# PX4FMUv2_4.net
KiCad netlist of a schematic drawn in EAGLE
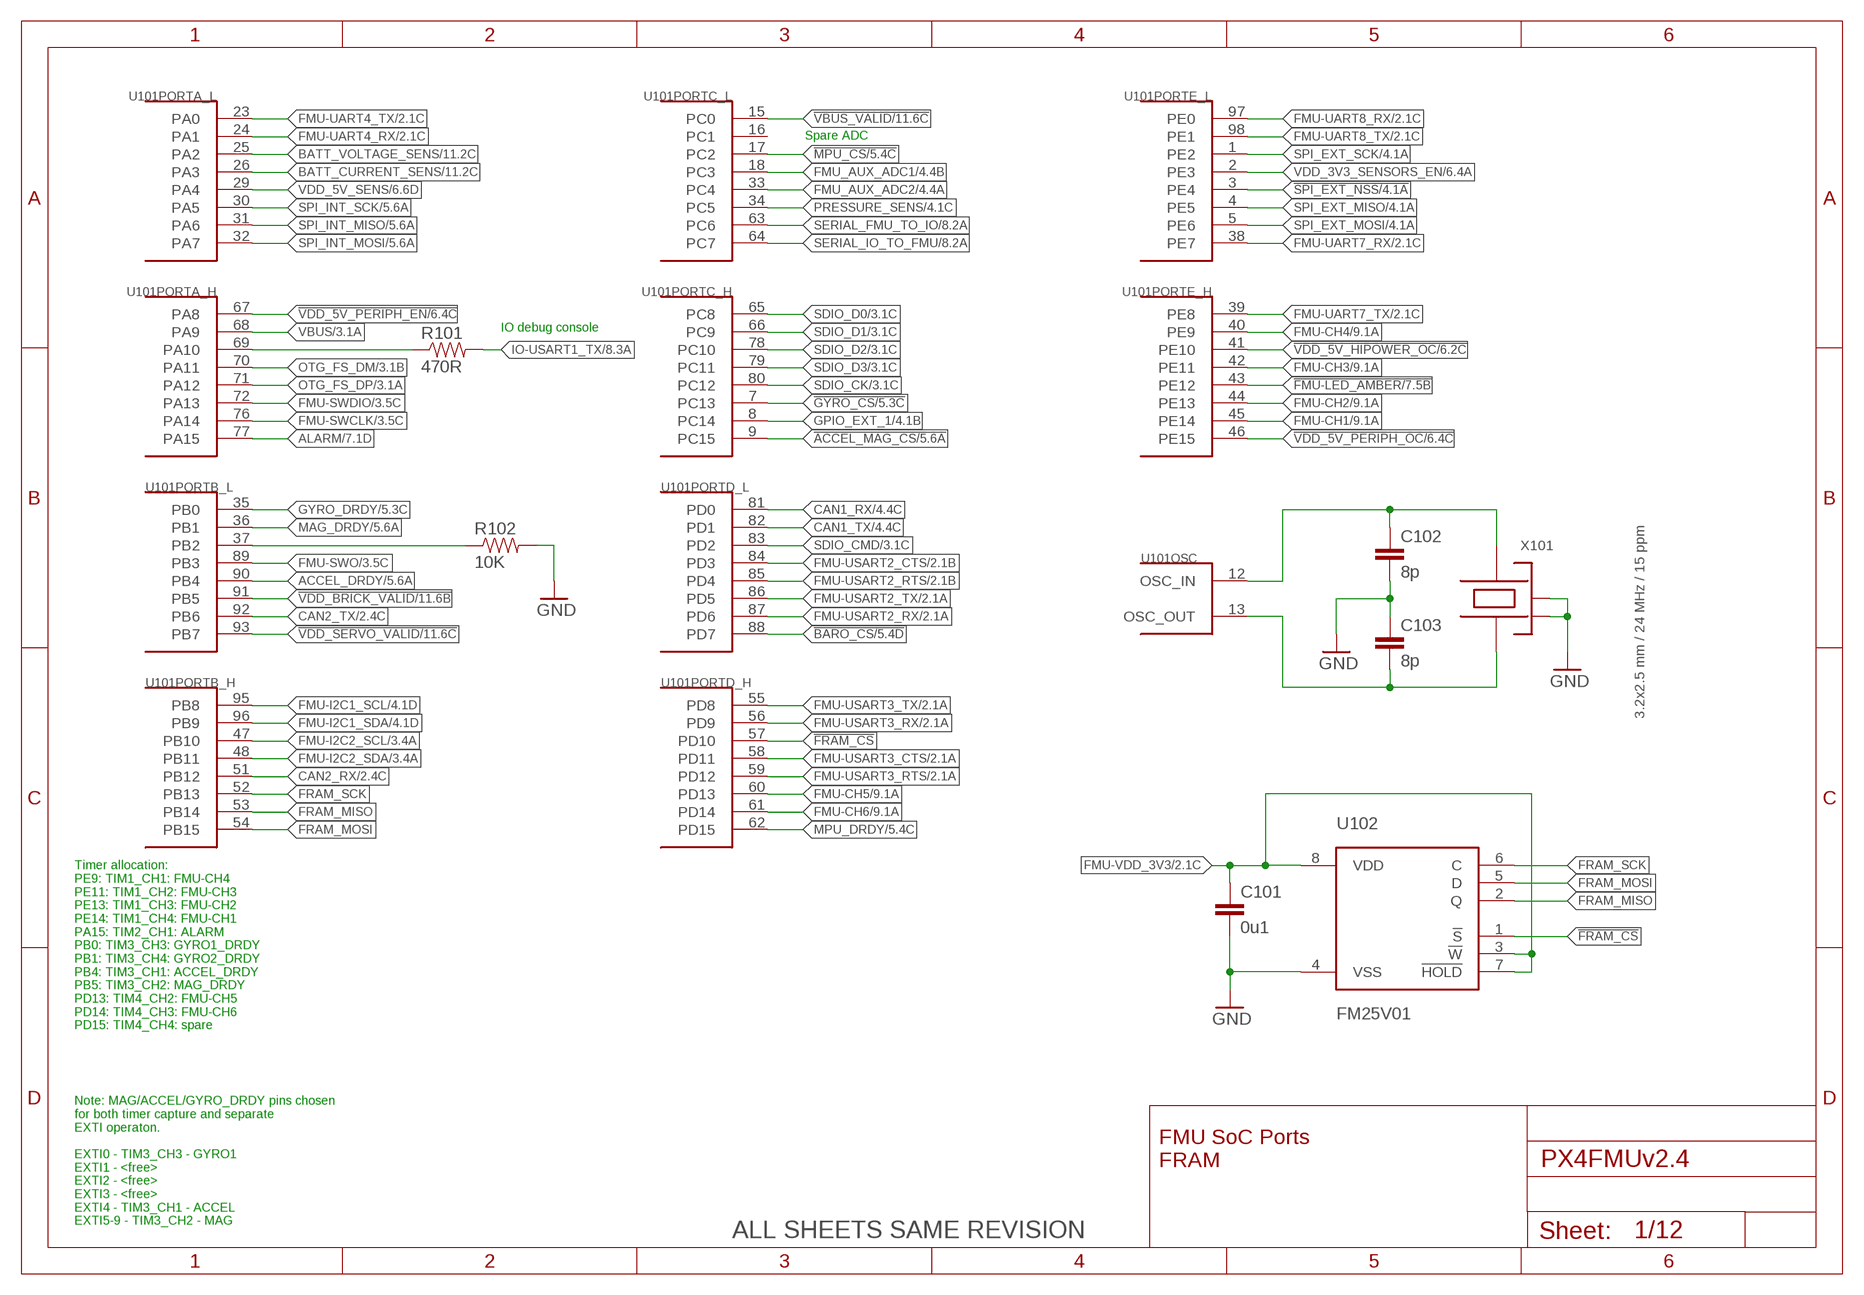
[diagram p0: schematic, sheet 1]
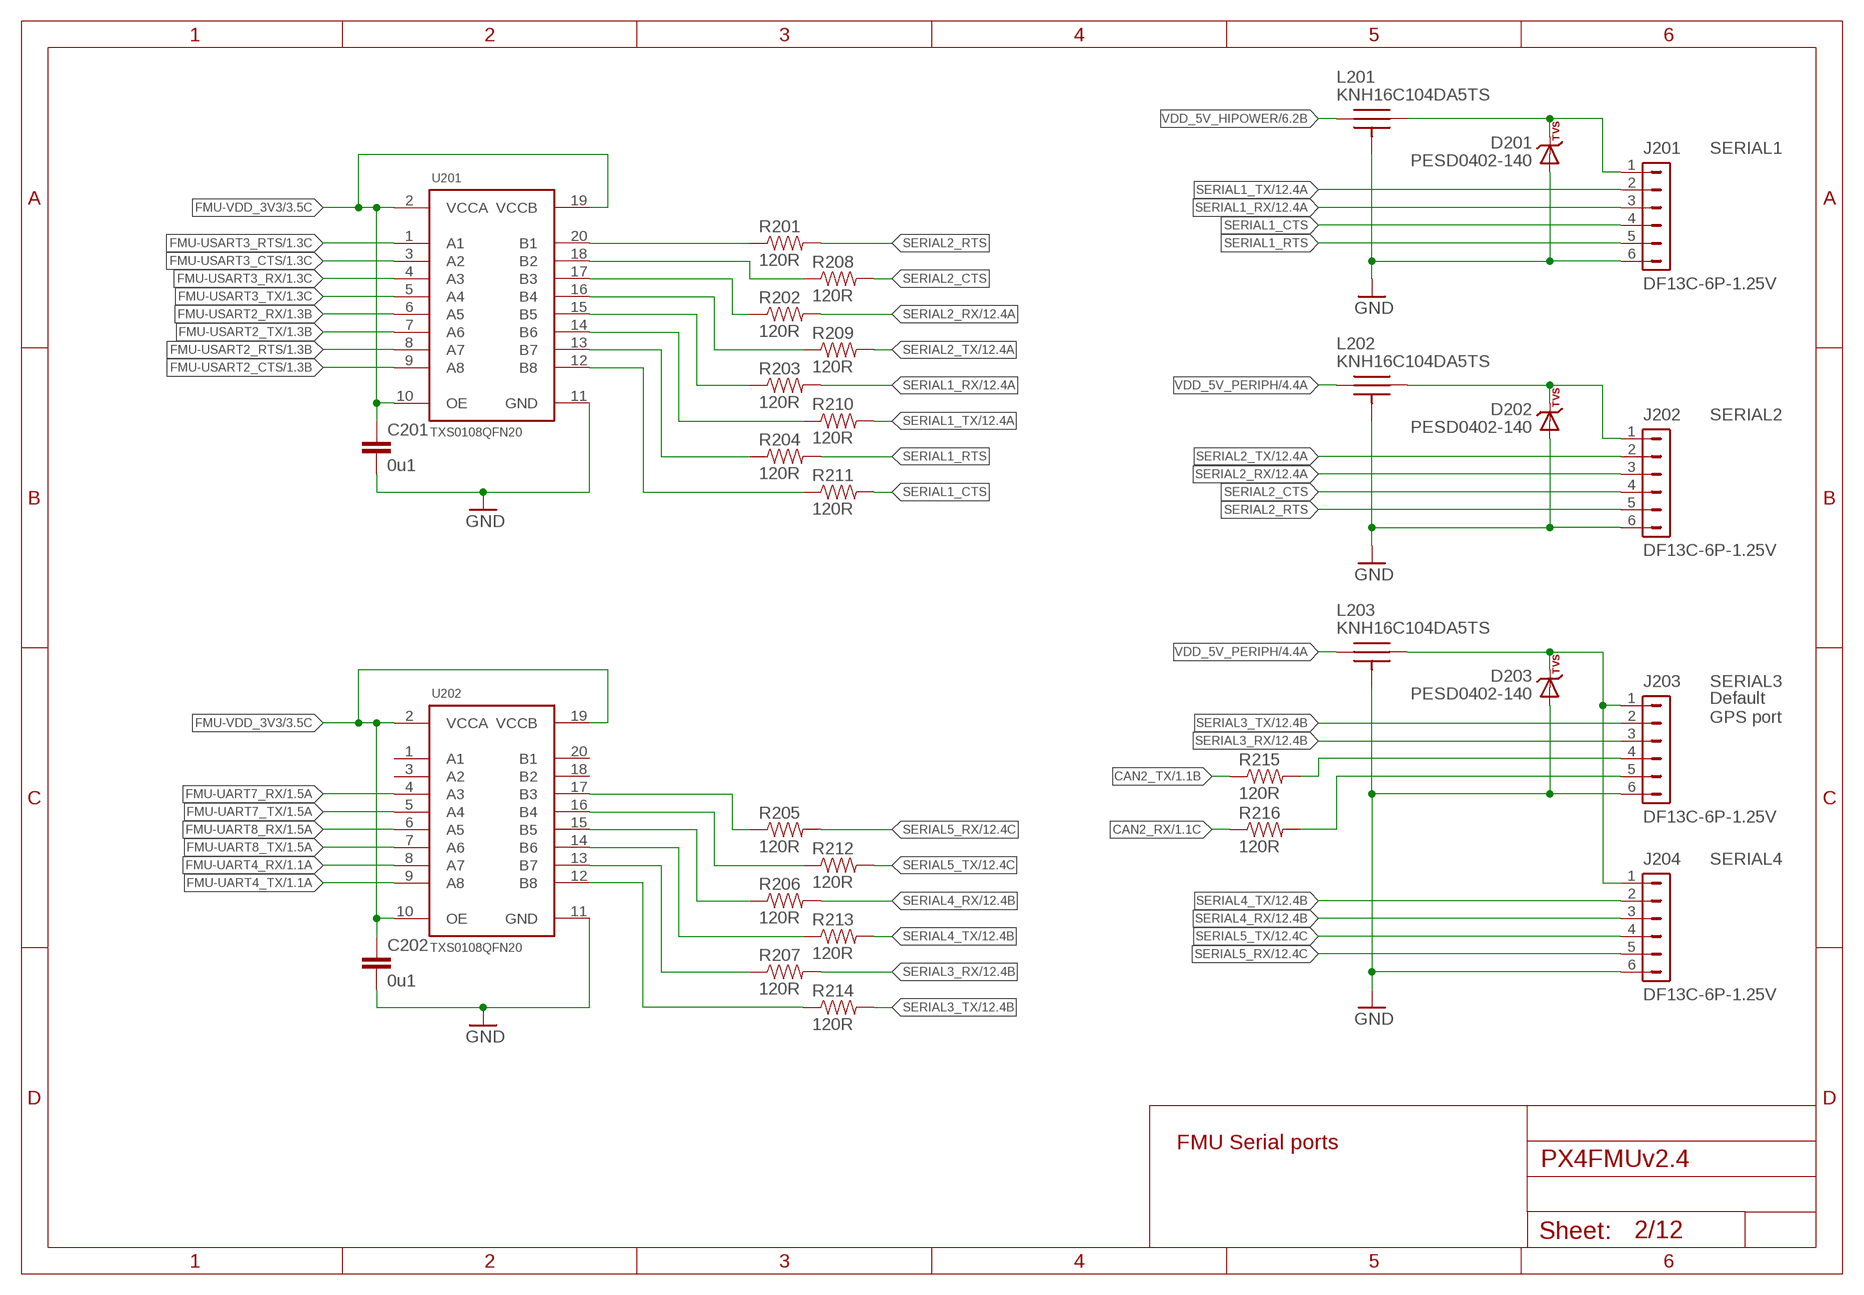
[diagram p1: schematic, sheet 2]
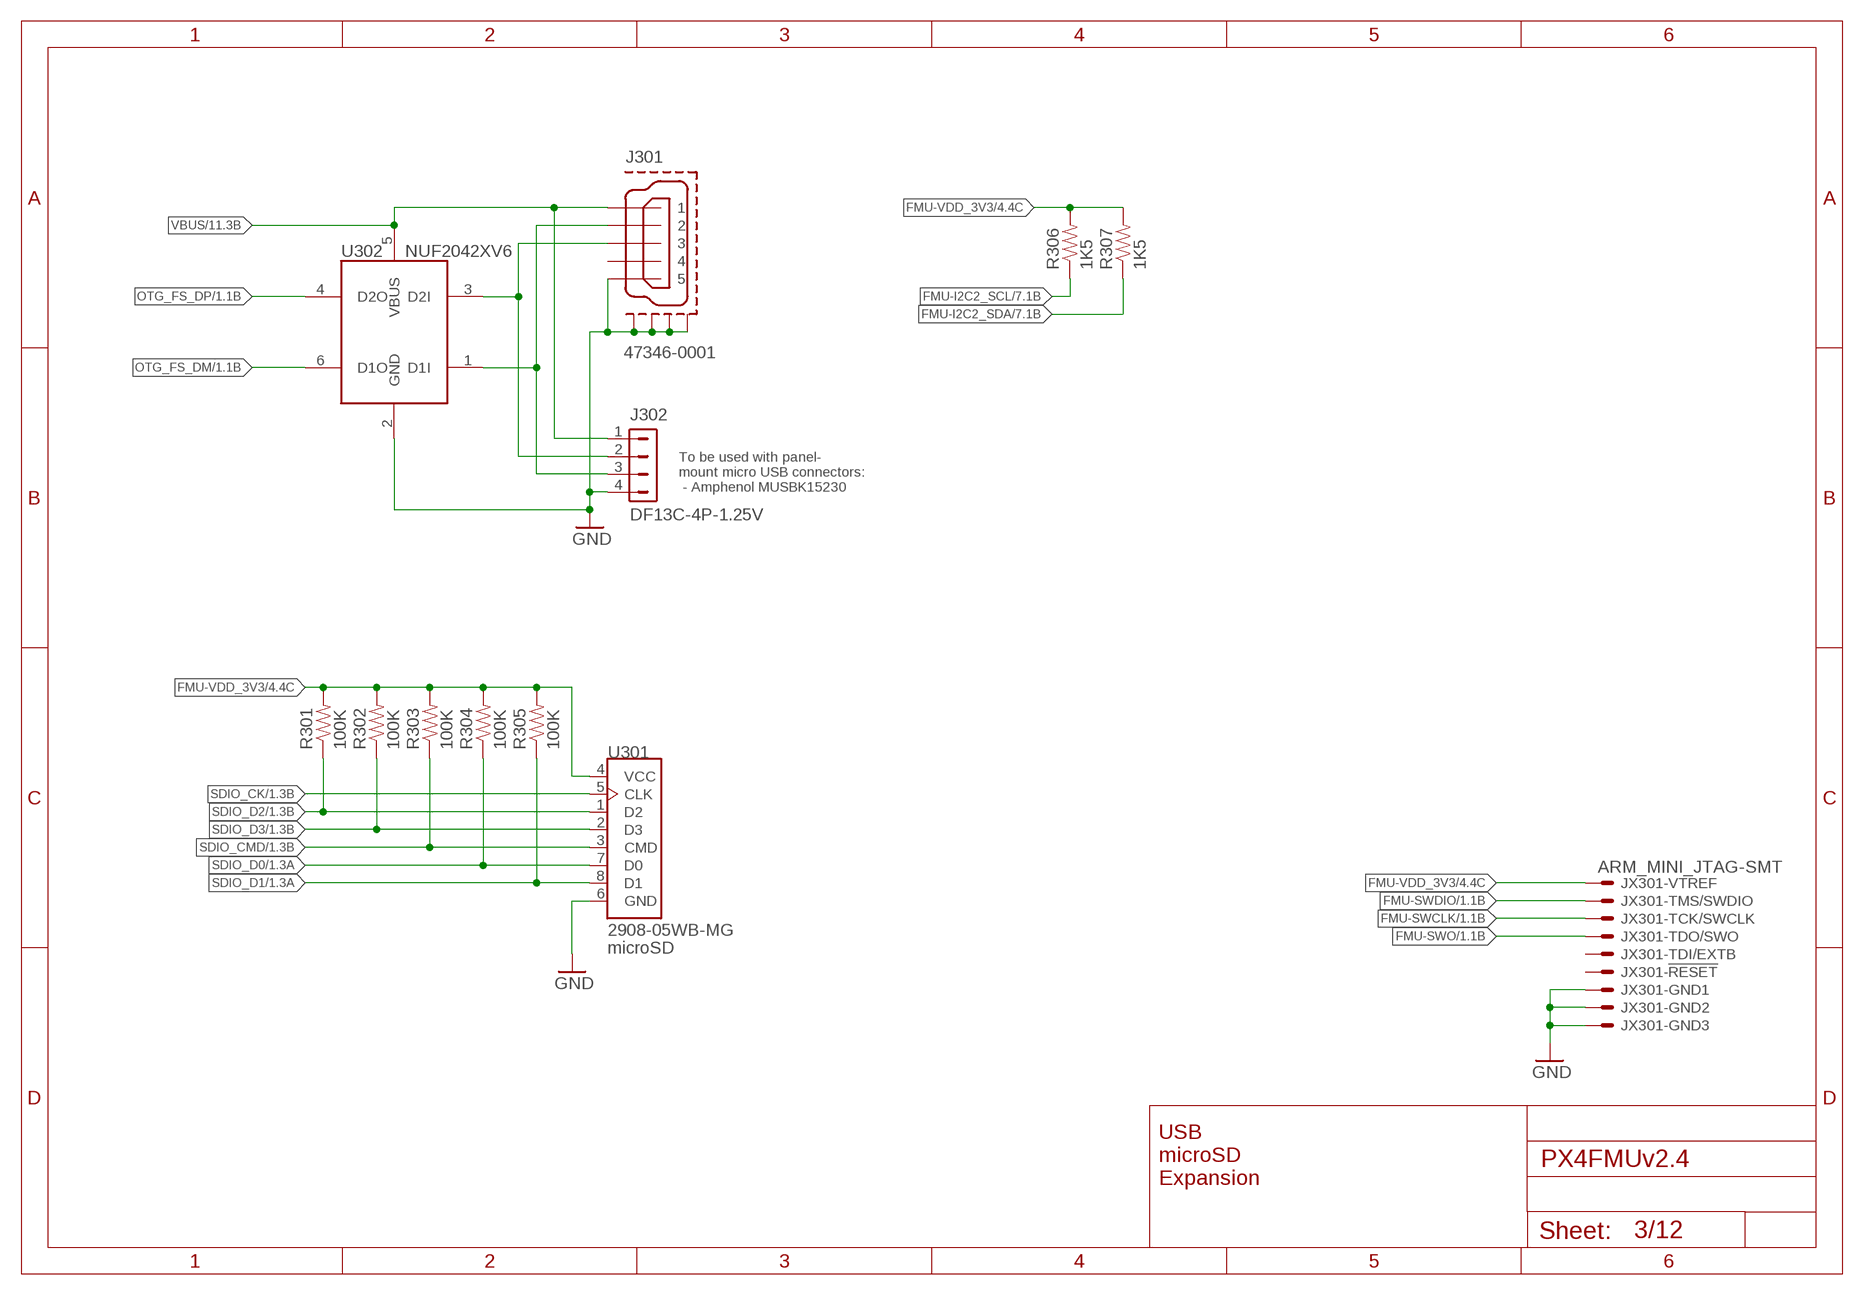
[diagram p2: schematic, sheet 3]
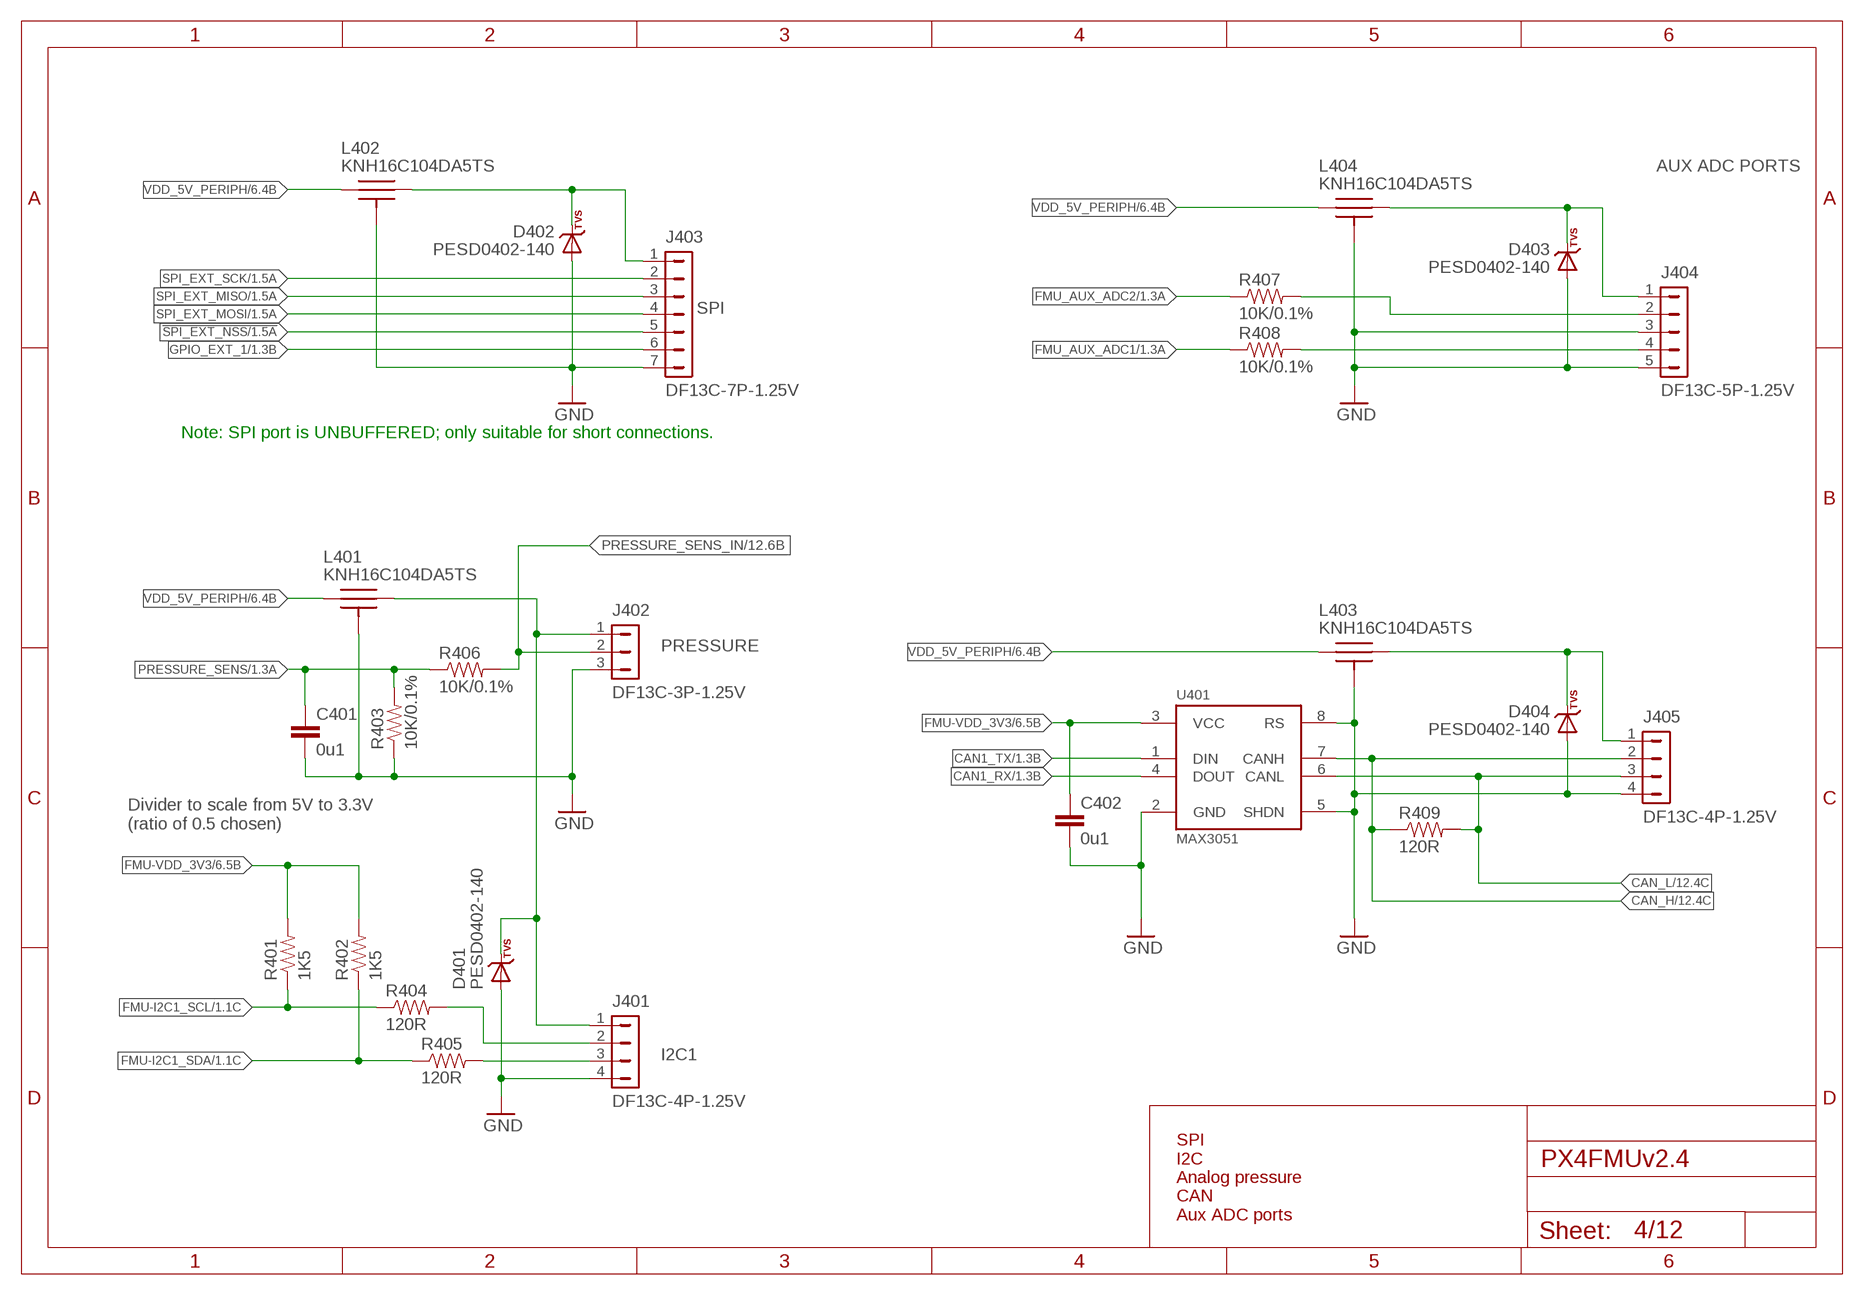
[diagram p3: schematic, sheet 4]
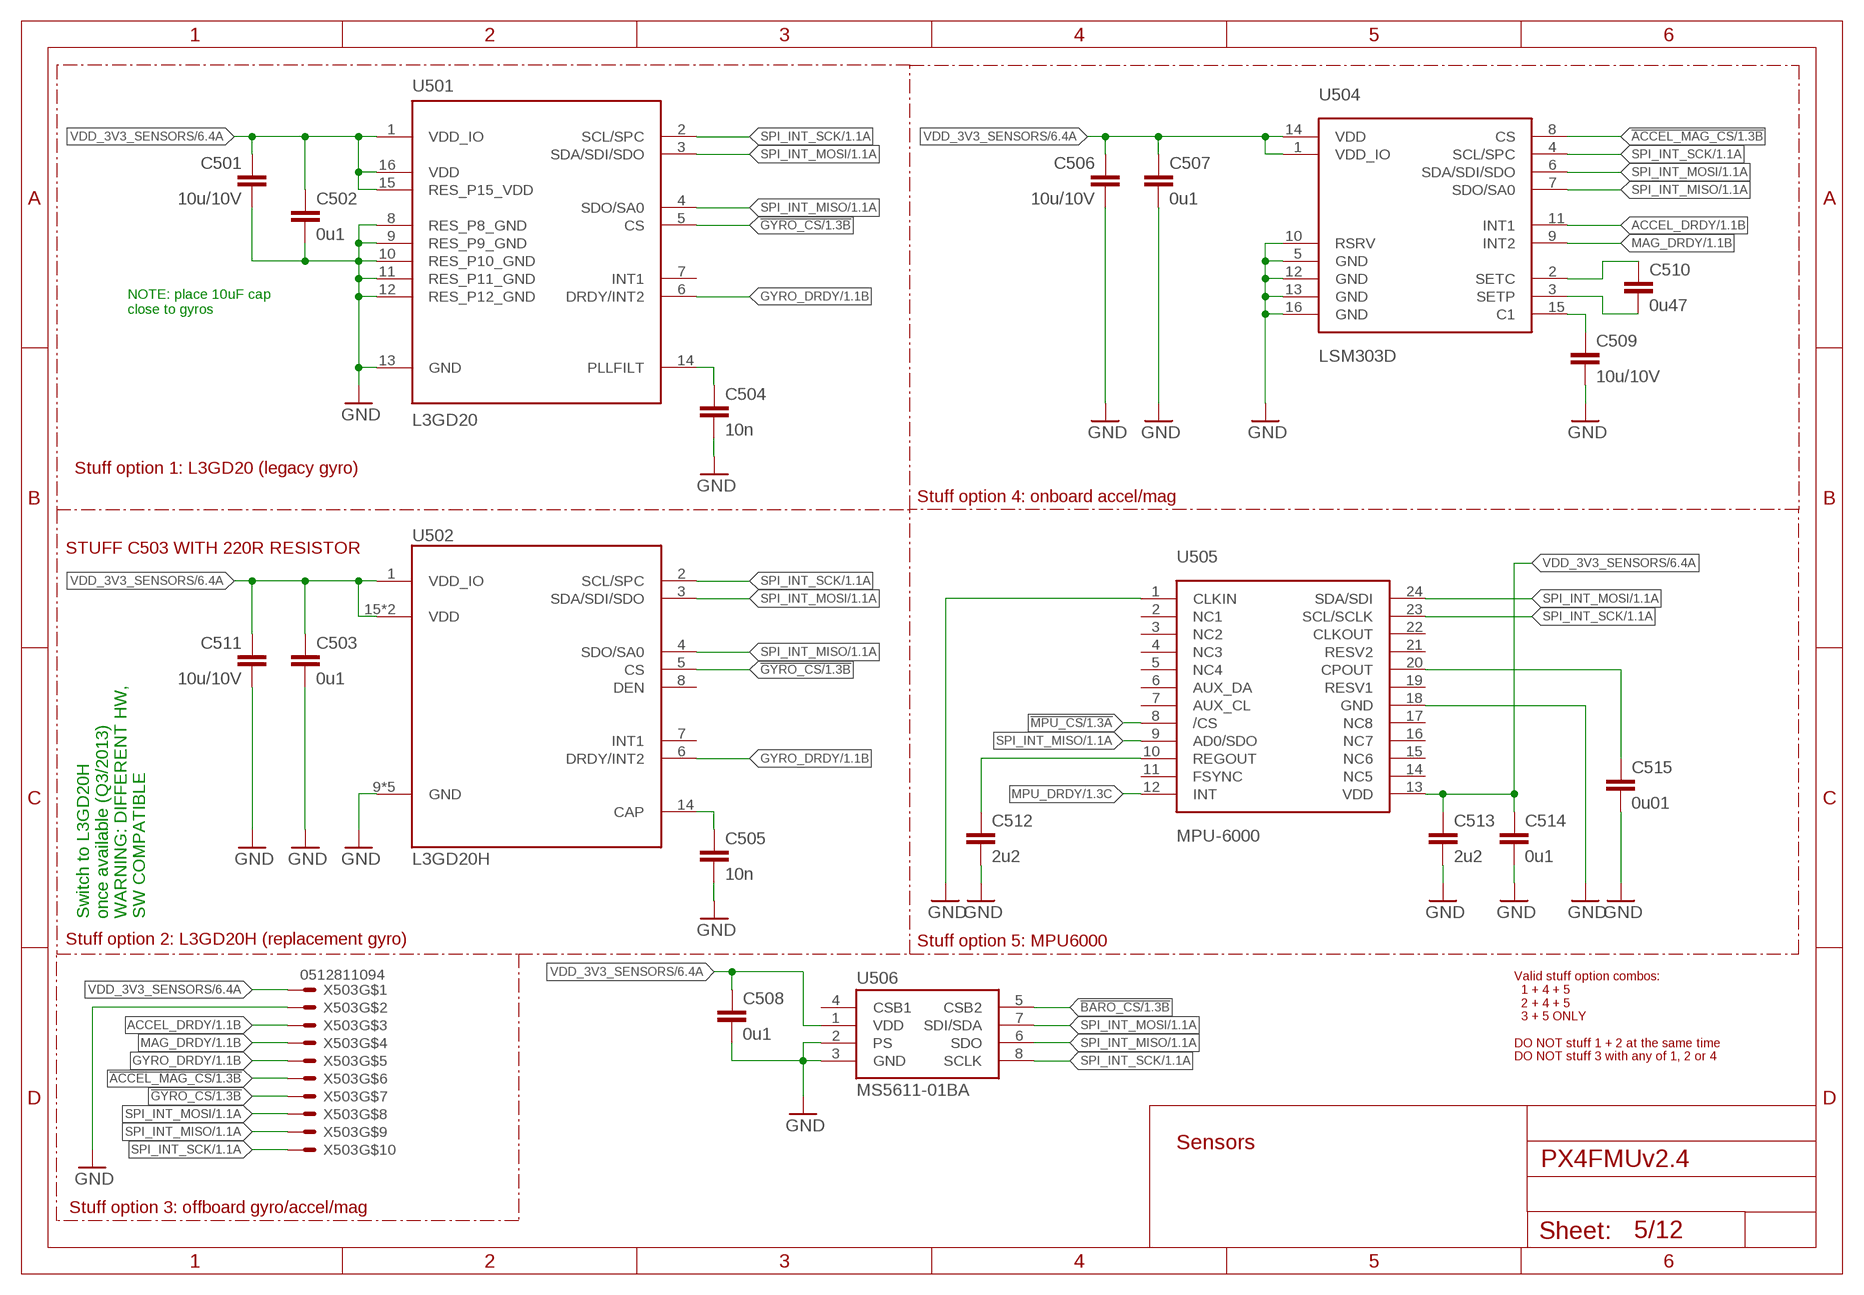
[diagram p4: schematic, sheet 5]
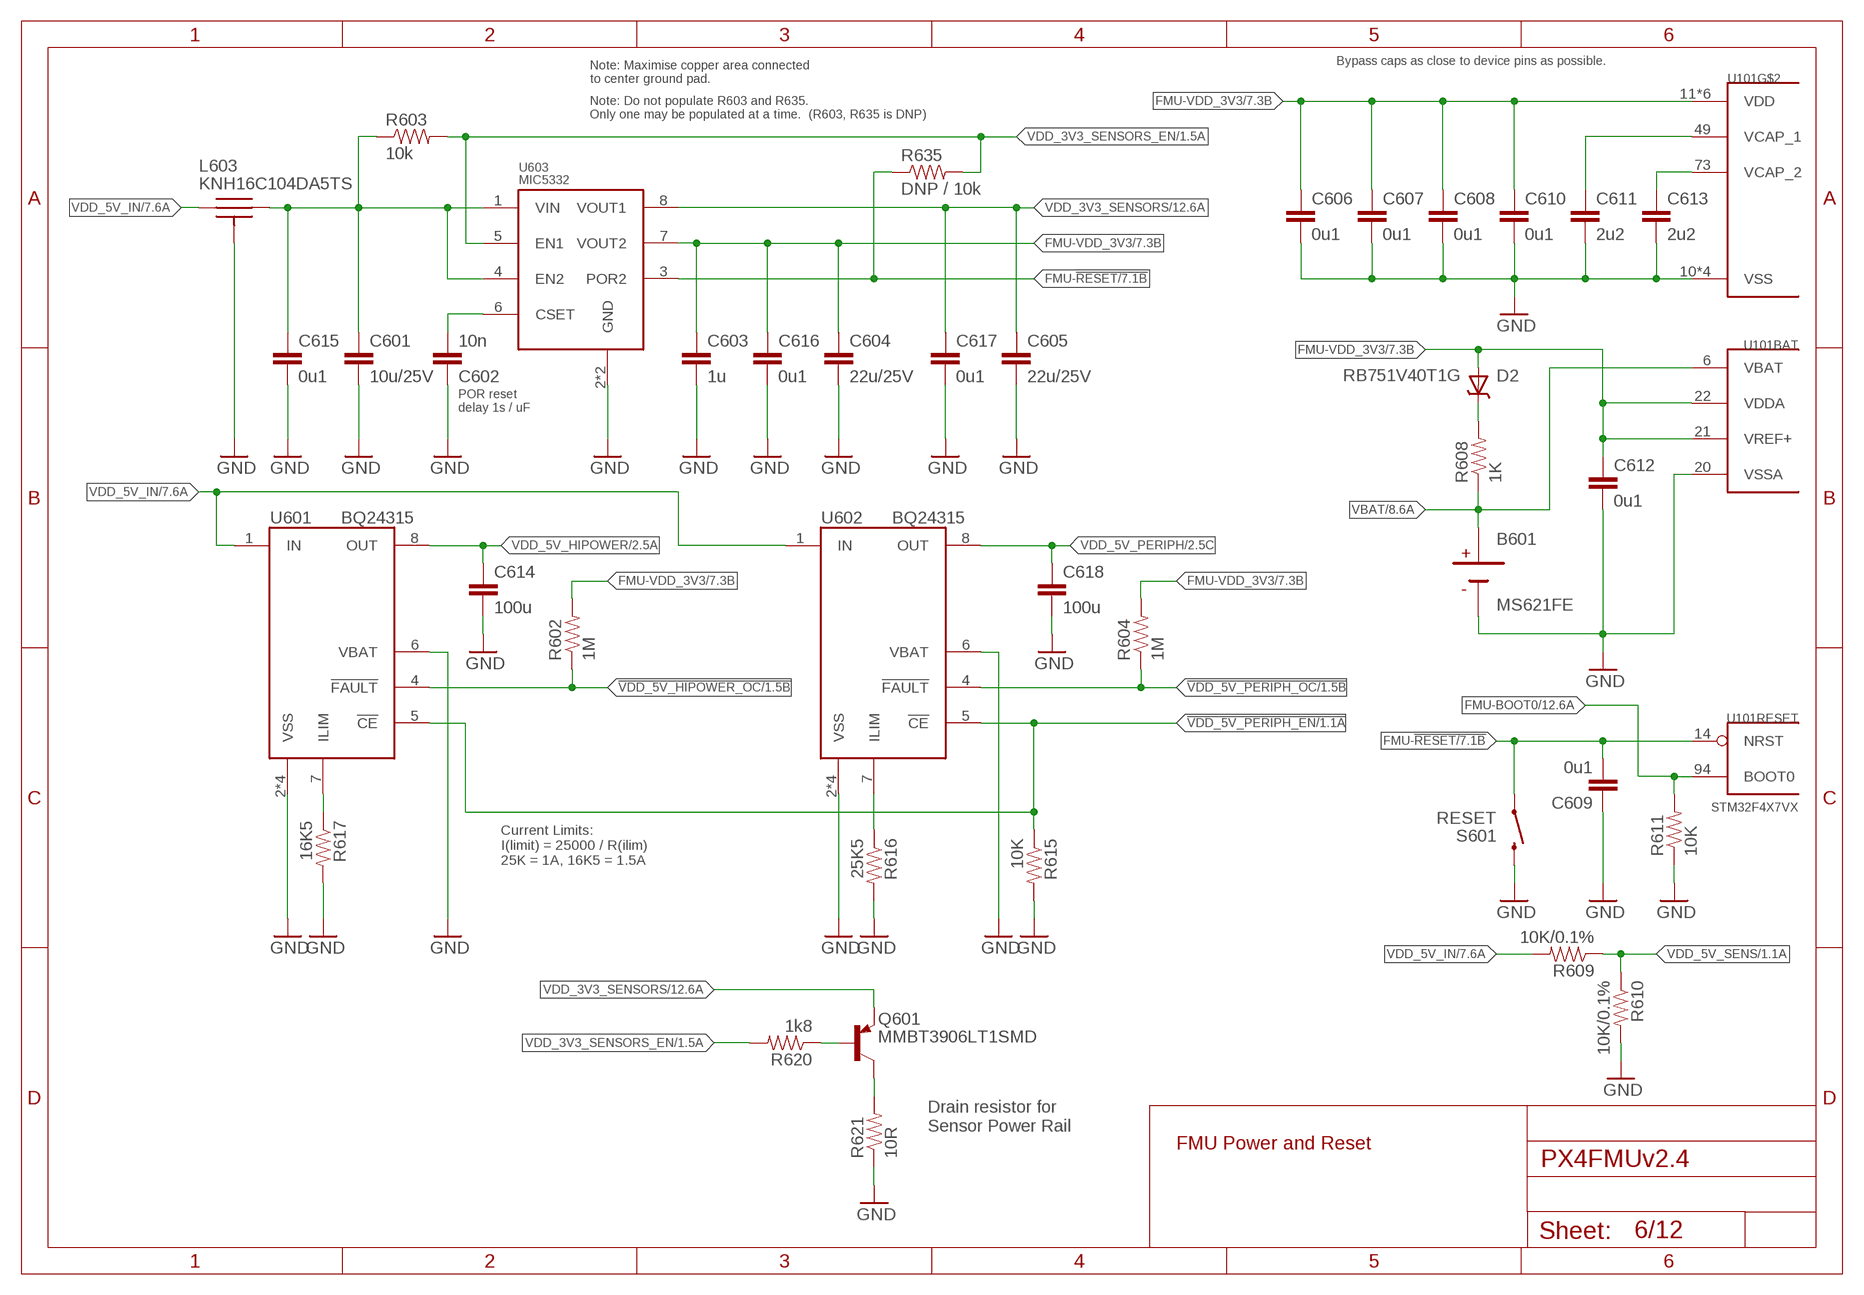
[diagram p5: schematic, sheet 6]
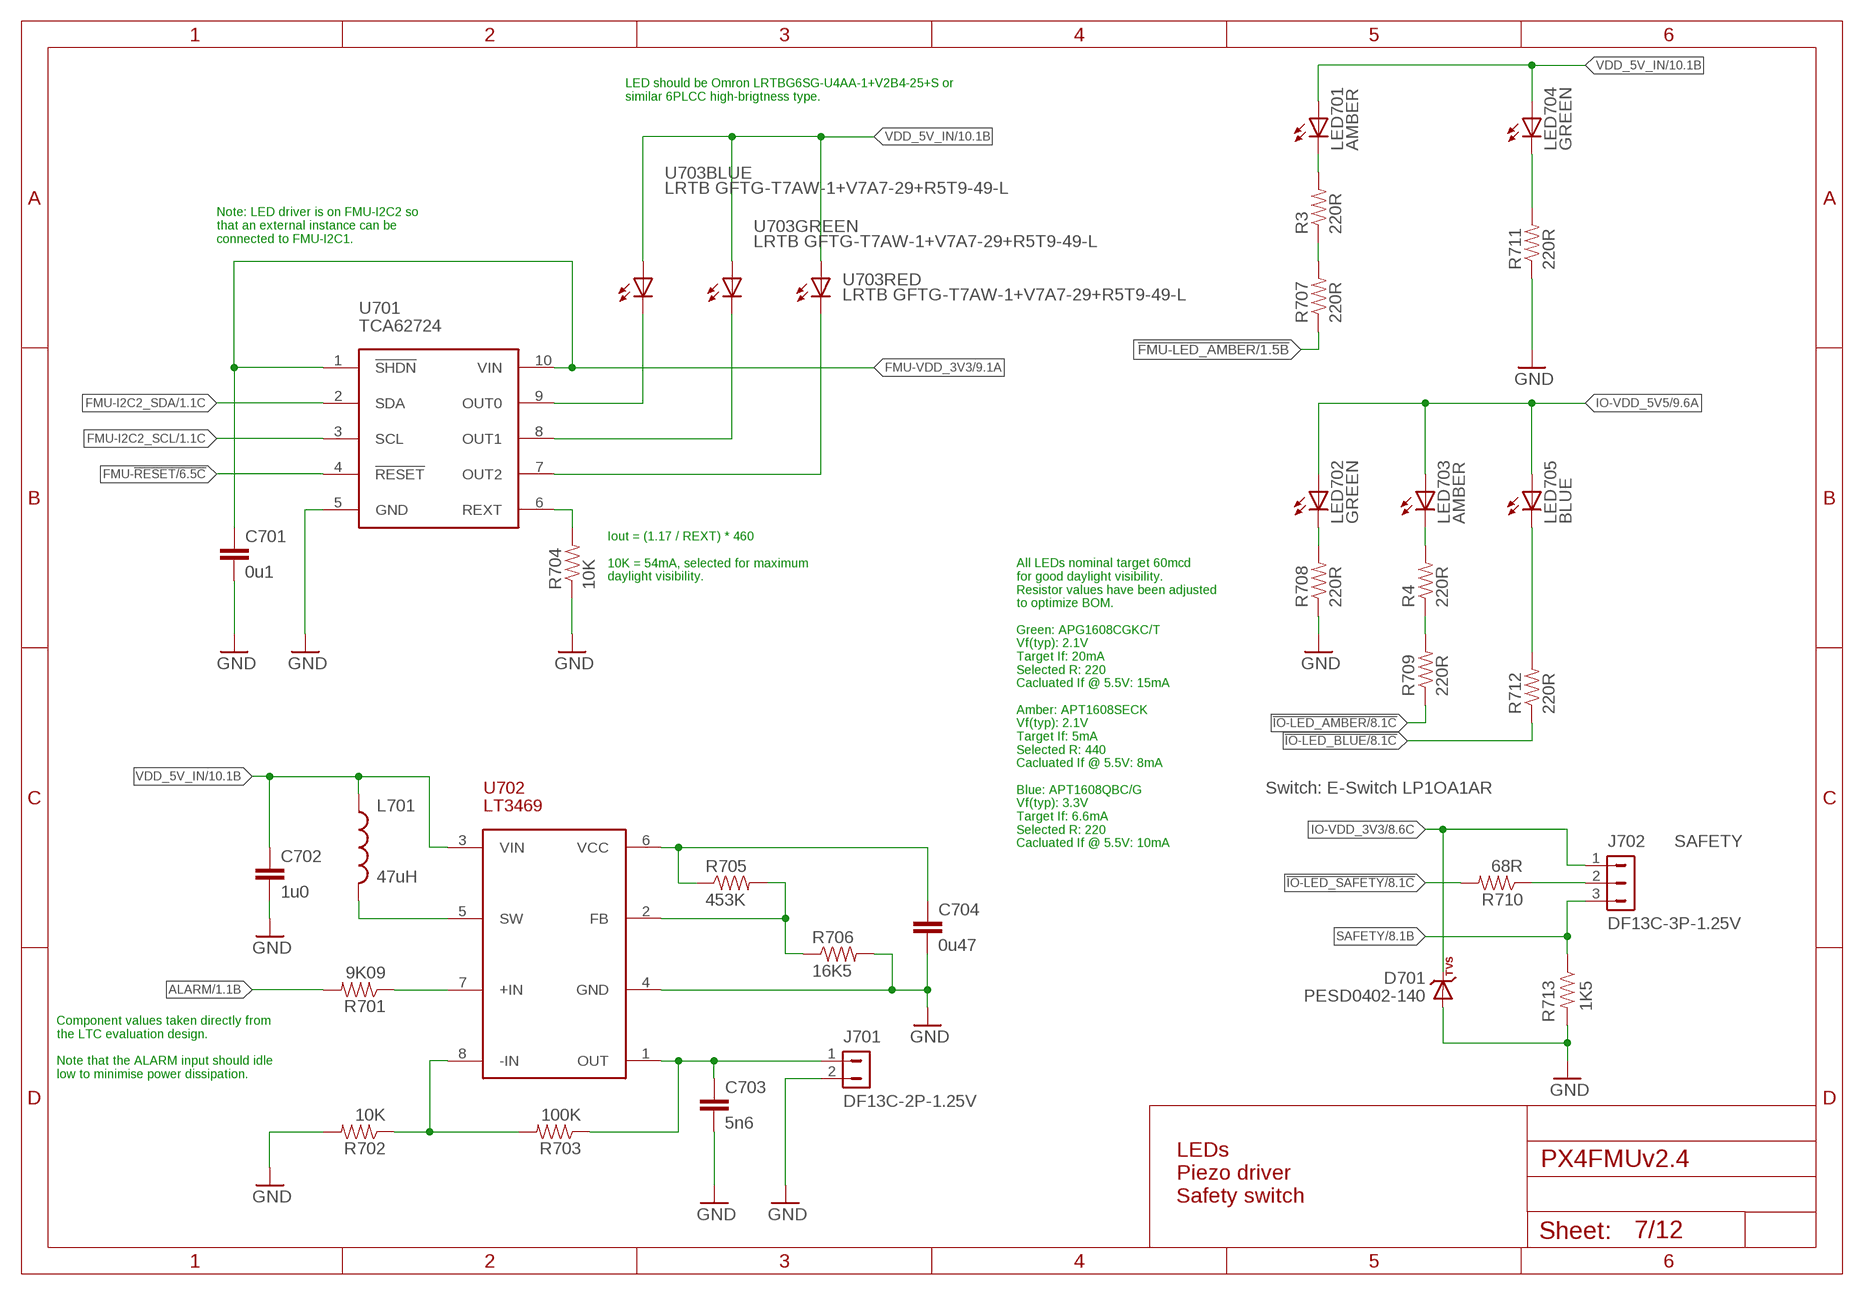
[diagram p6: schematic, sheet 7]
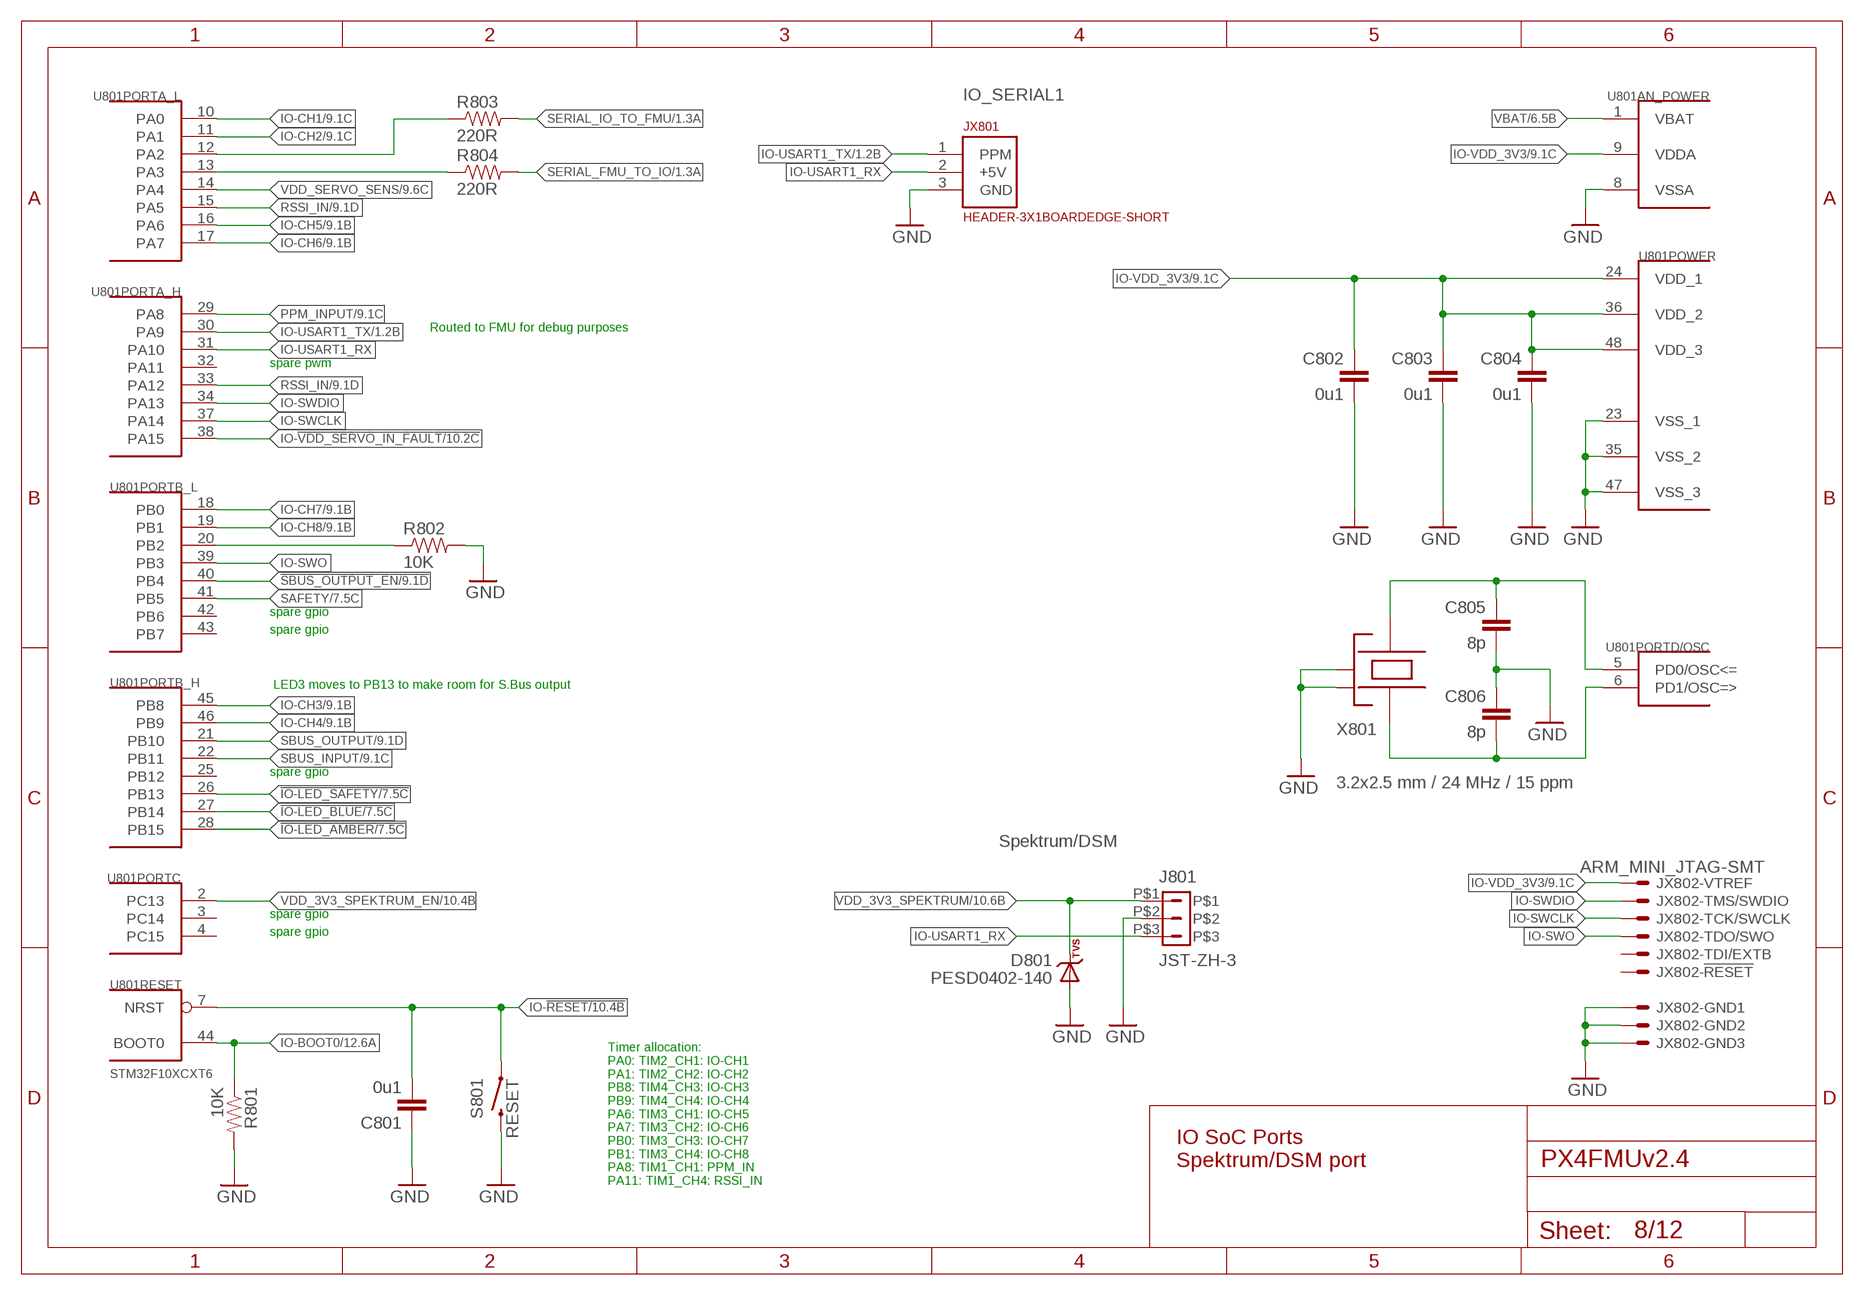
[diagram p7: schematic, sheet 8]
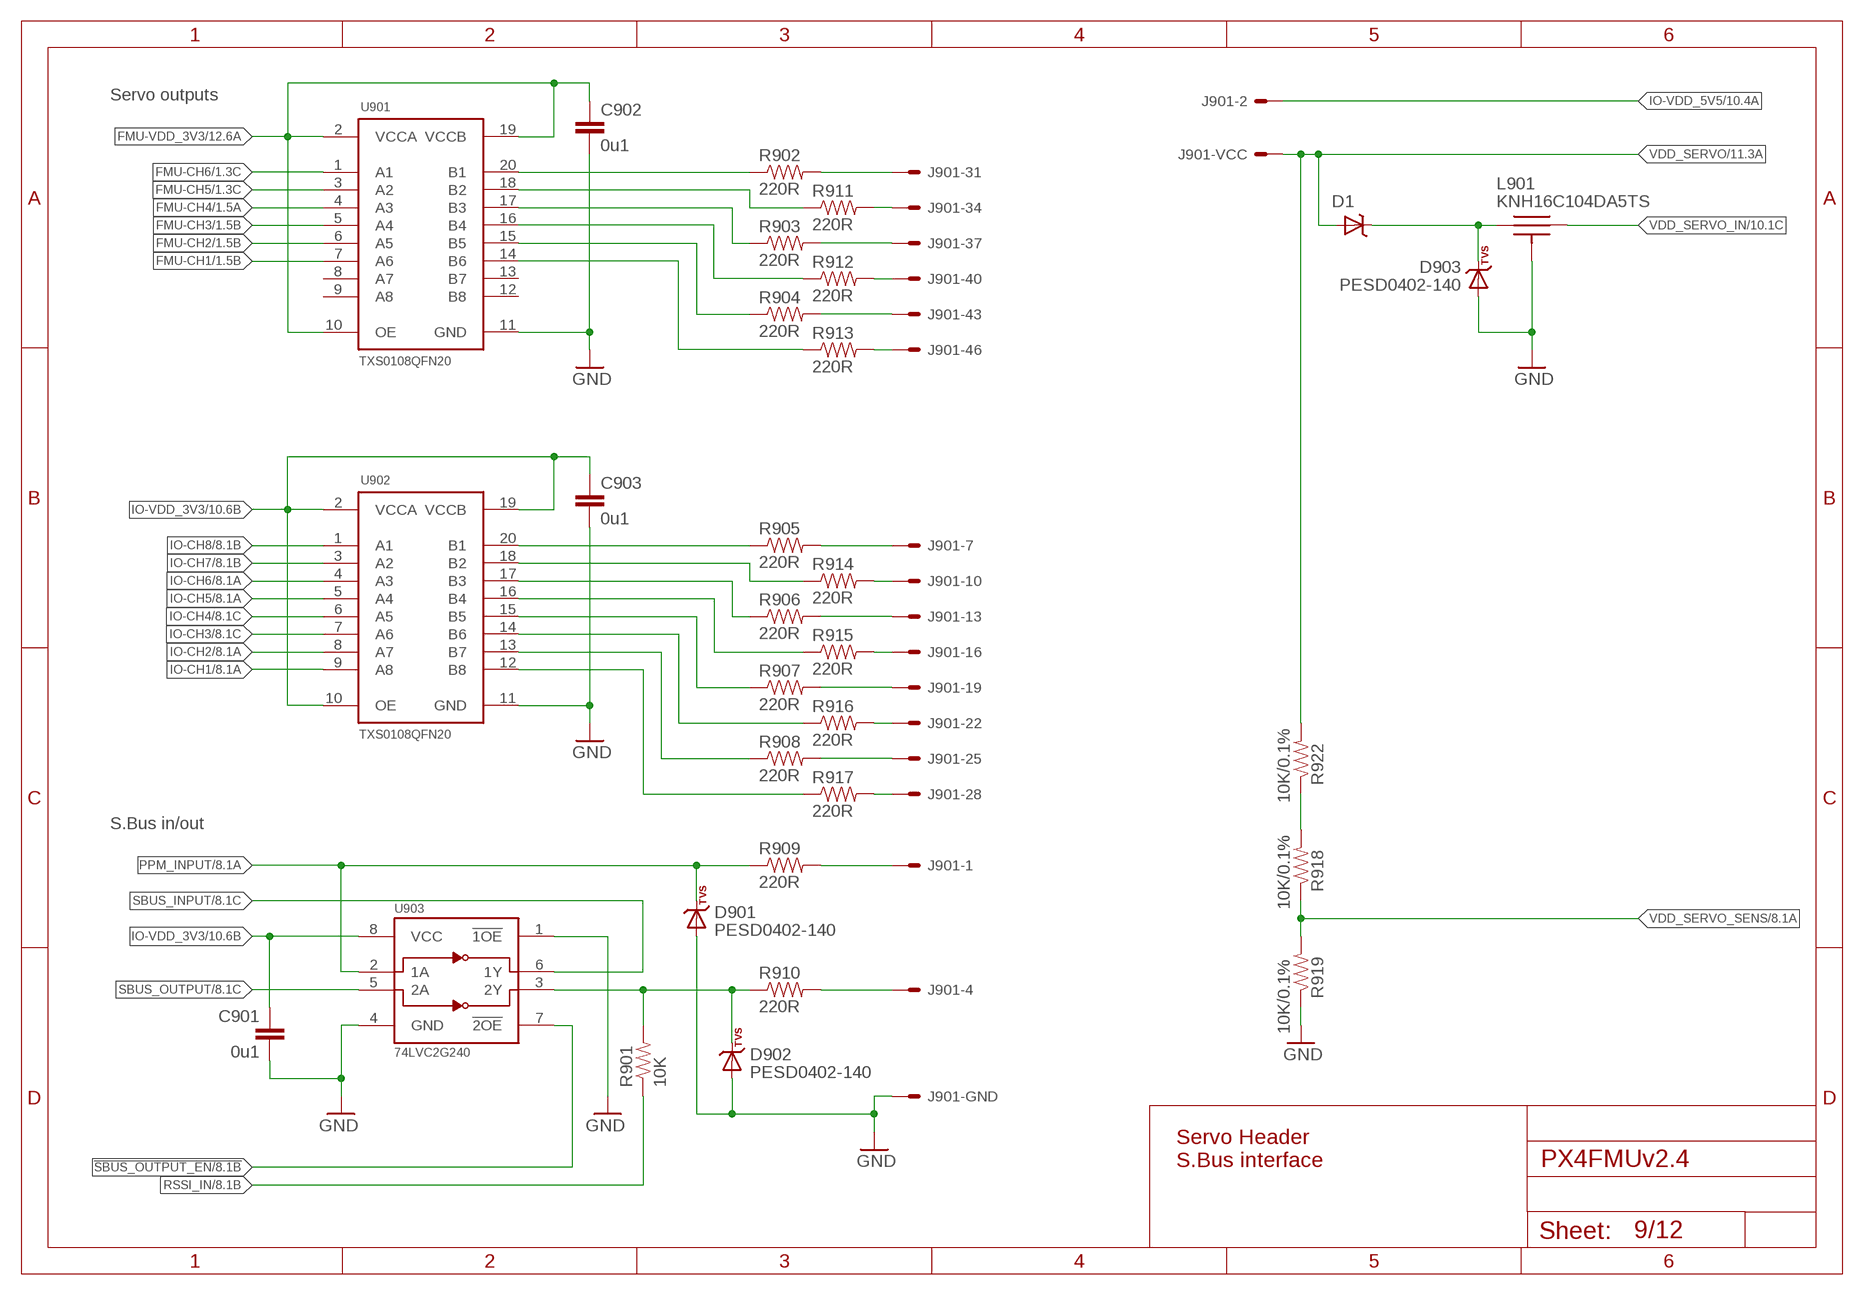
[diagram p8: schematic, sheet 9]
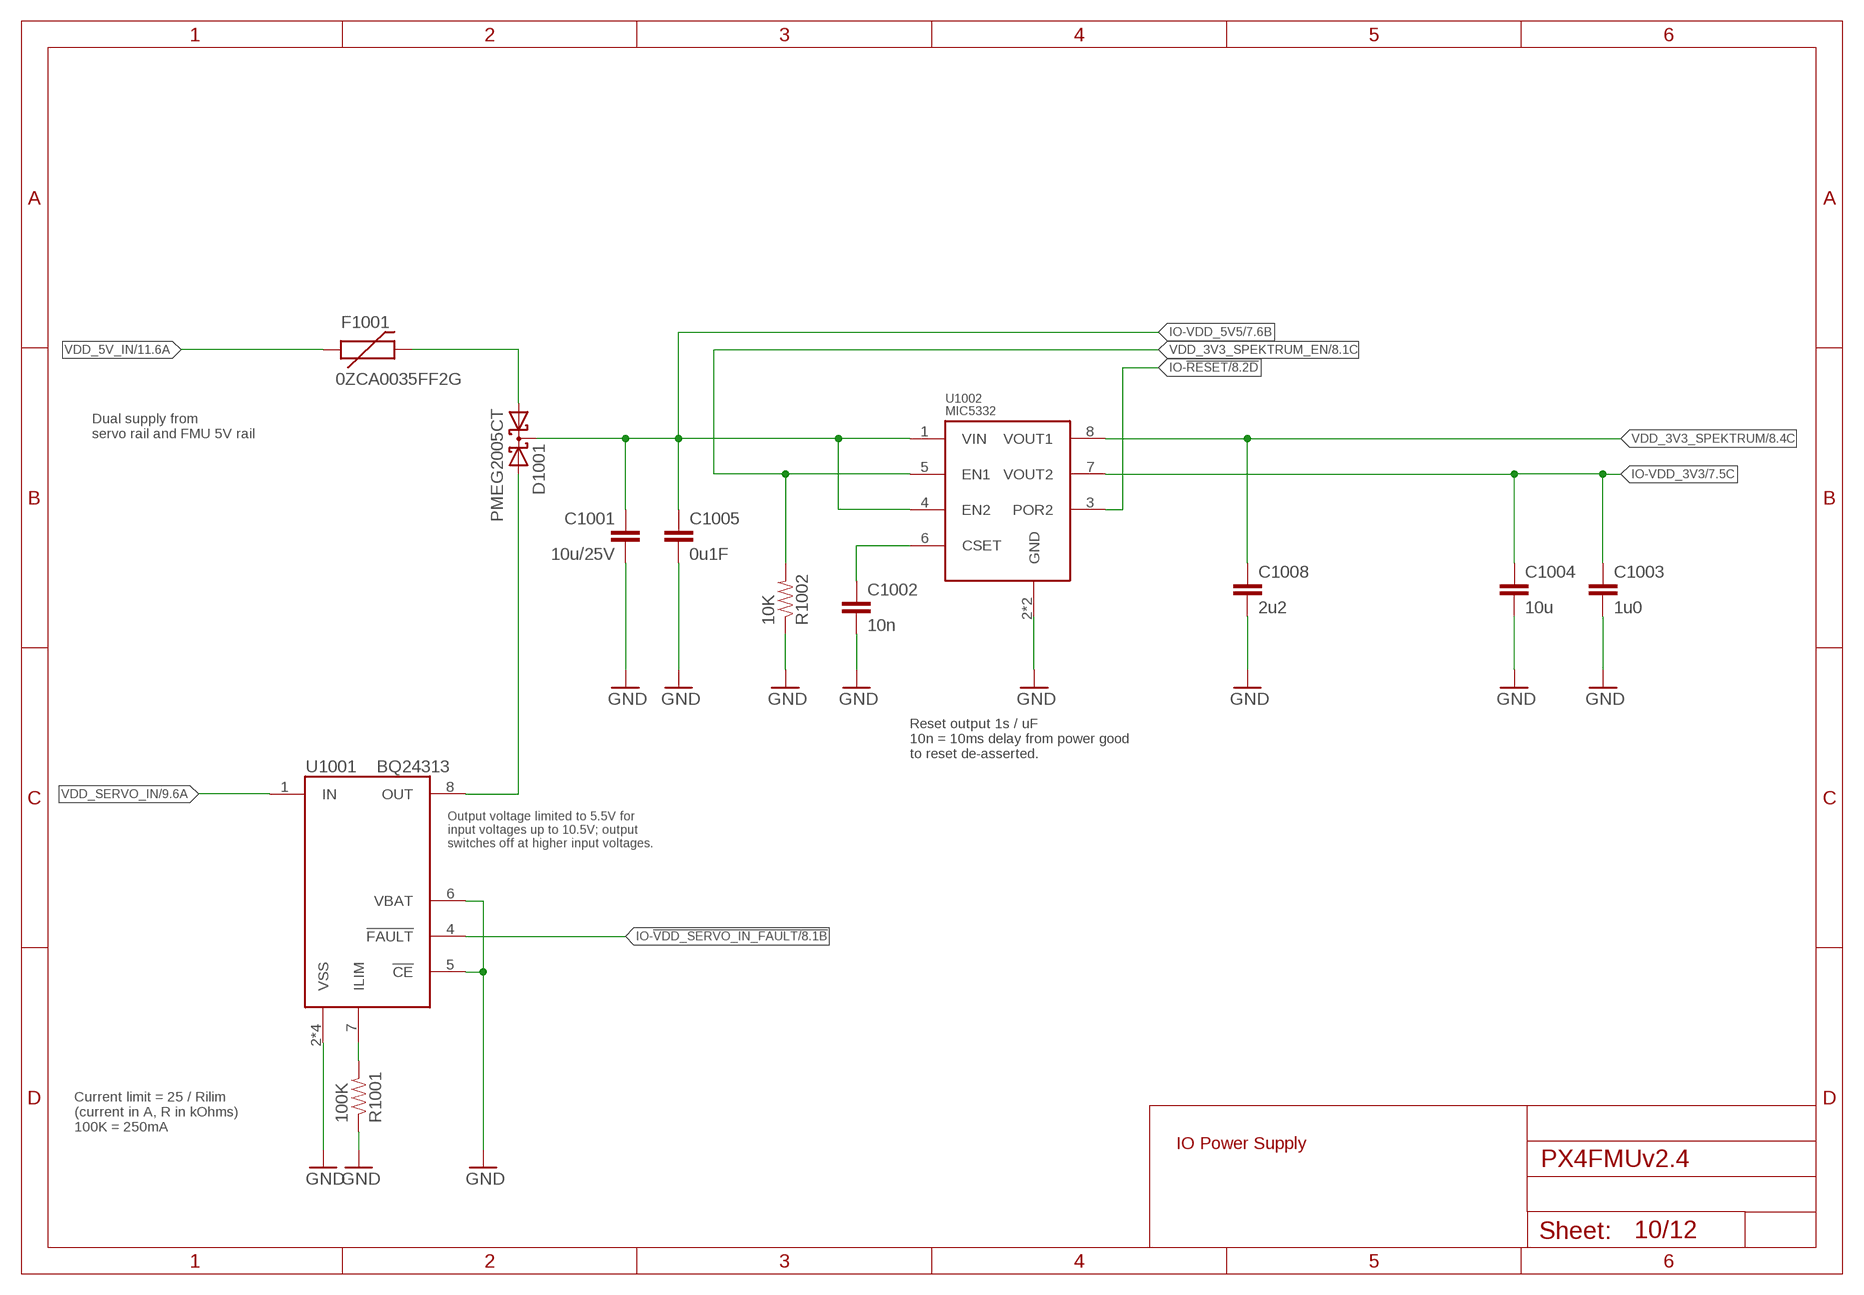
[diagram p9: schematic, sheet 10]
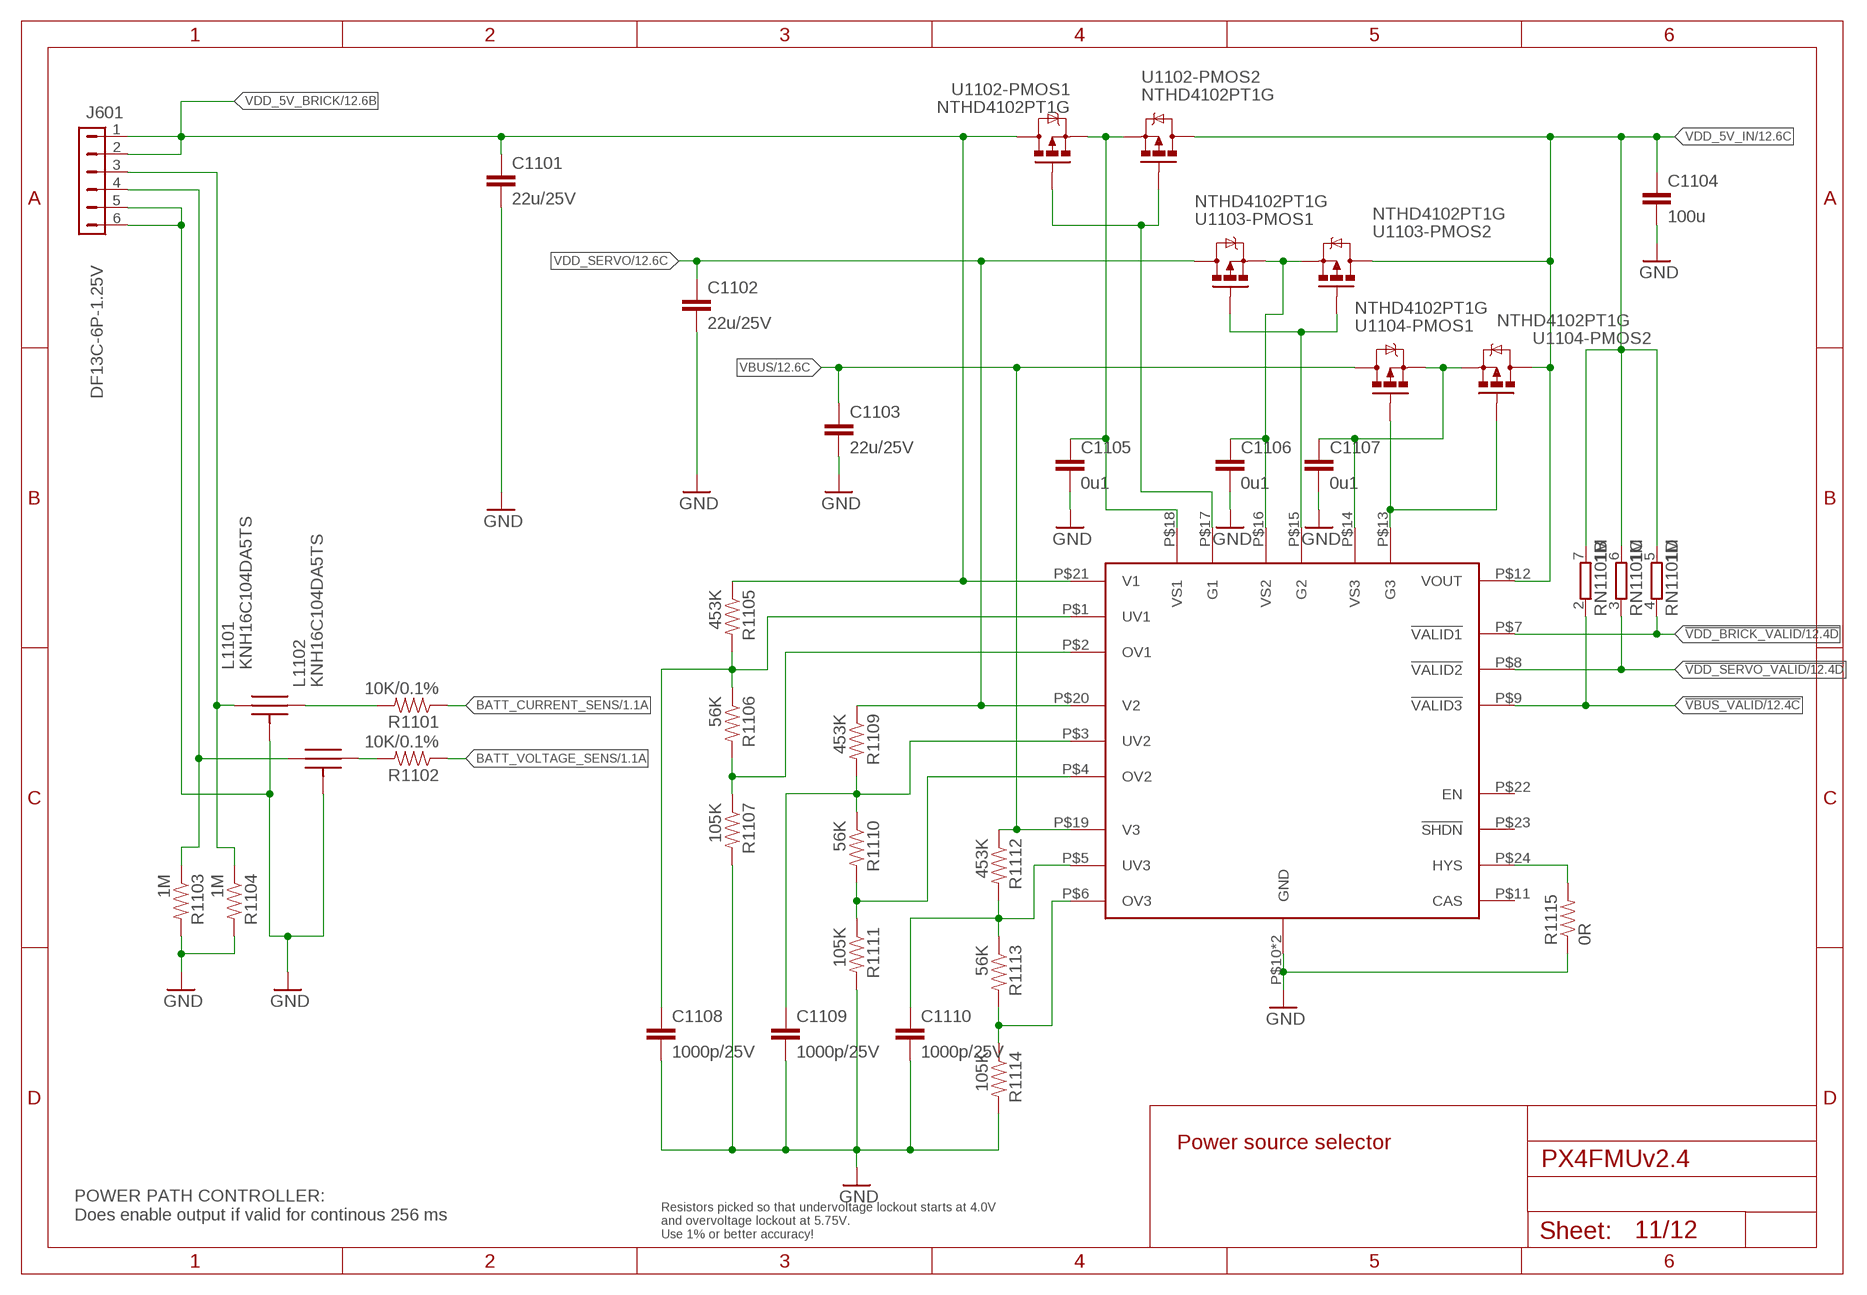
[diagram p10: schematic, sheet 11]
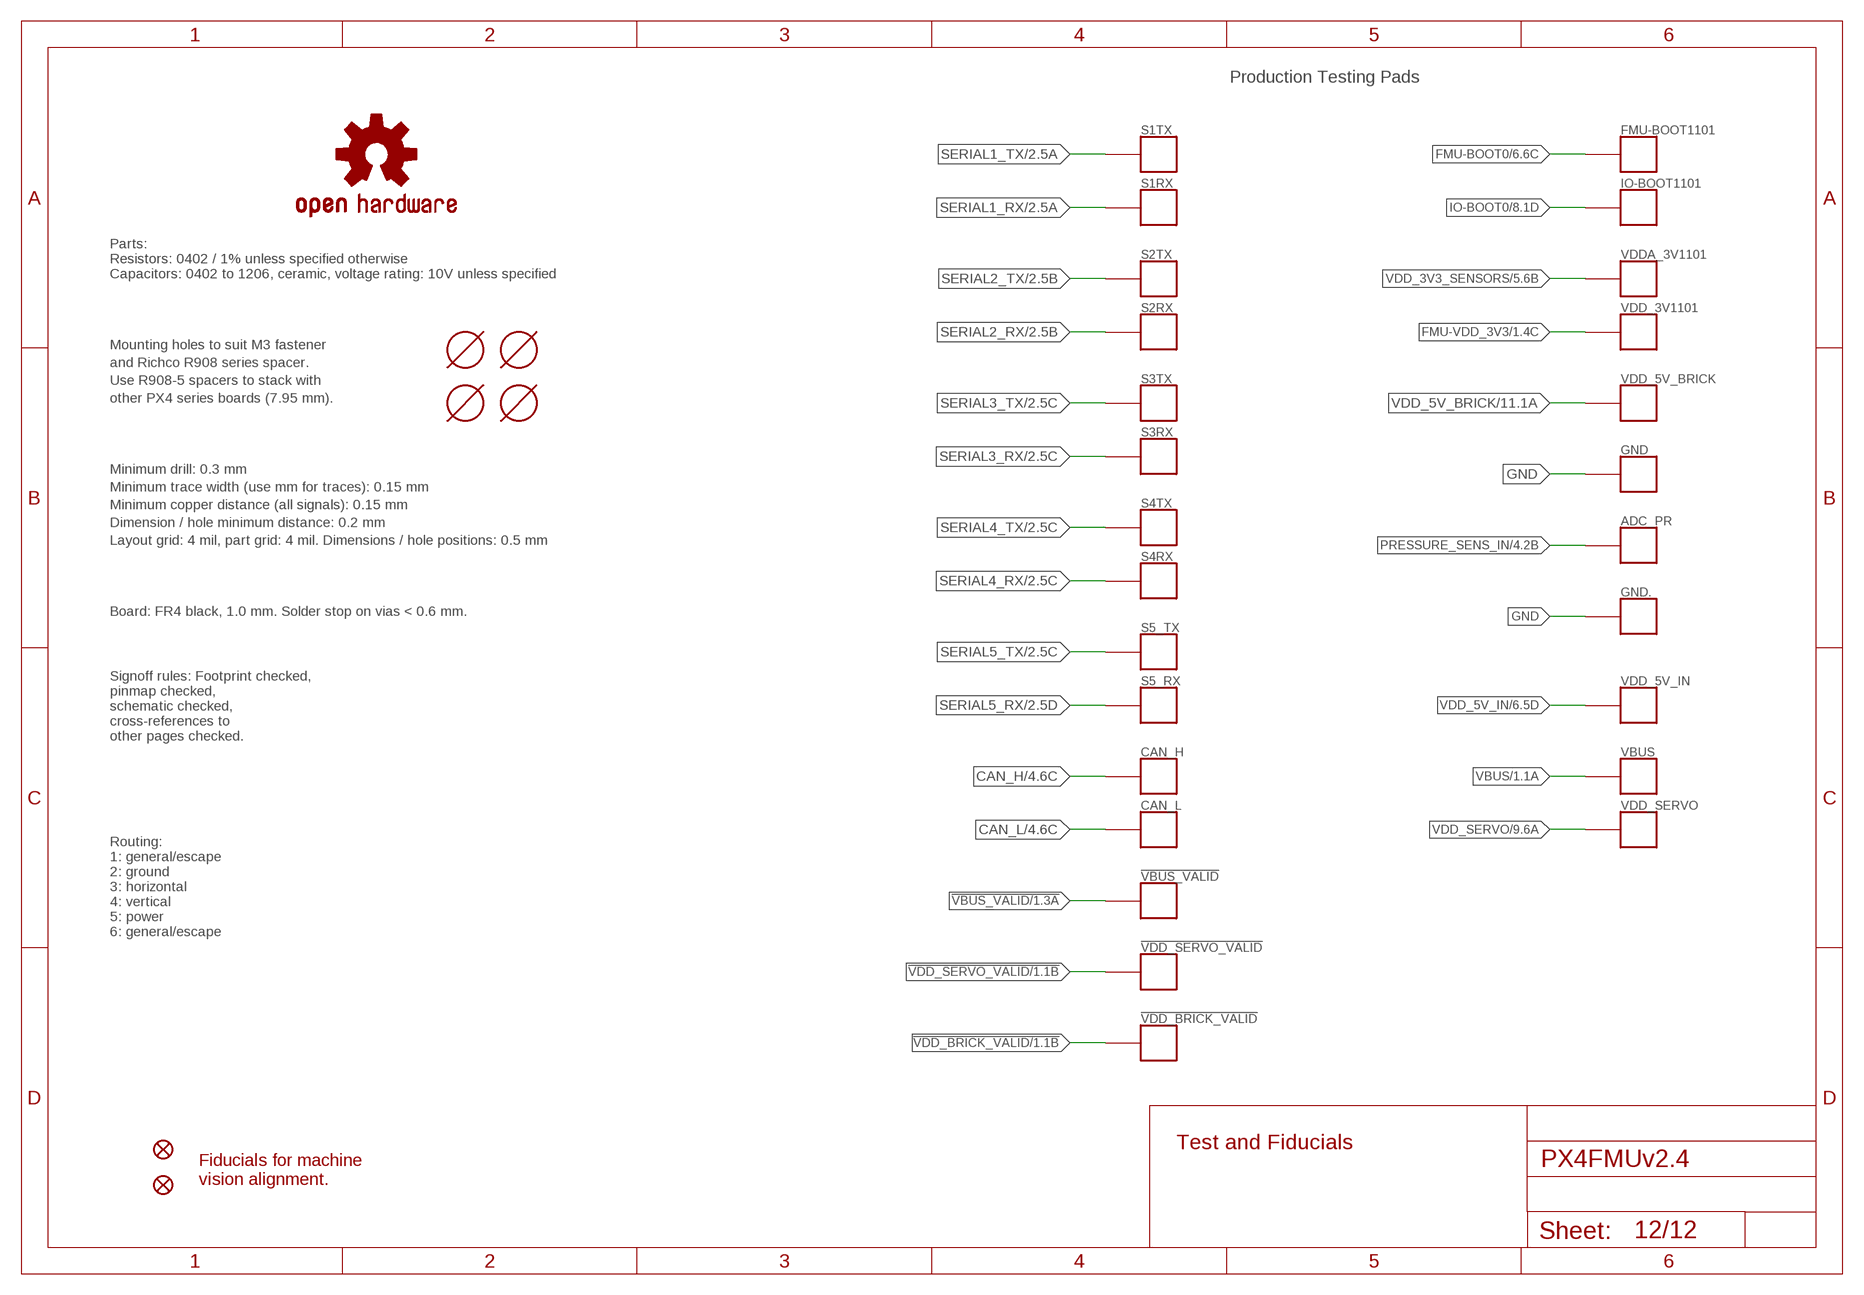
[diagram p11: schematic, sheet 12]

(export (version "E")
  (design (tool "Eeschema 10.0.6"))
  (components
    (comp (ref "C801")
      (value "0u1")
      (footprint "eagle-import:0402-CAP")
      (fields (field (name "PARTNO") "CC0402ZRY5V7BB104"))
      (libsource (lib "eagle-import") (part "CAP0402"))
    )
    (comp (ref "C802")
      (value "0u1")
      (footprint "eagle-import:0402-CAP")
      (fields (field (name "PARTNO") "CC0402ZRY5V7BB104"))
      (libsource (lib "eagle-import") (part "CAP0402"))
    )
    (comp (ref "C803")
      (value "0u1")
      (footprint "eagle-import:0402-CAP")
      (fields (field (name "PARTNO") "CC0402ZRY5V7BB104"))
      (libsource (lib "eagle-import") (part "CAP0402"))
    )
    (comp (ref "C804")
      (value "0u1")
      (footprint "eagle-import:0402-CAP")
      (fields (field (name "PARTNO") "CC0402ZRY5V7BB104"))
      (libsource (lib "eagle-import") (part "CAP0402"))
    )
    (comp (ref "C805")
      (value "8p")
      (footprint "eagle-import:0402-CAP")
      (fields (field (name "PARTNO") "C1005C0G1H080C"))
      (libsource (lib "eagle-import") (part "CAP0402"))
    )
    (comp (ref "C806")
      (value "8p")
      (footprint "eagle-import:0402-CAP")
      (fields (field (name "PARTNO") "C1005C0G1H080C"))
      (libsource (lib "eagle-import") (part "CAP0402"))
    )
    (comp (ref "D801")
      (value "PESD0402-140")
      (footprint "eagle-import:0402-TVS")
      (libsource (lib "eagle-import") (part "DIODE-TVS"))
    )
    (comp (ref "J801")
      (value "JST-ZH-3")
      (footprint "eagle-import:JST-ZH-SMT-VERTICAL")
      (fields (field (name "PARTNO") "B3B-ZR-SM4-TF (LF)(SN)(P)"))
      (libsource (lib "eagle-import") (part "JST-ZH-3"))
    )
    (comp (ref "JX801")
      (value "HEADER-3X1BOARDEDGE-SHORT")
      (footprint "eagle-import:HEADER_3X01_SMD_H_BOARD_EDGE_SHORT")
      (libsource (lib "eagle-import") (part "HEADER-3X1BOARDEDGE-SHORT"))
    )
    (comp (ref "JX802")
      (value "ARM_MINI_JTAG-SMT")
      (footprint "eagle-import:FTSH-105-01-XXX-DV-K")
      (fields (field (name "BOM") "EXCLUDE") (field (name "PARTNO") "M50-3900542"))
      (libsource (lib "eagle-import") (part "ARM_MINI_JTAG-SMT"))
    )
    (comp (ref "R801")
      (value "10K")
      (footprint "eagle-import:0402-RES")
      (fields (field (name "PARTNO") "RC0402FR-0710KL"))
      (libsource (lib "eagle-import") (part "RESISTOR0402-RES"))
    )
    (comp (ref "R802")
      (value "10K")
      (footprint "eagle-import:0402-RES")
      (fields (field (name "PARTNO") "RC0402FR-0710KL"))
      (libsource (lib "eagle-import") (part "RESISTOR0402-RES"))
    )
    (comp (ref "R803")
      (value "220R")
      (footprint "eagle-import:0402-RES")
      (fields (field (name "PARTNO") "RC0402FR-07220RL"))
      (libsource (lib "eagle-import") (part "RESISTOR0402-RES"))
    )
    (comp (ref "R804")
      (value "220R")
      (footprint "eagle-import:0402-RES")
      (fields (field (name "PARTNO") "RC0402FR-07220RL"))
      (libsource (lib "eagle-import") (part "RESISTOR0402-RES"))
    )
    (comp (ref "S801")
      (value "RESET")
      (footprint "eagle-import:EVQP7J01K")
      (fields (field (name "PARTNO") "EVQP7J01K"))
      (libsource (lib "eagle-import") (part "SWITCH-MOMENTARY-2"))
    )
    (comp (ref "U801")
      (value "STM32F10XCXT6")
      (footprint "eagle-import:TQFP48")
      (fields (field (name "PARTNO") "STM32F100C8T6B"))
      (libsource (lib "eagle-import") (part "STM32F10XCXT6"))
    )
    (comp (ref "X801")
      (value "3.2x2.5 mm / 24 MHz / 15 ppm")
      (footprint "eagle-import:OSCILLATOR-3.2X2.5")
      (fields (field (name "PARTNO") "NX3225SA-24.000000MHZ"))
      (libsource (lib "eagle-import") (part "OSCILLATOR-3.2X2.5"))
    )
    (comp (ref "C901")
      (value "0u1")
      (footprint "eagle-import:0402-CAP")
      (fields (field (name "PARTNO") "CC0402ZRY5V7BB104"))
      (libsource (lib "eagle-import") (part "CAP0402"))
    )
    (comp (ref "C902")
      (value "0u1")
      (footprint "eagle-import:0402-CAP")
      (fields (field (name "PARTNO") "CC0402ZRY5V7BB104"))
      (libsource (lib "eagle-import") (part "CAP0402"))
    )
    (comp (ref "C903")
      (value "0u1")
      (footprint "eagle-import:0402-CAP")
      (fields (field (name "PARTNO") "CC0402ZRY5V7BB104"))
      (libsource (lib "eagle-import") (part "CAP0402"))
    )
    (comp (ref "D1")
      (value "MSS1P4-M3")
      (footprint "eagle-import:MICROSMP")
      (fields (field (name "PARTNO") "MSS1P4-M3/89A"))
      (libsource (lib "eagle-import") (part "DIODE-SCHOTTKY_MSMP"))
    )
    (comp (ref "D901")
      (value "PESD0402-140")
      (footprint "eagle-import:0402-TVS")
      (libsource (lib "eagle-import") (part "DIODE-TVS"))
    )
    (comp (ref "D902")
      (value "PESD0402-140")
      (footprint "eagle-import:0402-TVS")
      (libsource (lib "eagle-import") (part "DIODE-TVS"))
    )
    (comp (ref "D903")
      (value "PESD0402-140")
      (footprint "eagle-import:0402-TVS")
      (libsource (lib "eagle-import") (part "DIODE-TVS"))
    )
    (comp (ref "J901")
      (value "HEADER-3X163X16RA")
      (footprint "eagle-import:3X16RA")
      (fields (field (name "BOM") "EXCLUDE"))
      (libsource (lib "eagle-import") (part "HEADER-3X163X16RA"))
    )
    (comp (ref "L901")
      (value "KNH16C104DA5TS")
      (footprint "eagle-import:KYOCERA-KNH16-DA")
      (libsource (lib "eagle-import") (part "KNH16C104DA5TS"))
    )
    (comp (ref "R901")
      (value "10K")
      (footprint "eagle-import:0402-RES")
      (fields (field (name "PARTNO") "RC0402FR-0710KL"))
      (libsource (lib "eagle-import") (part "RESISTOR0402-RES"))
    )
    (comp (ref "R902")
      (value "220R")
      (footprint "eagle-import:0402-RES")
      (fields (field (name "PARTNO") "RC0402FR-07220RL"))
      (libsource (lib "eagle-import") (part "RESISTOR0402-RES"))
    )
    (comp (ref "R903")
      (value "220R")
      (footprint "eagle-import:0402-RES")
      (fields (field (name "PARTNO") "RC0402FR-07220RL"))
      (libsource (lib "eagle-import") (part "RESISTOR0402-RES"))
    )
    (comp (ref "R904")
      (value "220R")
      (footprint "eagle-import:0402-RES")
      (fields (field (name "PARTNO") "RC0402FR-07220RL"))
      (libsource (lib "eagle-import") (part "RESISTOR0402-RES"))
    )
    (comp (ref "R905")
      (value "220R")
      (footprint "eagle-import:0402-RES")
      (fields (field (name "PARTNO") "RC0402FR-07220RL"))
      (libsource (lib "eagle-import") (part "RESISTOR0402-RES"))
    )
    (comp (ref "R906")
      (value "220R")
      (footprint "eagle-import:0402-RES")
      (fields (field (name "PARTNO") "RC0402FR-07220RL"))
      (libsource (lib "eagle-import") (part "RESISTOR0402-RES"))
    )
    (comp (ref "R907")
      (value "220R")
      (footprint "eagle-import:0402-RES")
      (fields (field (name "PARTNO") "RC0402FR-07220RL"))
      (libsource (lib "eagle-import") (part "RESISTOR0402-RES"))
    )
    (comp (ref "R908")
      (value "220R")
      (footprint "eagle-import:0402-RES")
      (fields (field (name "PARTNO") "RC0402FR-07220RL"))
      (libsource (lib "eagle-import") (part "RESISTOR0402-RES"))
    )
    (comp (ref "R909")
      (value "220R")
      (footprint "eagle-import:0402-RES")
      (fields (field (name "PARTNO") "RC0402FR-07220RL"))
      (libsource (lib "eagle-import") (part "RESISTOR0402-RES"))
    )
    (comp (ref "R910")
      (value "220R")
      (footprint "eagle-import:0402-RES")
      (fields (field (name "PARTNO") "RC0402FR-07220RL"))
      (libsource (lib "eagle-import") (part "RESISTOR0402-RES"))
    )
    (comp (ref "R911")
      (value "220R")
      (footprint "eagle-import:0402-RES")
      (fields (field (name "PARTNO") "RC0402FR-07220RL"))
      (libsource (lib "eagle-import") (part "RESISTOR0402-RES"))
    )
    (comp (ref "R912")
      (value "220R")
      (footprint "eagle-import:0402-RES")
      (fields (field (name "PARTNO") "RC0402FR-07220RL"))
      (libsource (lib "eagle-import") (part "RESISTOR0402-RES"))
    )
    (comp (ref "R913")
      (value "220R")
      (footprint "eagle-import:0402-RES")
      (fields (field (name "PARTNO") "RC0402FR-07220RL"))
      (libsource (lib "eagle-import") (part "RESISTOR0402-RES"))
    )
    (comp (ref "R914")
      (value "220R")
      (footprint "eagle-import:0402-RES")
      (fields (field (name "PARTNO") "RC0402FR-07220RL"))
      (libsource (lib "eagle-import") (part "RESISTOR0402-RES"))
    )
    (comp (ref "R915")
      (value "220R")
      (footprint "eagle-import:0402-RES")
      (fields (field (name "PARTNO") "RC0402FR-07220RL"))
      (libsource (lib "eagle-import") (part "RESISTOR0402-RES"))
    )
    (comp (ref "R916")
      (value "220R")
      (footprint "eagle-import:0402-RES")
      (fields (field (name "PARTNO") "RC0402FR-07220RL"))
      (libsource (lib "eagle-import") (part "RESISTOR0402-RES"))
    )
    (comp (ref "R917")
      (value "220R")
      (footprint "eagle-import:0402-RES")
      (fields (field (name "PARTNO") "RC0402FR-07220RL"))
      (libsource (lib "eagle-import") (part "RESISTOR0402-RES"))
    )
    (comp (ref "R918")
      (value "10K/0.1%")
      (footprint "eagle-import:0402-RES")
      (fields (field (name "PARTNO") "ERA-2AEB103X"))
      (libsource (lib "eagle-import") (part "RESISTOR0402-RES"))
    )
    (comp (ref "R919")
      (value "10K/0.1%")
      (footprint "eagle-import:0402-RES")
      (fields (field (name "PARTNO") "ERA-2AEB103X"))
      (libsource (lib "eagle-import") (part "RESISTOR0402-RES"))
    )
    (comp (ref "R922")
      (value "10K/0.1%")
      (footprint "eagle-import:0402-RES")
      (fields (field (name "PARTNO") "ERA-2AEB103X"))
      (libsource (lib "eagle-import") (part "RESISTOR0402-RES"))
    )
    (comp (ref "U901")
      (value "TXS0108QFN20")
      (footprint "eagle-import:QFN20-RGY")
      (fields (field (name "PARTNO") "TXS0108ERGYR"))
      (libsource (lib "eagle-import") (part "TXS0108QFN20"))
    )
    (comp (ref "U902")
      (value "TXS0108QFN20")
      (footprint "eagle-import:QFN20-RGY")
      (fields (field (name "PARTNO") "TXS0108ERGYR"))
      (libsource (lib "eagle-import") (part "TXS0108QFN20"))
    )
    (comp (ref "U903")
      (value "74LVC2G240")
      (footprint "eagle-import:TSSOP8_SOT505-2")
      (fields (field (name "PARTNO") "74LVC2G240DP,125"))
      (libsource (lib "eagle-import") (part "74LVC2G240-TSSOP-8"))
    )
    (comp (ref "C1101")
      (value "22u/25V")
      (footprint "eagle-import:0805-CAP")
      (fields (field (name "PARTNO") "CL21A226MAQNNNE"))
      (libsource (lib "eagle-import") (part "CAP0805"))
    )
    (comp (ref "C1102")
      (value "22u/25V")
      (footprint "eagle-import:0805-CAP")
      (fields (field (name "PARTNO") "CL21A226MAQNNNE"))
      (libsource (lib "eagle-import") (part "CAP0805"))
    )
    (comp (ref "C1103")
      (value "22u/25V")
      (footprint "eagle-import:0805-CAP")
      (fields (field (name "PARTNO") "CL21A226MAQNNNE"))
      (libsource (lib "eagle-import") (part "CAP0805"))
    )
    (comp (ref "C1104")
      (value "100u")
      (footprint "eagle-import:1206-CAP")
      (fields (field (name "PARTNO") "C3216X5R1A107M160AC"))
      (libsource (lib "eagle-import") (part "CAP1206"))
    )
    (comp (ref "C1105")
      (value "0u1")
      (footprint "eagle-import:0402-CAP")
      (fields (field (name "PARTNO") "CC0402ZRY5V7BB104"))
      (libsource (lib "eagle-import") (part "CAP0402"))
    )
    (comp (ref "C1106")
      (value "0u1")
      (footprint "eagle-import:0402-CAP")
      (fields (field (name "PARTNO") "CC0402ZRY5V7BB104"))
      (libsource (lib "eagle-import") (part "CAP0402"))
    )
    (comp (ref "C1107")
      (value "0u1")
      (footprint "eagle-import:0402-CAP")
      (fields (field (name "PARTNO") "CC0402ZRY5V7BB104"))
      (libsource (lib "eagle-import") (part "CAP0402"))
    )
    (comp (ref "C1108")
      (value "1000p/25V")
      (footprint "eagle-import:0402-CAP")
      (fields (field (name "PARTNO") "GRM1555C1E102JA01D"))
      (libsource (lib "eagle-import") (part "CAP0402"))
    )
    (comp (ref "C1109")
      (value "1000p/25V")
      (footprint "eagle-import:0402-CAP")
      (fields (field (name "PARTNO") "GRM1555C1E102JA01D"))
      (libsource (lib "eagle-import") (part "CAP0402"))
    )
    (comp (ref "C1110")
      (value "1000p/25V")
      (footprint "eagle-import:0402-CAP")
      (fields (field (name "PARTNO") "GRM1555C1E102JA01D"))
      (libsource (lib "eagle-import") (part "CAP0402"))
    )
    (comp (ref "J601")
      (value "DF13C-6P-1.25V")
      (footprint "eagle-import:DF13C-6P-1.25V")
      (fields (field (name "PARTNO") "DF13C-6P-1.25V(20)"))
      (libsource (lib "eagle-import") (part "DF13-6P-1.25V"))
    )
    (comp (ref "L1101")
      (value "KNH16C104DA5TS")
      (footprint "eagle-import:KYOCERA-KNH16-DA")
      (libsource (lib "eagle-import") (part "KNH16C104DA5TS"))
    )
    (comp (ref "L1102")
      (value "KNH16C104DA5TS")
      (footprint "eagle-import:KYOCERA-KNH16-DA")
      (libsource (lib "eagle-import") (part "KNH16C104DA5TS"))
    )
    (comp (ref "R1101")
      (value "10K/0.1%")
      (footprint "eagle-import:0402-RES")
      (fields (field (name "PARTNO") "ERA-2AEB103X"))
      (libsource (lib "eagle-import") (part "RESISTOR0402-RES"))
    )
    (comp (ref "R1102")
      (value "10K/0.1%")
      (footprint "eagle-import:0402-RES")
      (fields (field (name "PARTNO") "ERA-2AEB103X"))
      (libsource (lib "eagle-import") (part "RESISTOR0402-RES"))
    )
    (comp (ref "R1103")
      (value "1M")
      (footprint "eagle-import:0402-RES")
      (fields (field (name "PARTNO") "RC0402FR-071ML"))
      (libsource (lib "eagle-import") (part "RESISTOR0402-RES"))
    )
    (comp (ref "R1104")
      (value "1M")
      (footprint "eagle-import:0402-RES")
      (fields (field (name "PARTNO") "RC0402FR-071ML"))
      (libsource (lib "eagle-import") (part "RESISTOR0402-RES"))
    )
    (comp (ref "R1105")
      (value "453K")
      (footprint "eagle-import:0402-RES")
      (fields (field (name "PARTNO") "RMCF0402FT453K"))
      (libsource (lib "eagle-import") (part "RESISTOR0402-RES"))
    )
    (comp (ref "R1106")
      (value "56K")
      (footprint "eagle-import:0402-RES")
      (fields (field (name "PARTNO") "ERA-2AEB563X"))
      (libsource (lib "eagle-import") (part "RESISTOR0402-RES"))
    )
    (comp (ref "R1107")
      (value "105K")
      (footprint "eagle-import:0402-RES")
      (fields (field (name "PARTNO") "ERJ-2RKF1053X"))
      (libsource (lib "eagle-import") (part "RESISTOR0402-RES"))
    )
    (comp (ref "R1109")
      (value "453K")
      (footprint "eagle-import:0402-RES")
      (fields (field (name "PARTNO") "RMCF0402FT453K"))
      (libsource (lib "eagle-import") (part "RESISTOR0402-RES"))
    )
    (comp (ref "R1110")
      (value "56K")
      (footprint "eagle-import:0402-RES")
      (fields (field (name "PARTNO") "ERA-2AEB563X"))
      (libsource (lib "eagle-import") (part "RESISTOR0402-RES"))
    )
    (comp (ref "R1111")
      (value "105K")
      (footprint "eagle-import:0402-RES")
      (fields (field (name "PARTNO") "ERJ-2RKF1053X"))
      (libsource (lib "eagle-import") (part "RESISTOR0402-RES"))
    )
    (comp (ref "R1112")
      (value "453K")
      (footprint "eagle-import:0402-RES")
      (fields (field (name "PARTNO") "RMCF0402FT453K"))
      (libsource (lib "eagle-import") (part "RESISTOR0402-RES"))
    )
    (comp (ref "R1113")
      (value "56K")
      (footprint "eagle-import:0402-RES")
      (fields (field (name "PARTNO") "ERA-2AEB563X"))
      (libsource (lib "eagle-import") (part "RESISTOR0402-RES"))
    )
    (comp (ref "R1114")
      (value "105K")
      (footprint "eagle-import:0402-RES")
      (fields (field (name "PARTNO") "ERJ-2RKF1053X"))
      (libsource (lib "eagle-import") (part "RESISTOR0402-RES"))
    )
    (comp (ref "R1115")
      (value "0R")
      (footprint "eagle-import:0402-RES")
      (fields (field (name "PARTNO") "ERJ-2GE0R00X"))
      (libsource (lib "eagle-import") (part "RESISTOR0402-RES"))
    )
    (comp (ref "RN1101")
      (value "1M")
      (footprint "eagle-import:EXB28V")
      (fields (field (name "PARTNO") "EXB-28V105JX"))
      (libsource (lib "eagle-import") (part "4R-NEXB28V"))
    )
    (comp (ref "U1101")
      (value "LTC4417")
      (footprint "eagle-import:MO-220")
      (fields (field (name "PARTNO") "LTC4417IUF#PBF"))
      (libsource (lib "eagle-import") (part "LTC4117"))
    )
    (comp (ref "U1102")
      (value "NTHD4102PT1G")
      (footprint "eagle-import:1206-8")
      (fields (field (name "PARTNO") "NTHD4102PT1G"))
      (libsource (lib "eagle-import") (part "MOSFET-DUAL-PCHANNEL-CHIPFET"))
    )
    (comp (ref "U1103")
      (value "NTHD4102PT1G")
      (footprint "eagle-import:1206-8")
      (fields (field (name "PARTNO") "NTHD4102PT1G"))
      (libsource (lib "eagle-import") (part "MOSFET-DUAL-PCHANNEL-CHIPFET"))
    )
    (comp (ref "U1104")
      (value "NTHD4102PT1G")
      (footprint "eagle-import:1206-8")
      (fields (field (name "PARTNO") "NTHD4102PT1G"))
      (libsource (lib "eagle-import") (part "MOSFET-DUAL-PCHANNEL-CHIPFET"))
    )
    (comp (ref "C501")
      (value "10u/10V")
      (footprint "eagle-import:0805-CAP")
      (fields (field (name "PARTNO") "CC0805ZKY5V6BB106"))
      (libsource (lib "eagle-import") (part "CAP0805"))
    )
    (comp (ref "C502")
      (value "0u1")
      (footprint "eagle-import:0402-CAP")
      (fields (field (name "PARTNO") "CC0402ZRY5V7BB104"))
      (libsource (lib "eagle-import") (part "CAP0402"))
    )
    (comp (ref "C503")
      (value "0u1")
      (footprint "eagle-import:0402-CAP")
      (fields (field (name "PARTNO") "CC0402ZRY5V7BB104"))
      (libsource (lib "eagle-import") (part "CAP0402"))
    )
    (comp (ref "C504")
      (value "10n")
      (footprint "eagle-import:0402-CAP")
      (fields (field (name "PARTNO") "CC0402KRX7R7BB103"))
      (libsource (lib "eagle-import") (part "CAP0402"))
    )
    (comp (ref "C505")
      (value "10n")
      (footprint "eagle-import:0402-CAP")
      (fields (field (name "PARTNO") "CC0402KRX7R7BB103"))
      (libsource (lib "eagle-import") (part "CAP0402"))
    )
    (comp (ref "C506")
      (value "10u/10V")
      (footprint "eagle-import:0805-CAP")
      (fields (field (name "PARTNO") "CC0805ZKY5V6BB106"))
      (libsource (lib "eagle-import") (part "CAP0805"))
    )
    (comp (ref "C507")
      (value "0u1")
      (footprint "eagle-import:0402-CAP")
      (fields (field (name "PARTNO") "CC0402ZRY5V7BB104"))
      (libsource (lib "eagle-import") (part "CAP0402"))
    )
    (comp (ref "C508")
      (value "0u1")
      (footprint "eagle-import:0402-CAP")
      (fields (field (name "PARTNO") "CC0402ZRY5V7BB104"))
      (libsource (lib "eagle-import") (part "CAP0402"))
    )
    (comp (ref "C509")
      (value "10u/10V")
      (footprint "eagle-import:0805-CAP")
      (fields (field (name "PARTNO") "CC0805ZKY5V6BB106"))
      (libsource (lib "eagle-import") (part "CAP0805"))
    )
    (comp (ref "C510")
      (value "0u47")
      (footprint "eagle-import:0402-CAP")
      (fields (field (name "PARTNO") "C1005X5R1C474K050BC"))
      (libsource (lib "eagle-import") (part "CAP0402"))
    )
    (comp (ref "C511")
      (value "10u/10V")
      (footprint "eagle-import:0805-CAP")
      (fields (field (name "PARTNO") "CC0805ZKY5V6BB106"))
      (libsource (lib "eagle-import") (part "CAP0805"))
    )
    (comp (ref "C512")
      (value "2u2")
      (footprint "eagle-import:0603-CAP")
      (fields (field (name "PARTNO") "CC0402ZRY5V7BB104"))
      (libsource (lib "eagle-import") (part "CAP0603"))
    )
    (comp (ref "C513")
      (value "2u2")
      (footprint "eagle-import:0603-CAP")
      (fields (field (name "PARTNO") "CC0402ZRY5V7BB104"))
      (libsource (lib "eagle-import") (part "CAP0603"))
    )
    (comp (ref "C514")
      (value "0u1")
      (footprint "eagle-import:0402-CAP")
      (fields (field (name "PARTNO") "CC0402ZRY5V7BB104"))
      (libsource (lib "eagle-import") (part "CAP0402"))
    )
    (comp (ref "C515")
      (value "0u01")
      (footprint "eagle-import:0603-CAP")
      (fields (field (name "PARTNO") "GRM155R71E103JA01J"))
      (libsource (lib "eagle-import") (part "CAP0603"))
    )
    (comp (ref "U501")
      (value "L3GD20")
      (footprint "eagle-import:L3G4200DH-MAN")
      (libsource (lib "eagle-import") (part "L3G4200DH-LL"))
    )
    (comp (ref "U502")
      (value "L3GD20H")
      (footprint "eagle-import:LGA-16L")
      (libsource (lib "eagle-import") (part "L3GD20H"))
    )
    (comp (ref "U504")
      (value "LSM303D")
      (footprint "eagle-import:LGA-16L")
      (libsource (lib "eagle-import") (part "LSM303D"))
    )
    (comp (ref "U505")
      (value "MPU-6000")
      (footprint "eagle-import:QFN-24")
      (libsource (lib "eagle-import") (part "MPU-6000"))
    )
    (comp (ref "U506")
      (value "MS5611-01BA")
      (footprint "eagle-import:MS5611-01BA")
      (libsource (lib "eagle-import") (part "MS5611-01BA"))
    )
    (comp (ref "X503")
      (value "0512811094")
      (footprint "eagle-import:51281-1094")
      (fields (field (name "PARTNO") "0781191109"))
      (libsource (lib "eagle-import") (part "CONN_FPC_10RA"))
    )
    (comp (ref "C701")
      (value "0u1")
      (footprint "eagle-import:0402-CAP")
      (fields (field (name "PARTNO") "CC0402ZRY5V7BB104"))
      (libsource (lib "eagle-import") (part "CAP0402"))
    )
    (comp (ref "C702")
      (value "1u0")
      (footprint "eagle-import:0603-CAP")
      (fields (field (name "PARTNO") "CC0603ZRY5V7BB105"))
      (libsource (lib "eagle-import") (part "CAP0603"))
    )
    (comp (ref "C703")
      (value "5n6")
      (footprint "eagle-import:0402-CAP")
      (fields (field (name "PARTNO") "CC0402KRX7R7BB562"))
      (libsource (lib "eagle-import") (part "CAP0402"))
    )
    (comp (ref "C704")
      (value "0u47")
      (footprint "eagle-import:0402-CAP")
      (fields (field (name "PARTNO") "C1005X5R1C474K050BC"))
      (libsource (lib "eagle-import") (part "CAP0402"))
    )
    (comp (ref "D701")
      (value "PESD0402-140")
      (footprint "eagle-import:0402-TVS")
      (libsource (lib "eagle-import") (part "DIODE-TVS"))
    )
    (comp (ref "J701")
      (value "DF13C-2P-1.25V")
      (footprint "eagle-import:DF13C-2P-1.25V")
      (fields (field (name "PARTNO") "DF13C-2P-1.25V(20)"))
      (libsource (lib "eagle-import") (part "DF13-2P-1.25V"))
    )
    (comp (ref "J702")
      (value "DF13C-3P-1.25V")
      (footprint "eagle-import:DF13C-3P-1.25V")
      (fields (field (name "PARTNO") "DF13C-3P-1.25V(20)"))
      (libsource (lib "eagle-import") (part "DF13-3P-1.25V"))
    )
    (comp (ref "L701")
      (value "47uH")
      (footprint "eagle-import:0805-IND")
      (fields (field (name "PARTNO") "MLZ2012M470W"))
      (libsource (lib "eagle-import") (part "INDUCTOR0805"))
    )
    (comp (ref "LED701")
      (value "AMBER")
      (footprint "eagle-import:0603-LED")
      (fields (field (name "PARTNO") "APTD1608SECK"))
      (libsource (lib "eagle-import") (part "LED0603"))
    )
    (comp (ref "LED702")
      (value "GREEN")
      (footprint "eagle-import:0603-LED")
      (fields (field (name "PARTNO") "APTD1608CGCK"))
      (libsource (lib "eagle-import") (part "LED0603"))
    )
    (comp (ref "LED703")
      (value "AMBER")
      (footprint "eagle-import:0603-LED")
      (fields (field (name "PARTNO") "APTD1608SECK"))
      (libsource (lib "eagle-import") (part "LED0603"))
    )
    (comp (ref "LED704")
      (value "GREEN")
      (footprint "eagle-import:0603-LED")
      (fields (field (name "PARTNO") "APTD1608CGCK"))
      (libsource (lib "eagle-import") (part "LED0603"))
    )
    (comp (ref "LED705")
      (value "BLUE")
      (footprint "eagle-import:0603-LED")
      (fields (field (name "PARTNO") "APTD1608QBC/D"))
      (libsource (lib "eagle-import") (part "LED0603"))
    )
    (comp (ref "R3")
      (value "220R")
      (footprint "eagle-import:0402-RES")
      (fields (field (name "PARTNO") "RC0402FR-07220RL"))
      (libsource (lib "eagle-import") (part "RESISTOR0402-RES"))
    )
    (comp (ref "R4")
      (value "220R")
      (footprint "eagle-import:0402-RES")
      (fields (field (name "PARTNO") "RC0402FR-07220RL"))
      (libsource (lib "eagle-import") (part "RESISTOR0402-RES"))
    )
    (comp (ref "R701")
      (value "9K09")
      (footprint "eagle-import:0402-RES")
      (fields (field (name "PARTNO") "RMCF0402FT9K09"))
      (libsource (lib "eagle-import") (part "RESISTOR0402-RES"))
    )
    (comp (ref "R702")
      (value "10K")
      (footprint "eagle-import:0402-RES")
      (fields (field (name "PARTNO") "RC0402FR-0710KL"))
      (libsource (lib "eagle-import") (part "RESISTOR0402-RES"))
    )
    (comp (ref "R703")
      (value "100K")
      (footprint "eagle-import:0402-RES")
      (fields (field (name "PARTNO") "RC0402FR-07100KL"))
      (libsource (lib "eagle-import") (part "RESISTOR0402-RES"))
    )
    (comp (ref "R704")
      (value "10K")
      (footprint "eagle-import:0402-RES")
      (fields (field (name "PARTNO") "RC0402FR-0710KL"))
      (libsource (lib "eagle-import") (part "RESISTOR0402-RES"))
    )
    (comp (ref "R705")
      (value "453K")
      (footprint "eagle-import:0402-RES")
      (fields (field (name "PARTNO") "RMCF0402FT453K"))
      (libsource (lib "eagle-import") (part "RESISTOR0402-RES"))
    )
    (comp (ref "R706")
      (value "16K5")
      (footprint "eagle-import:0402-RES")
      (fields (field (name "PARTNO") "RMCF0402FT16K5"))
      (libsource (lib "eagle-import") (part "RESISTOR0402-RES"))
    )
    (comp (ref "R707")
      (value "220R")
      (footprint "eagle-import:0402-RES")
      (fields (field (name "PARTNO") "RC0402FR-07220RL"))
      (libsource (lib "eagle-import") (part "RESISTOR0402-RES"))
    )
    (comp (ref "R708")
      (value "220R")
      (footprint "eagle-import:0402-RES")
      (fields (field (name "PARTNO") "RC0402FR-07220RL"))
      (libsource (lib "eagle-import") (part "RESISTOR0402-RES"))
    )
    (comp (ref "R709")
      (value "220R")
      (footprint "eagle-import:0402-RES")
      (fields (field (name "PARTNO") "RC0402FR-07220RL"))
      (libsource (lib "eagle-import") (part "RESISTOR0402-RES"))
    )
    (comp (ref "R710")
      (value "68R")
      (footprint "eagle-import:0402-RES")
      (fields (field (name "PARTNO") "ERJ-2GEJ680X"))
      (libsource (lib "eagle-import") (part "RESISTOR0402-RES"))
    )
    (comp (ref "R711")
      (value "220R")
      (footprint "eagle-import:0402-RES")
      (fields (field (name "PARTNO") "RC0402FR-07220RL"))
      (libsource (lib "eagle-import") (part "RESISTOR0402-RES"))
    )
    (comp (ref "R712")
      (value "220R")
      (footprint "eagle-import:0402-RES")
      (fields (field (name "PARTNO") "RC0402FR-07220RL"))
      (libsource (lib "eagle-import") (part "RESISTOR0402-RES"))
    )
    (comp (ref "R713")
      (value "1K5")
      (footprint "eagle-import:0402-RES")
      (fields (field (name "PARTNO") "RC0402FR-071K5L"))
      (libsource (lib "eagle-import") (part "RESISTOR0402-RES"))
    )
    (comp (ref "U701")
      (value "TCA62724FMG")
      (footprint "eagle-import:SON10")
      (libsource (lib "eagle-import") (part "TCA62724FMG"))
    )
    (comp (ref "U702")
      (value "LT3469")
      (footprint "eagle-import:SOT23-8")
      (fields (field (name "PARTNO") "LT3469ETS8"))
      (libsource (lib "eagle-import") (part "LT3469"))
    )
    (comp (ref "U703")
      (value "LRTB GFTG-T7AW-1+V7A7-29+R5T9-49-L")
      (footprint "eagle-import:6-PLCC")
      (fields (field (name "PARTNO") "LRTB GFTG-T7AW-1+V7A7-29+R5T9-49-L"))
      (libsource (lib "eagle-import") (part "RGB-LED6-PLCC"))
    )
    (comp (ref "C401")
      (value "0u1")
      (footprint "eagle-import:0402-CAP")
      (fields (field (name "PARTNO") "CC0402ZRY5V7BB104"))
      (libsource (lib "eagle-import") (part "CAP0402"))
    )
    (comp (ref "C402")
      (value "0u1")
      (footprint "eagle-import:0402-CAP")
      (fields (field (name "PARTNO") "CC0402ZRY5V7BB104"))
      (libsource (lib "eagle-import") (part "CAP0402"))
    )
    (comp (ref "D401")
      (value "PESD0402-140")
      (footprint "eagle-import:0402-TVS")
      (libsource (lib "eagle-import") (part "DIODE-TVS"))
    )
    (comp (ref "D402")
      (value "PESD0402-140")
      (footprint "eagle-import:0402-TVS")
      (libsource (lib "eagle-import") (part "DIODE-TVS"))
    )
    (comp (ref "D403")
      (value "PESD0402-140")
      (footprint "eagle-import:0402-TVS")
      (libsource (lib "eagle-import") (part "DIODE-TVS"))
    )
    (comp (ref "D404")
      (value "PESD0402-140")
      (footprint "eagle-import:0402-TVS")
      (libsource (lib "eagle-import") (part "DIODE-TVS"))
    )
    (comp (ref "J401")
      (value "DF13C-4P-1.25V")
      (footprint "eagle-import:DF13C-4P-1.25V")
      (fields (field (name "PARTNO") "DF13C-4P-1.25V(20)"))
      (libsource (lib "eagle-import") (part "DF13-4P-1.25V"))
    )
    (comp (ref "J402")
      (value "DF13C-3P-1.25V")
      (footprint "eagle-import:DF13C-3P-1.25V")
      (fields (field (name "PARTNO") "DF13C-3P-1.25V(20)"))
      (libsource (lib "eagle-import") (part "DF13-3P-1.25V"))
    )
    (comp (ref "J403")
      (value "DF13C-7P-1.25V")
      (footprint "eagle-import:DF13C-7P-1.25V")
      (fields (field (name "PARTNO") "DF13C-7P-1.25V(20)"))
      (libsource (lib "eagle-import") (part "DF13-7P-1.25V"))
    )
    (comp (ref "J404")
      (value "DF13C-5P-1.25V")
      (footprint "eagle-import:DF13C-5P-1.25V")
      (fields (field (name "PARTNO") "DF13C-5P-1.25V(20)"))
      (libsource (lib "eagle-import") (part "DF13-5P-1.25V"))
    )
    (comp (ref "J405")
      (value "DF13C-4P-1.25V")
      (footprint "eagle-import:DF13C-4P-1.25V")
      (fields (field (name "PARTNO") "DF13C-4P-1.25V(20)"))
      (libsource (lib "eagle-import") (part "DF13-4P-1.25V"))
    )
    (comp (ref "L401")
      (value "KNH16C104DA5TS")
      (footprint "eagle-import:KYOCERA-KNH16-DA")
      (libsource (lib "eagle-import") (part "KNH16C104DA5TS"))
    )
    (comp (ref "L402")
      (value "KNH16C104DA5TS")
      (footprint "eagle-import:KYOCERA-KNH16-DA")
      (libsource (lib "eagle-import") (part "KNH16C104DA5TS"))
    )
    (comp (ref "L403")
      (value "KNH16C104DA5TS")
      (footprint "eagle-import:KYOCERA-KNH16-DA")
      (libsource (lib "eagle-import") (part "KNH16C104DA5TS"))
    )
    (comp (ref "L404")
      (value "KNH16C104DA5TS")
      (footprint "eagle-import:KYOCERA-KNH16-DA")
      (libsource (lib "eagle-import") (part "KNH16C104DA5TS"))
    )
    (comp (ref "R401")
      (value "1K5")
      (footprint "eagle-import:0402-RES")
      (fields (field (name "PARTNO") "RC0402FR-071K5L"))
      (libsource (lib "eagle-import") (part "RESISTOR0402-RES"))
    )
    (comp (ref "R402")
      (value "1K5")
      (footprint "eagle-import:0402-RES")
      (fields (field (name "PARTNO") "RC0402FR-071K5L"))
      (libsource (lib "eagle-import") (part "RESISTOR0402-RES"))
    )
    (comp (ref "R403")
      (value "10K/0.1%")
      (footprint "eagle-import:0402-RES")
      (fields (field (name "PARTNO") "ERA-2AEB103X"))
      (libsource (lib "eagle-import") (part "RESISTOR0402-RES"))
    )
    (comp (ref "R404")
      (value "120R")
      (footprint "eagle-import:0402-RES")
      (fields (field (name "PARTNO") "RC0402FR-07120RL"))
      (libsource (lib "eagle-import") (part "RESISTOR0402-RES"))
    )
    (comp (ref "R405")
      (value "120R")
      (footprint "eagle-import:0402-RES")
      (fields (field (name "PARTNO") "RC0402FR-07120RL"))
      (libsource (lib "eagle-import") (part "RESISTOR0402-RES"))
    )
    (comp (ref "R406")
      (value "10K/0.1%")
      (footprint "eagle-import:0402-RES")
      (fields (field (name "PARTNO") "ERA-2AEB103X"))
      (libsource (lib "eagle-import") (part "RESISTOR0402-RES"))
    )
    (comp (ref "R407")
      (value "10K/0.1%")
      (footprint "eagle-import:0402-RES")
      (fields (field (name "PARTNO") "ERA-2AEB103X"))
      (libsource (lib "eagle-import") (part "RESISTOR0402-RES"))
    )
    (comp (ref "R408")
      (value "10K/0.1%")
      (footprint "eagle-import:0402-RES")
      (fields (field (name "PARTNO") "ERA-2AEB103X"))
      (libsource (lib "eagle-import") (part "RESISTOR0402-RES"))
    )
    (comp (ref "R409")
      (value "120R")
      (footprint "eagle-import:0402-RES")
      (fields (field (name "PARTNO") "RC0402FR-07120RL"))
      (libsource (lib "eagle-import") (part "RESISTOR0402-RES"))
    )
    (comp (ref "U401")
      (value "MAX3051")
      (footprint "eagle-import:SOT23-8")
      (fields (field (name "PARTNO") "MAX3051EKA"))
      (libsource (lib "eagle-import") (part "MAX3051MAX3051EKA"))
    )
    (comp (ref "C101")
      (value "0u1")
      (footprint "eagle-import:0402-CAP")
      (fields (field (name "PARTNO") "CC0402ZRY5V7BB104"))
      (libsource (lib "eagle-import") (part "CAP0402"))
    )
    (comp (ref "C102")
      (value "8p")
      (footprint "eagle-import:0402-CAP")
      (fields (field (name "PARTNO") "C1005C0G1H080C"))
      (libsource (lib "eagle-import") (part "CAP0402"))
    )
    (comp (ref "C103")
      (value "8p")
      (footprint "eagle-import:0402-CAP")
      (fields (field (name "PARTNO") "C1005C0G1H080C"))
      (libsource (lib "eagle-import") (part "CAP0402"))
    )
    (comp (ref "R101")
      (value "470R")
      (footprint "eagle-import:0402-RES")
      (fields (field (name "PARTNO") "RC0402FR-07470RL"))
      (libsource (lib "eagle-import") (part "RESISTOR0402-RES"))
    )
    (comp (ref "R102")
      (value "10K")
      (footprint "eagle-import:0402-RES")
      (fields (field (name "PARTNO") "RC0402FR-0710KL"))
      (libsource (lib "eagle-import") (part "RESISTOR0402-RES"))
    )
    (comp (ref "U101")
      (value "STM32F4X7VX")
      (footprint "eagle-import:TQFP100")
      (fields (field (name "PARTNO") "STM32F427VI"))
      (libsource (lib "eagle-import") (part "STM32F4X7VX"))
    )
    (comp (ref "U102")
      (value "FM25V01")
      (footprint "eagle-import:SO08")
      (fields (field (name "PARTNO") "FM25V01-G"))
      (libsource (lib "eagle-import") (part "FM25V01"))
    )
    (comp (ref "X101")
      (value "3.2x2.5 mm / 24 MHz / 15 ppm")
      (footprint "eagle-import:OSCILLATOR-3.2X2.5")
      (fields (field (name "PARTNO") "NX3225SA-24.000000MHZ"))
      (libsource (lib "eagle-import") (part "OSCILLATOR-3.2X2.5"))
    )
    (comp (ref "!VBUS_VALID")
      (value "PAD.04")
      (footprint "eagle-import:PAD.04X.04")
      (libsource (lib "eagle-import") (part "PAD.04"))
    )
    (comp (ref "!VDD_BRICK_VALID")
      (value "PAD.04")
      (footprint "eagle-import:PAD.04X.04")
      (libsource (lib "eagle-import") (part "PAD.04"))
    )
    (comp (ref "!VDD_SERVO_VALID")
      (value "PAD.04")
      (footprint "eagle-import:PAD.04X.04")
      (libsource (lib "eagle-import") (part "PAD.04"))
    )
    (comp (ref "ADC_PR")
      (value "PAD.04")
      (footprint "eagle-import:PAD.04X.04")
      (libsource (lib "eagle-import") (part "PAD.04"))
    )
    (comp (ref "CAN_H")
      (value "PAD.04")
      (footprint "eagle-import:PAD.04X.04")
      (libsource (lib "eagle-import") (part "PAD.04"))
    )
    (comp (ref "CAN_L")
      (value "PAD.04")
      (footprint "eagle-import:PAD.04X.04")
      (libsource (lib "eagle-import") (part "PAD.04"))
    )
    (comp (ref "FMU-BOOT1101")
      (value "PAD.04")
      (footprint "eagle-import:PAD.04X.04")
      (libsource (lib "eagle-import") (part "PAD.04"))
    )
    (comp (ref "GND")
      (value "PAD.04")
      (footprint "eagle-import:PAD.04X.04")
      (libsource (lib "eagle-import") (part "PAD.04"))
    )
    (comp (ref "GND.")
      (value "PAD.04")
      (footprint "eagle-import:PAD.04X.04")
      (libsource (lib "eagle-import") (part "PAD.04"))
    )
    (comp (ref "IO-BOOT1101")
      (value "PAD.04")
      (footprint "eagle-import:PAD.04X.04")
      (libsource (lib "eagle-import") (part "PAD.04"))
    )
    (comp (ref "JP1")
      (value "FIDUCIAL1.5X3")
      (footprint "eagle-import:FIDUCIAL-1.5X3")
      (libsource (lib "eagle-import") (part "FIDUCIAL1.5X3"))
    )
    (comp (ref "JP2")
      (value "FIDUCIAL1.5X3")
      (footprint "eagle-import:FIDUCIAL-1.5X3")
      (libsource (lib "eagle-import") (part "FIDUCIAL1.5X3"))
    )
    (comp (ref "M3_MOUNT1101")
      (value "MOUNT-HOLE3.1MM")
      (footprint "eagle-import:MOUNT-HOLE3.1")
      (libsource (lib "eagle-import") (part "MOUNT-HOLE3.1MM"))
    )
    (comp (ref "M3_MOUNT1102")
      (value "MOUNT-HOLE3.1MM")
      (footprint "eagle-import:MOUNT-HOLE3.1")
      (libsource (lib "eagle-import") (part "MOUNT-HOLE3.1MM"))
    )
    (comp (ref "M3_MOUNT1103")
      (value "MOUNT-HOLE3.1MM")
      (footprint "eagle-import:MOUNT-HOLE3.1")
      (libsource (lib "eagle-import") (part "MOUNT-HOLE3.1MM"))
    )
    (comp (ref "M3_MOUNT1104")
      (value "MOUNT-HOLE3.1MM")
      (footprint "eagle-import:MOUNT-HOLE3.1")
      (libsource (lib "eagle-import") (part "MOUNT-HOLE3.1MM"))
    )
    (comp (ref "OSHW_LOGO")
      (value "OSHW-LOGOS")
      (footprint "eagle-import:OSHW-LOGO-S")
      (libsource (lib "eagle-import") (part "OSHW-LOGOS"))
    )
    (comp (ref "S1RX")
      (value "PAD.04")
      (footprint "eagle-import:PAD.04X.04")
      (libsource (lib "eagle-import") (part "PAD.04"))
    )
    (comp (ref "S1TX")
      (value "PAD.04")
      (footprint "eagle-import:PAD.04X.04")
      (libsource (lib "eagle-import") (part "PAD.04"))
    )
    (comp (ref "S2RX")
      (value "PAD.04")
      (footprint "eagle-import:PAD.04X.04")
      (libsource (lib "eagle-import") (part "PAD.04"))
    )
    (comp (ref "S2TX")
      (value "PAD.04")
      (footprint "eagle-import:PAD.04X.04")
      (libsource (lib "eagle-import") (part "PAD.04"))
    )
    (comp (ref "S3RX")
      (value "PAD.04")
      (footprint "eagle-import:PAD.04X.04")
      (libsource (lib "eagle-import") (part "PAD.04"))
    )
    (comp (ref "S3TX")
      (value "PAD.04")
      (footprint "eagle-import:PAD.04X.04")
      (libsource (lib "eagle-import") (part "PAD.04"))
    )
    (comp (ref "S4RX")
      (value "PAD.04")
      (footprint "eagle-import:PAD.04X.04")
      (libsource (lib "eagle-import") (part "PAD.04"))
    )
    (comp (ref "S4TX")
      (value "PAD.04")
      (footprint "eagle-import:PAD.04X.04")
      (libsource (lib "eagle-import") (part "PAD.04"))
    )
    (comp (ref "S5_RX")
      (value "PAD.04")
      (footprint "eagle-import:PAD.04X.04")
      (libsource (lib "eagle-import") (part "PAD.04"))
    )
    (comp (ref "S5_TX")
      (value "PAD.04")
      (footprint "eagle-import:PAD.04X.04")
      (libsource (lib "eagle-import") (part "PAD.04"))
    )
    (comp (ref "VBUS")
      (value "PAD.04")
      (footprint "eagle-import:PAD.04X.04")
      (libsource (lib "eagle-import") (part "PAD.04"))
    )
    (comp (ref "VDDA_3V1101")
      (value "PAD.04")
      (footprint "eagle-import:PAD.04X.04")
      (libsource (lib "eagle-import") (part "PAD.04"))
    )
    (comp (ref "VDD_3V1101")
      (value "PAD.04")
      (footprint "eagle-import:PAD.04X.04")
      (libsource (lib "eagle-import") (part "PAD.04"))
    )
    (comp (ref "VDD_5V_BRICK")
      (value "PAD.04")
      (footprint "eagle-import:PAD.04X.04")
      (libsource (lib "eagle-import") (part "PAD.04"))
    )
    (comp (ref "VDD_5V_IN")
      (value "PAD.04")
      (footprint "eagle-import:PAD.04X.04")
      (libsource (lib "eagle-import") (part "PAD.04"))
    )
    (comp (ref "VDD_SERVO")
      (value "PAD.04")
      (footprint "eagle-import:PAD.04X.04")
      (libsource (lib "eagle-import") (part "PAD.04"))
    )
    (comp (ref "C1001")
      (value "10u/25V")
      (footprint "eagle-import:0805-CAP")
      (fields (field (name "PARTNO") "CL21A106KAYNNNE"))
      (libsource (lib "eagle-import") (part "CAP0805"))
    )
    (comp (ref "C1002")
      (value "10n")
      (footprint "eagle-import:0402-CAP")
      (fields (field (name "PARTNO") "CC0402KRX7R7BB103"))
      (libsource (lib "eagle-import") (part "CAP0402"))
    )
    (comp (ref "C1003")
      (value "1u0")
      (footprint "eagle-import:0603-CAP")
      (fields (field (name "PARTNO") "CC0603ZRY5V7BB105"))
      (libsource (lib "eagle-import") (part "CAP0603"))
    )
    (comp (ref "C1004")
      (value "10u")
      (footprint "eagle-import:0603-CAP")
      (fields (field (name "PARTNO") "CC0603ZRY5V7BB105"))
      (libsource (lib "eagle-import") (part "CAP0603"))
    )
    (comp (ref "C1005")
      (value "0u1F")
      (footprint "eagle-import:0402-CAP")
      (fields (field (name "PARTNO") "CC0402ZRY5V7BB104"))
      (libsource (lib "eagle-import") (part "CAP0402"))
    )
    (comp (ref "C1008")
      (value "2u2")
      (footprint "eagle-import:0402-CAP")
      (fields (field (name "PARTNO") "CC0603ZRY5V7BB105"))
      (libsource (lib "eagle-import") (part "CAP0402"))
    )
    (comp (ref "D1001")
      (value "PMEG2005CT")
      (footprint "eagle-import:SOT23-3")
      (libsource (lib "eagle-import") (part "PMEG2005CT"))
    )
    (comp (ref "F1001")
      (value "0ZCA0035FF2G")
      (footprint "eagle-import:PTC-1206")
      (libsource (lib "eagle-import") (part "PTCSMD"))
    )
    (comp (ref "R1001")
      (value "100K")
      (footprint "eagle-import:0402-RES")
      (fields (field (name "PARTNO") "RC0402FR-07100KL"))
      (libsource (lib "eagle-import") (part "RESISTOR0402-RES"))
    )
    (comp (ref "R1002")
      (value "10K")
      (footprint "eagle-import:0402-RES")
      (fields (field (name "PARTNO") "RC0402FR-0710KL"))
      (libsource (lib "eagle-import") (part "RESISTOR0402-RES"))
    )
    (comp (ref "U1001")
      (value "BQ24313")
      (footprint "eagle-import:QFN8-DSG")
      (fields (field (name "PARTNO") "BQ24313DSGT"))
      (libsource (lib "eagle-import") (part "BQ24313"))
    )
    (comp (ref "U1002")
      (value "MIC5332")
      (footprint "eagle-import:MLF-8-EPAD")
      (fields (field (name "PARTNO") "MIC5332-SSYMT"))
      (libsource (lib "eagle-import") (part "MIC5332"))
    )
    (comp (ref "J301")
      (value "47346-0001")
      (footprint "eagle-import:MOLEX-47346-0001")
      (libsource (lib "eagle-import") (part "MOLEX-47346-0001"))
    )
    (comp (ref "J302")
      (value "DF13C-4P-1.25V")
      (footprint "eagle-import:DF13C-4P-1.25V")
      (fields (field (name "PARTNO") "DF13C-4P-1.25V(20)"))
      (libsource (lib "eagle-import") (part "DF13-4P-1.25V"))
    )
    (comp (ref "JX301")
      (value "ARM_MINI_JTAG-SMT")
      (footprint "eagle-import:FTSH-105-01-XXX-DV-K")
      (fields (field (name "BOM") "EXCLUDE") (field (name "PARTNO") "M50-3900542"))
      (libsource (lib "eagle-import") (part "ARM_MINI_JTAG-SMT"))
    )
    (comp (ref "R301")
      (value "100K")
      (footprint "eagle-import:0402-RES")
      (fields (field (name "PARTNO") "RC0402FR-07100KL"))
      (libsource (lib "eagle-import") (part "RESISTOR0402-RES"))
    )
    (comp (ref "R302")
      (value "100K")
      (footprint "eagle-import:0402-RES")
      (fields (field (name "PARTNO") "RC0402FR-07100KL"))
      (libsource (lib "eagle-import") (part "RESISTOR0402-RES"))
    )
    (comp (ref "R303")
      (value "100K")
      (footprint "eagle-import:0402-RES")
      (fields (field (name "PARTNO") "RC0402FR-07100KL"))
      (libsource (lib "eagle-import") (part "RESISTOR0402-RES"))
    )
    (comp (ref "R304")
      (value "100K")
      (footprint "eagle-import:0402-RES")
      (fields (field (name "PARTNO") "RC0402FR-07100KL"))
      (libsource (lib "eagle-import") (part "RESISTOR0402-RES"))
    )
    (comp (ref "R305")
      (value "100K")
      (footprint "eagle-import:0402-RES")
      (fields (field (name "PARTNO") "RC0402FR-07100KL"))
      (libsource (lib "eagle-import") (part "RESISTOR0402-RES"))
    )
    (comp (ref "R306")
      (value "1K5")
      (footprint "eagle-import:0402-RES")
      (fields (field (name "PARTNO") "RC0402FR-071K5L"))
      (libsource (lib "eagle-import") (part "RESISTOR0402-RES"))
    )
    (comp (ref "R307")
      (value "1K5")
      (footprint "eagle-import:0402-RES")
      (fields (field (name "PARTNO") "RC0402FR-071K5L"))
      (libsource (lib "eagle-import") (part "RESISTOR0402-RES"))
    )
    (comp (ref "U301")
      (value "2908-05WB-MG")
      (footprint "eagle-import:MICROSD")
      (libsource (lib "eagle-import") (part "MICROSDSDI"))
    )
    (comp (ref "U302")
      (value "NUF2042XV6")
      (footprint "eagle-import:SOT563-6")
      (fields (field (name "PARTNO") "NUF2042XV6T1G"))
      (libsource (lib "eagle-import") (part "NUF2042XV6"))
    )
    (comp (ref "C201")
      (value "0u1")
      (footprint "eagle-import:0402-CAP")
      (fields (field (name "PARTNO") "CC0402ZRY5V7BB104"))
      (libsource (lib "eagle-import") (part "CAP0402"))
    )
    (comp (ref "C202")
      (value "0u1")
      (footprint "eagle-import:0402-CAP")
      (fields (field (name "PARTNO") "CC0402ZRY5V7BB104"))
      (libsource (lib "eagle-import") (part "CAP0402"))
    )
    (comp (ref "D201")
      (value "PESD0402-140")
      (footprint "eagle-import:0402-TVS")
      (libsource (lib "eagle-import") (part "DIODE-TVS"))
    )
    (comp (ref "D202")
      (value "PESD0402-140")
      (footprint "eagle-import:0402-TVS")
      (libsource (lib "eagle-import") (part "DIODE-TVS"))
    )
    (comp (ref "D203")
      (value "PESD0402-140")
      (footprint "eagle-import:0402-TVS")
      (libsource (lib "eagle-import") (part "DIODE-TVS"))
    )
    (comp (ref "J201")
      (value "DF13C-6P-1.25V")
      (footprint "eagle-import:DF13C-6P-1.25V")
      (fields (field (name "PARTNO") "DF13C-6P-1.25V(20)"))
      (libsource (lib "eagle-import") (part "DF13-6P-1.25V"))
    )
    (comp (ref "J202")
      (value "DF13C-6P-1.25V")
      (footprint "eagle-import:DF13C-6P-1.25V")
      (fields (field (name "PARTNO") "DF13C-6P-1.25V(20)"))
      (libsource (lib "eagle-import") (part "DF13-6P-1.25V"))
    )
    (comp (ref "J203")
      (value "DF13C-6P-1.25V")
      (footprint "eagle-import:DF13C-6P-1.25V")
      (fields (field (name "PARTNO") "DF13C-6P-1.25V(20)"))
      (libsource (lib "eagle-import") (part "DF13-6P-1.25V"))
    )
    (comp (ref "J204")
      (value "DF13C-6P-1.25V")
      (footprint "eagle-import:DF13C-6P-1.25V")
      (fields (field (name "PARTNO") "DF13C-6P-1.25V(20)"))
      (libsource (lib "eagle-import") (part "DF13-6P-1.25V"))
    )
    (comp (ref "L201")
      (value "KNH16C104DA5TS")
      (footprint "eagle-import:KYOCERA-KNH16-DA")
      (libsource (lib "eagle-import") (part "KNH16C104DA5TS"))
    )
    (comp (ref "L202")
      (value "KNH16C104DA5TS")
      (footprint "eagle-import:KYOCERA-KNH16-DA")
      (libsource (lib "eagle-import") (part "KNH16C104DA5TS"))
    )
    (comp (ref "L203")
      (value "KNH16C104DA5TS")
      (footprint "eagle-import:KYOCERA-KNH16-DA")
      (libsource (lib "eagle-import") (part "KNH16C104DA5TS"))
    )
    (comp (ref "R201")
      (value "120R")
      (footprint "eagle-import:0402-RES")
      (fields (field (name "PARTNO") "RC0402FR-07120RL"))
      (libsource (lib "eagle-import") (part "RESISTOR0402-RES"))
    )
    (comp (ref "R202")
      (value "120R")
      (footprint "eagle-import:0402-RES")
      (fields (field (name "PARTNO") "RC0402FR-07120RL"))
      (libsource (lib "eagle-import") (part "RESISTOR0402-RES"))
    )
    (comp (ref "R203")
      (value "120R")
      (footprint "eagle-import:0402-RES")
      (fields (field (name "PARTNO") "RC0402FR-07120RL"))
      (libsource (lib "eagle-import") (part "RESISTOR0402-RES"))
    )
    (comp (ref "R204")
      (value "120R")
      (footprint "eagle-import:0402-RES")
      (fields (field (name "PARTNO") "RC0402FR-07120RL"))
      (libsource (lib "eagle-import") (part "RESISTOR0402-RES"))
    )
    (comp (ref "R205")
      (value "120R")
      (footprint "eagle-import:0402-RES")
      (fields (field (name "PARTNO") "RC0402FR-07120RL"))
      (libsource (lib "eagle-import") (part "RESISTOR0402-RES"))
    )
    (comp (ref "R206")
      (value "120R")
      (footprint "eagle-import:0402-RES")
      (fields (field (name "PARTNO") "RC0402FR-07120RL"))
      (libsource (lib "eagle-import") (part "RESISTOR0402-RES"))
    )
    (comp (ref "R207")
      (value "120R")
      (footprint "eagle-import:0402-RES")
      (fields (field (name "PARTNO") "RC0402FR-07120RL"))
      (libsource (lib "eagle-import") (part "RESISTOR0402-RES"))
    )
    (comp (ref "R208")
      (value "120R")
      (footprint "eagle-import:0402-RES")
      (fields (field (name "PARTNO") "RC0402FR-07120RL"))
      (libsource (lib "eagle-import") (part "RESISTOR0402-RES"))
    )
    (comp (ref "R209")
      (value "120R")
      (footprint "eagle-import:0402-RES")
      (fields (field (name "PARTNO") "RC0402FR-07120RL"))
      (libsource (lib "eagle-import") (part "RESISTOR0402-RES"))
    )
    (comp (ref "R210")
      (value "120R")
      (footprint "eagle-import:0402-RES")
      (fields (field (name "PARTNO") "RC0402FR-07120RL"))
      (libsource (lib "eagle-import") (part "RESISTOR0402-RES"))
    )
    (comp (ref "R211")
      (value "120R")
      (footprint "eagle-import:0402-RES")
      (fields (field (name "PARTNO") "RC0402FR-07120RL"))
      (libsource (lib "eagle-import") (part "RESISTOR0402-RES"))
    )
    (comp (ref "R212")
      (value "120R")
      (footprint "eagle-import:0402-RES")
      (fields (field (name "PARTNO") "RC0402FR-07120RL"))
      (libsource (lib "eagle-import") (part "RESISTOR0402-RES"))
    )
    (comp (ref "R213")
      (value "120R")
      (footprint "eagle-import:0402-RES")
      (fields (field (name "PARTNO") "RC0402FR-07120RL"))
      (libsource (lib "eagle-import") (part "RESISTOR0402-RES"))
    )
    (comp (ref "R214")
      (value "120R")
      (footprint "eagle-import:0402-RES")
      (fields (field (name "PARTNO") "RC0402FR-07120RL"))
      (libsource (lib "eagle-import") (part "RESISTOR0402-RES"))
    )
    (comp (ref "R215")
      (value "120R")
      (footprint "eagle-import:0402-RES")
      (fields (field (name "PARTNO") "RC0402FR-07120RL"))
      (libsource (lib "eagle-import") (part "RESISTOR0402-RES"))
    )
    (comp (ref "R216")
      (value "120R")
      (footprint "eagle-import:0402-RES")
      (fields (field (name "PARTNO") "RC0402FR-07120RL"))
      (libsource (lib "eagle-import") (part "RESISTOR0402-RES"))
    )
    (comp (ref "U201")
      (value "TXS0108QFN20")
      (footprint "eagle-import:QFN20-RGY")
      (fields (field (name "PARTNO") "TXS0108ERGYR"))
      (libsource (lib "eagle-import") (part "TXS0108QFN20"))
    )
    (comp (ref "U202")
      (value "TXS0108QFN20")
      (footprint "eagle-import:QFN20-RGY")
      (fields (field (name "PARTNO") "TXS0108ERGYR"))
      (libsource (lib "eagle-import") (part "TXS0108QFN20"))
    )
    (comp (ref "B601")
      (value "MS621FE")
      (footprint "eagle-import:MS621FE")
      (fields (field (name "PARTNO") "MS621FE-FL11E"))
      (libsource (lib "eagle-import") (part "MS621FE"))
    )
    (comp (ref "C601")
      (value "10u/25V")
      (footprint "eagle-import:0805-CAP")
      (fields (field (name "PARTNO") "CL21A106KAYNNNE"))
      (libsource (lib "eagle-import") (part "CAP0805"))
    )
    (comp (ref "C602")
      (value "10n")
      (footprint "eagle-import:0402-CAP")
      (fields (field (name "PARTNO") "CC0402KRX7R7BB103"))
      (libsource (lib "eagle-import") (part "CAP0402"))
    )
    (comp (ref "C603")
      (value "1u")
      (footprint "eagle-import:0603-CAP")
      (fields (field (name "PARTNO") "CC0603ZRY5V7BB105"))
      (libsource (lib "eagle-import") (part "CAP0603"))
    )
    (comp (ref "C604")
      (value "22u/25V")
      (footprint "eagle-import:0805-CAP")
      (fields (field (name "PARTNO") "CL21A226MAQNNNE"))
      (libsource (lib "eagle-import") (part "CAP0805"))
    )
    (comp (ref "C605")
      (value "22u/25V")
      (footprint "eagle-import:0805-CAP")
      (fields (field (name "PARTNO") "CL21A226MAQNNNE"))
      (libsource (lib "eagle-import") (part "CAP0805"))
    )
    (comp (ref "C606")
      (value "0u1")
      (footprint "eagle-import:0402-CAP")
      (fields (field (name "PARTNO") "CC0402ZRY5V7BB104"))
      (libsource (lib "eagle-import") (part "CAP0402"))
    )
    (comp (ref "C607")
      (value "0u1")
      (footprint "eagle-import:0402-CAP")
      (fields (field (name "PARTNO") "CC0402ZRY5V7BB104"))
      (libsource (lib "eagle-import") (part "CAP0402"))
    )
    (comp (ref "C608")
      (value "0u1")
      (footprint "eagle-import:0402-CAP")
      (fields (field (name "PARTNO") "CC0402ZRY5V7BB104"))
      (libsource (lib "eagle-import") (part "CAP0402"))
    )
    (comp (ref "C609")
      (value "0u1")
      (footprint "eagle-import:0402-CAP")
      (fields (field (name "PARTNO") "CC0402ZRY5V7BB104"))
      (libsource (lib "eagle-import") (part "CAP0402"))
    )
    (comp (ref "C610")
      (value "0u1")
      (footprint "eagle-import:0402-CAP")
      (fields (field (name "PARTNO") "CC0402ZRY5V7BB104"))
      (libsource (lib "eagle-import") (part "CAP0402"))
    )
    (comp (ref "C611")
      (value "2u2")
      (footprint "eagle-import:0603-CAP")
      (fields (field (name "PARTNO") "C1608Y5V1C225Z"))
      (libsource (lib "eagle-import") (part "CAP0603"))
    )
    (comp (ref "C612")
      (value "0u1")
      (footprint "eagle-import:0402-CAP")
      (fields (field (name "PARTNO") "CC0402ZRY5V7BB104"))
      (libsource (lib "eagle-import") (part "CAP0402"))
    )
    (comp (ref "C613")
      (value "2u2")
      (footprint "eagle-import:0603-CAP")
      (fields (field (name "PARTNO") "C1608Y5V1C225Z"))
      (libsource (lib "eagle-import") (part "CAP0603"))
    )
    (comp (ref "C614")
      (value "100u")
      (footprint "eagle-import:1206-CAP")
      (fields (field (name "PARTNO") "C3216X5R1A107M160AC"))
      (libsource (lib "eagle-import") (part "CAP1206"))
    )
    (comp (ref "C615")
      (value "0u1")
      (footprint "eagle-import:0402-CAP")
      (fields (field (name "PARTNO") "CC0402ZRY5V7BB104"))
      (libsource (lib "eagle-import") (part "CAP0402"))
    )
    (comp (ref "C616")
      (value "0u1")
      (footprint "eagle-import:0402-CAP")
      (fields (field (name "PARTNO") "CC0402ZRY5V7BB104"))
      (libsource (lib "eagle-import") (part "CAP0402"))
    )
    (comp (ref "C617")
      (value "0u1")
      (footprint "eagle-import:0402-CAP")
      (fields (field (name "PARTNO") "CC0402ZRY5V7BB104"))
      (libsource (lib "eagle-import") (part "CAP0402"))
    )
    (comp (ref "C618")
      (value "100u")
      (footprint "eagle-import:1206-CAP")
      (fields (field (name "PARTNO") "C3216X5R1A107M160AC"))
      (libsource (lib "eagle-import") (part "CAP1206"))
    )
    (comp (ref "D2")
      (value "RB751V40T1G")
      (footprint "eagle-import:SOD323")
      (libsource (lib "eagle-import") (part "DIODE-SCHOTTKY_SOD323"))
    )
    (comp (ref "L603")
      (value "KNH16C104DA5TS")
      (footprint "eagle-import:KYOCERA-KNH16-DA")
      (libsource (lib "eagle-import") (part "KNH16C104DA5TS"))
    )
    (comp (ref "Q601")
      (value "MMBT3906LT1SMD")
      (footprint "eagle-import:SOT23-BEC")
      (fields (field (name "PARTNO") "MMBT 3906 LT1"))
      (libsource (lib "eagle-import") (part "MMBT3906SMDLT1"))
    )
    (comp (ref "R602")
      (value "1M")
      (footprint "eagle-import:0402-RES")
      (fields (field (name "PARTNO") "RC0402FR-071ML"))
      (libsource (lib "eagle-import") (part "RESISTOR0402-RES"))
    )
    (comp (ref "R603")
      (value "10k")
      (footprint "eagle-import:0402-RES")
      (fields (field (name "PARTNO") "RC0402FR-0710KL"))
      (libsource (lib "eagle-import") (part "RESISTOR0402-RES"))
    )
    (comp (ref "R604")
      (value "1M")
      (footprint "eagle-import:0402-RES")
      (fields (field (name "PARTNO") "RC0402FR-071ML"))
      (libsource (lib "eagle-import") (part "RESISTOR0402-RES"))
    )
    (comp (ref "R608")
      (value "1K")
      (footprint "eagle-import:0402-RES")
      (fields (field (name "PARTNO") "RC0402FR-071KL"))
      (libsource (lib "eagle-import") (part "RESISTOR0402-RES"))
    )
    (comp (ref "R609")
      (value "10K/0.1%")
      (footprint "eagle-import:0402-RES")
      (fields (field (name "PARTNO") "ERA-2AEB103X"))
      (libsource (lib "eagle-import") (part "RESISTOR0402-RES"))
    )
    (comp (ref "R610")
      (value "10K/0.1%")
      (footprint "eagle-import:0402-RES")
      (fields (field (name "PARTNO") "ERA-2AEB103X"))
      (libsource (lib "eagle-import") (part "RESISTOR0402-RES"))
    )
    (comp (ref "R611")
      (value "10K")
      (footprint "eagle-import:0402-RES")
      (fields (field (name "PARTNO") "RC0402FR-0710KL"))
      (libsource (lib "eagle-import") (part "RESISTOR0402-RES"))
    )
    (comp (ref "R615")
      (value "10K")
      (footprint "eagle-import:0402-RES")
      (fields (field (name "PARTNO") "RC0402FR-0710KL"))
      (libsource (lib "eagle-import") (part "RESISTOR0402-RES"))
    )
    (comp (ref "R616")
      (value "25K5")
      (footprint "eagle-import:0402-RES")
      (fields (field (name "PARTNO") "RMCF0402FT25K5"))
      (libsource (lib "eagle-import") (part "RESISTOR0402-RES"))
    )
    (comp (ref "R617")
      (value "16K5")
      (footprint "eagle-import:0402-RES")
      (fields (field (name "PARTNO") "RMCF0402FT16K5"))
      (libsource (lib "eagle-import") (part "RESISTOR0402-RES"))
    )
    (comp (ref "R620")
      (value "1k8")
      (footprint "eagle-import:0402-RES")
      (fields (field (name "PARTNO") "RC1005F182CS"))
      (libsource (lib "eagle-import") (part "RESISTOR0402-RES"))
    )
    (comp (ref "R621")
      (value "10R")
      (footprint "eagle-import:0603-RES")
      (fields (field (name "PARTNO") "RC1608J100CS"))
      (libsource (lib "eagle-import") (part "RESISTOR0603-RES"))
    )
    (comp (ref "R635")
      (value "DNP / 10k")
      (footprint "eagle-import:0402-RES")
      (fields (field (name "PARTNO") "RC0402FR-0710KL"))
      (libsource (lib "eagle-import") (part "RESISTOR0402-RES"))
    )
    (comp (ref "S601")
      (value "RESET")
      (footprint "eagle-import:EVQP7J01K")
      (fields (field (name "PARTNO") "EVQP7J01K"))
      (libsource (lib "eagle-import") (part "SWITCH-MOMENTARY-2"))
    )
    (comp (ref "U601")
      (value "BQ24315")
      (footprint "eagle-import:QFN8-DSG")
      (fields (field (name "PARTNO") "BQ24315DSGR"))
      (libsource (lib "eagle-import") (part "BQ24315"))
    )
    (comp (ref "U602")
      (value "BQ24315")
      (footprint "eagle-import:QFN8-DSG")
      (fields (field (name "PARTNO") "BQ24315DSGR"))
      (libsource (lib "eagle-import") (part "BQ24315"))
    )
    (comp (ref "U603")
      (value "MIC5332")
      (footprint "eagle-import:MLF-8-EPAD")
      (fields (field (name "PARTNO") "MIC5332-SSYMT"))
      (libsource (lib "eagle-import") (part "MIC5332"))
    )
  )
  (nets
    (net (code "1") (name "ACCEL_DRDY") (class "Default")
      (node (ref "U101") (pin "90") (pinfunction "PB4_90") (pintype "bidirectional"))
      (node (ref "U504") (pin "11") (pinfunction "INT1_11") (pintype "bidirectional"))
      (node (ref "X503") (pin "3") (pinfunction "S_3") (pintype "passive"))
    )
    (net (code "2") (name "ALARM") (class "Default")
      (node (ref "R701") (pin "P$2") (pinfunction "2_P$2") (pintype "passive"))
      (node (ref "U101") (pin "77") (pinfunction "PA15_77") (pintype "bidirectional"))
    )
    (net (code "3") (name "BATT_CURRENT_SENS") (class "Default")
      (node (ref "R1101") (pin "P$1") (pinfunction "1_P$1") (pintype "passive"))
      (node (ref "U101") (pin "26") (pinfunction "PA3_26") (pintype "bidirectional"))
    )
    (net (code "4") (name "BATT_VOLTAGE_SENS") (class "Default")
      (node (ref "R1102") (pin "P$1") (pinfunction "1_P$1") (pintype "passive"))
      (node (ref "U101") (pin "25") (pinfunction "PA2_25") (pintype "bidirectional"))
    )
    (net (code "5") (name "CAN1_RX") (class "Default")
      (node (ref "U101") (pin "81") (pinfunction "PD0_81") (pintype "bidirectional"))
      (node (ref "U401") (pin "4") (pinfunction "DOUT_4") (pintype "output"))
    )
    (net (code "6") (name "CAN1_TX") (class "Default")
      (node (ref "U101") (pin "82") (pinfunction "PD1_82") (pintype "bidirectional"))
      (node (ref "U401") (pin "1") (pinfunction "DIN_1") (pintype "input"))
    )
    (net (code "7") (name "CAN2_RX") (class "Default")
      (node (ref "R216") (pin "P$1") (pinfunction "1_P$1") (pintype "passive"))
      (node (ref "U101") (pin "51") (pinfunction "PB12_51") (pintype "bidirectional"))
    )
    (net (code "8") (name "CAN2_TX") (class "Default")
      (node (ref "R215") (pin "P$1") (pinfunction "1_P$1") (pintype "passive"))
      (node (ref "U101") (pin "92") (pinfunction "PB6_92") (pintype "bidirectional"))
    )
    (net (code "9") (name "CAN_H") (class "Default")
      (node (ref "CAN_H") (pin "P$1") (pinfunction "P$1_P$1") (pintype "passive"))
      (node (ref "J405") (pin "2") (pinfunction "2_2") (pintype "passive"))
      (node (ref "R409") (pin "P$1") (pinfunction "1_P$1") (pintype "passive"))
      (node (ref "U401") (pin "7") (pinfunction "CANH_7") (pintype "bidirectional"))
    )
    (net (code "10") (name "CAN_L") (class "Default")
      (node (ref "CAN_L") (pin "P$1") (pinfunction "P$1_P$1") (pintype "passive"))
      (node (ref "J405") (pin "3") (pinfunction "3_3") (pintype "passive"))
      (node (ref "R409") (pin "P$2") (pinfunction "2_P$2") (pintype "passive"))
      (node (ref "U401") (pin "6") (pinfunction "CANL_6") (pintype "bidirectional"))
    )
    (net (code "11") (name "FMU-BOOT0") (class "Default")
      (node (ref "FMU-BOOT1101") (pin "P$1") (pinfunction "P$1_P$1") (pintype "passive"))
      (node (ref "R611") (pin "P$2") (pinfunction "2_P$2") (pintype "passive"))
      (node (ref "U101") (pin "94") (pinfunction "BOOT0_94") (pintype "input"))
    )
    (net (code "12") (name "FMU-CH1") (class "Default")
      (node (ref "U101") (pin "45") (pinfunction "PE14_45") (pintype "bidirectional"))
      (node (ref "U901") (pin "7") (pinfunction "A6_7") (pintype "bidirectional"))
    )
    (net (code "13") (name "FMU-CH2") (class "Default")
      (node (ref "U101") (pin "44") (pinfunction "PE13_44") (pintype "bidirectional"))
      (node (ref "U901") (pin "6") (pinfunction "A5_6") (pintype "bidirectional"))
    )
    (net (code "14") (name "FMU-CH3") (class "Default")
      (node (ref "U101") (pin "42") (pinfunction "PE11_42") (pintype "bidirectional"))
      (node (ref "U901") (pin "5") (pinfunction "A4_5") (pintype "bidirectional"))
    )
    (net (code "15") (name "FMU-CH4") (class "Default")
      (node (ref "U101") (pin "40") (pinfunction "PE9_40") (pintype "bidirectional"))
      (node (ref "U901") (pin "4") (pinfunction "A3_4") (pintype "bidirectional"))
    )
    (net (code "16") (name "FMU-CH5") (class "Default")
      (node (ref "U101") (pin "60") (pinfunction "PD13_60") (pintype "bidirectional"))
      (node (ref "U901") (pin "3") (pinfunction "A2_3") (pintype "bidirectional"))
    )
    (net (code "17") (name "FMU-CH6") (class "Default")
      (node (ref "U101") (pin "61") (pinfunction "PD14_61") (pintype "bidirectional"))
      (node (ref "U901") (pin "1") (pinfunction "A1_1") (pintype "bidirectional"))
    )
    (net (code "18") (name "FMU-I2C1_SCL") (class "Default")
      (node (ref "R401") (pin "P$1") (pinfunction "1_P$1") (pintype "passive"))
      (node (ref "R404") (pin "P$1") (pinfunction "1_P$1") (pintype "passive"))
      (node (ref "U101") (pin "95") (pinfunction "PB8_95") (pintype "bidirectional"))
    )
    (net (code "19") (name "FMU-I2C1_SDA") (class "Default")
      (node (ref "R402") (pin "P$1") (pinfunction "1_P$1") (pintype "passive"))
      (node (ref "R405") (pin "P$1") (pinfunction "1_P$1") (pintype "passive"))
      (node (ref "U101") (pin "96") (pinfunction "PB9_96") (pintype "bidirectional"))
    )
    (net (code "20") (name "FMU-I2C2_SCL") (class "Default")
      (node (ref "R306") (pin "P$1") (pinfunction "1_P$1") (pintype "passive"))
      (node (ref "U101") (pin "47") (pinfunction "PB10_47") (pintype "bidirectional"))
      (node (ref "U701") (pin "3") (pinfunction "SCL_3") (pintype "bidirectional"))
    )
    (net (code "21") (name "FMU-I2C2_SDA") (class "Default")
      (node (ref "R307") (pin "P$1") (pinfunction "1_P$1") (pintype "passive"))
      (node (ref "U101") (pin "48") (pinfunction "PB11_48") (pintype "bidirectional"))
      (node (ref "U701") (pin "2") (pinfunction "SDA_2") (pintype "bidirectional"))
    )
    (net (code "22") (name "FMU-SWCLK") (class "Default")
      (node (ref "JX301") (pin "4") (pinfunction "S_4") (pintype "passive"))
      (node (ref "U101") (pin "76") (pinfunction "PA14_76") (pintype "bidirectional"))
    )
    (net (code "23") (name "FMU-SWDIO") (class "Default")
      (node (ref "JX301") (pin "2") (pinfunction "S_2") (pintype "passive"))
      (node (ref "U101") (pin "72") (pinfunction "PA13_72") (pintype "bidirectional"))
    )
    (net (code "24") (name "FMU-SWO") (class "Default")
      (node (ref "JX301") (pin "6") (pinfunction "S_6") (pintype "passive"))
      (node (ref "U101") (pin "89") (pinfunction "PB3_89") (pintype "bidirectional"))
    )
    (net (code "25") (name "FMU-UART4_RX") (class "Default")
      (node (ref "U101") (pin "24") (pinfunction "PA1_24") (pintype "bidirectional"))
      (node (ref "U202") (pin "8") (pinfunction "A7_8") (pintype "bidirectional"))
    )
    (net (code "26") (name "FMU-UART4_TX") (class "Default")
      (node (ref "U101") (pin "23") (pinfunction "PA0_23") (pintype "bidirectional"))
      (node (ref "U202") (pin "9") (pinfunction "A8_9") (pintype "bidirectional"))
    )
    (net (code "27") (name "FMU-UART7_RX") (class "Default")
      (node (ref "U101") (pin "38") (pinfunction "PE7_38") (pintype "bidirectional"))
      (node (ref "U202") (pin "4") (pinfunction "A3_4") (pintype "bidirectional"))
    )
    (net (code "28") (name "FMU-UART7_TX") (class "Default")
      (node (ref "U101") (pin "39") (pinfunction "PE8_39") (pintype "bidirectional"))
      (node (ref "U202") (pin "5") (pinfunction "A4_5") (pintype "bidirectional"))
    )
    (net (code "29") (name "FMU-UART8_RX") (class "Default")
      (node (ref "U101") (pin "97") (pinfunction "PE0_97") (pintype "bidirectional"))
      (node (ref "U202") (pin "6") (pinfunction "A5_6") (pintype "bidirectional"))
    )
    (net (code "30") (name "FMU-UART8_TX") (class "Default")
      (node (ref "U101") (pin "98") (pinfunction "PE1_98") (pintype "bidirectional"))
      (node (ref "U202") (pin "7") (pinfunction "A6_7") (pintype "bidirectional"))
    )
    (net (code "31") (name "FMU-USART2_CTS") (class "Default")
      (node (ref "U101") (pin "84") (pinfunction "PD3_84") (pintype "bidirectional"))
      (node (ref "U201") (pin "9") (pinfunction "A8_9") (pintype "bidirectional"))
    )
    (net (code "32") (name "FMU-USART2_RTS") (class "Default")
      (node (ref "U101") (pin "85") (pinfunction "PD4_85") (pintype "bidirectional"))
      (node (ref "U201") (pin "8") (pinfunction "A7_8") (pintype "bidirectional"))
    )
    (net (code "33") (name "FMU-USART2_RX") (class "Default")
      (node (ref "U101") (pin "87") (pinfunction "PD6_87") (pintype "bidirectional"))
      (node (ref "U201") (pin "6") (pinfunction "A5_6") (pintype "bidirectional"))
    )
    (net (code "34") (name "FMU-USART2_TX") (class "Default")
      (node (ref "U101") (pin "86") (pinfunction "PD5_86") (pintype "bidirectional"))
      (node (ref "U201") (pin "7") (pinfunction "A6_7") (pintype "bidirectional"))
    )
    (net (code "35") (name "FMU-USART3_CTS") (class "Default")
      (node (ref "U101") (pin "58") (pinfunction "PD11_58") (pintype "bidirectional"))
      (node (ref "U201") (pin "3") (pinfunction "A2_3") (pintype "bidirectional"))
    )
    (net (code "36") (name "FMU-USART3_RTS") (class "Default")
      (node (ref "U101") (pin "59") (pinfunction "PD12_59") (pintype "bidirectional"))
      (node (ref "U201") (pin "1") (pinfunction "A1_1") (pintype "bidirectional"))
    )
    (net (code "37") (name "FMU-USART3_RX") (class "Default")
      (node (ref "U101") (pin "56") (pinfunction "PD9_56") (pintype "bidirectional"))
      (node (ref "U201") (pin "4") (pinfunction "A3_4") (pintype "bidirectional"))
    )
    (net (code "38") (name "FMU-USART3_TX") (class "Default")
      (node (ref "U101") (pin "55") (pinfunction "PD8_55") (pintype "bidirectional"))
      (node (ref "U201") (pin "5") (pinfunction "A4_5") (pintype "bidirectional"))
    )
    (net (code "39") (name "FMU-VDD_3V3") (class "Default")
      (node (ref "C101") (pin "P$1") (pinfunction "1_P$1") (pintype "passive"))
      (node (ref "C201") (pin "P$1") (pinfunction "1_P$1") (pintype "passive"))
      (node (ref "C202") (pin "P$1") (pinfunction "1_P$1") (pintype "passive"))
      (node (ref "C402") (pin "P$1") (pinfunction "1_P$1") (pintype "passive"))
      (node (ref "C603") (pin "P$1") (pinfunction "1_P$1") (pintype "passive"))
      (node (ref "C604") (pin "P$1") (pinfunction "1_P$1") (pintype "passive"))
      (node (ref "C606") (pin "P$1") (pinfunction "1_P$1") (pintype "passive"))
      (node (ref "C607") (pin "P$1") (pinfunction "1_P$1") (pintype "passive"))
      (node (ref "C608") (pin "P$1") (pinfunction "1_P$1") (pintype "passive"))
      (node (ref "C610") (pin "P$1") (pinfunction "1_P$1") (pintype "passive"))
      (node (ref "C612") (pin "P$1") (pinfunction "1_P$1") (pintype "passive"))
      (node (ref "C616") (pin "P$1") (pinfunction "1_P$1") (pintype "passive"))
      (node (ref "C701") (pin "P$1") (pinfunction "1_P$1") (pintype "passive"))
      (node (ref "C902") (pin "P$1") (pinfunction "1_P$1") (pintype "passive"))
      (node (ref "D2") (pin "A") (pinfunction "A_A") (pintype "passive"))
      (node (ref "JX301") (pin "1") (pinfunction "S_1") (pintype "passive"))
      (node (ref "R301") (pin "P$2") (pinfunction "2_P$2") (pintype "passive"))
      (node (ref "R302") (pin "P$2") (pinfunction "2_P$2") (pintype "passive"))
      (node (ref "R303") (pin "P$2") (pinfunction "2_P$2") (pintype "passive"))
      (node (ref "R304") (pin "P$2") (pinfunction "2_P$2") (pintype "passive"))
      (node (ref "R305") (pin "P$2") (pinfunction "2_P$2") (pintype "passive"))
      (node (ref "R306") (pin "P$2") (pinfunction "2_P$2") (pintype "passive"))
      (node (ref "R307") (pin "P$2") (pinfunction "2_P$2") (pintype "passive"))
      (node (ref "R401") (pin "P$2") (pinfunction "2_P$2") (pintype "passive"))
      (node (ref "R402") (pin "P$2") (pinfunction "2_P$2") (pintype "passive"))
      (node (ref "R602") (pin "P$2") (pinfunction "2_P$2") (pintype "passive"))
      (node (ref "R604") (pin "P$2") (pinfunction "2_P$2") (pintype "passive"))
      (node (ref "U101") (pin "100") (pinfunction "VDD_100") (pintype "power_in"))
      (node (ref "U101") (pin "11") (pinfunction "VDD_11") (pintype "power_in"))
      (node (ref "U101") (pin "19") (pinfunction "VDD_19") (pintype "power_in"))
      (node (ref "U101") (pin "21") (pinfunction "VREF+_21") (pintype "input"))
      (node (ref "U101") (pin "22") (pinfunction "VDDA_22") (pintype "power_in"))
      (node (ref "U101") (pin "28") (pinfunction "VDD_28") (pintype "power_in"))
      (node (ref "U101") (pin "50") (pinfunction "VDD_50") (pintype "power_in"))
      (node (ref "U101") (pin "75") (pinfunction "VDD_75") (pintype "power_in"))
      (node (ref "U102") (pin "3") (pinfunction "~{W}_3") (pintype "bidirectional"))
      (node (ref "U102") (pin "7") (pinfunction "~{HOLD}_7") (pintype "bidirectional"))
      (node (ref "U102") (pin "8") (pinfunction "VDD_8") (pintype "bidirectional"))
      (node (ref "U201") (pin "10") (pinfunction "OE_10") (pintype "input"))
      (node (ref "U201") (pin "19") (pinfunction "VCCB_19") (pintype "input"))
      (node (ref "U201") (pin "2") (pinfunction "VCCA_2") (pintype "input"))
      (node (ref "U202") (pin "10") (pinfunction "OE_10") (pintype "input"))
      (node (ref "U202") (pin "19") (pinfunction "VCCB_19") (pintype "input"))
      (node (ref "U202") (pin "2") (pinfunction "VCCA_2") (pintype "input"))
      (node (ref "U301") (pin "4") (pinfunction "VCC_4") (pintype "passive"))
      (node (ref "U401") (pin "3") (pinfunction "VCC_3") (pintype "input"))
      (node (ref "U603") (pin "7") (pinfunction "VOUT2_7") (pintype "bidirectional"))
      (node (ref "U701") (pin "1") (pinfunction "~{SHDN}_1") (pintype "input"))
      (node (ref "U701") (pin "10") (pinfunction "VIN_10") (pintype "power_in"))
      (node (ref "U901") (pin "10") (pinfunction "OE_10") (pintype "input"))
      (node (ref "U901") (pin "19") (pinfunction "VCCB_19") (pintype "input"))
      (node (ref "U901") (pin "2") (pinfunction "VCCA_2") (pintype "input"))
      (node (ref "VDD_3V1101") (pin "P$1") (pinfunction "P$1_P$1") (pintype "passive"))
    )
    (net (code "40") (name "FMU-~{RESET}") (class "Default")
      (node (ref "C609") (pin "P$2") (pinfunction "2_P$2") (pintype "passive"))
      (node (ref "R635") (pin "P$1") (pinfunction "1_P$1") (pintype "passive"))
      (node (ref "S601") (pin "A1") (pinfunction "1_A1") (pintype "passive"))
      (node (ref "U101") (pin "14") (pinfunction "NRST_14") (pintype "input"))
      (node (ref "U603") (pin "3") (pinfunction "POR2_3") (pintype "bidirectional"))
      (node (ref "U701") (pin "4") (pinfunction "~{RESET}_4") (pintype "input"))
    )
    (net (code "41") (name "FMU_AUX_ADC1") (class "Default")
      (node (ref "R408") (pin "P$1") (pinfunction "1_P$1") (pintype "passive"))
      (node (ref "U101") (pin "18") (pinfunction "PC3_18") (pintype "bidirectional"))
    )
    (net (code "42") (name "FMU_AUX_ADC2") (class "Default")
      (node (ref "R407") (pin "P$1") (pinfunction "1_P$1") (pintype "passive"))
      (node (ref "U101") (pin "33") (pinfunction "PC4_33") (pintype "bidirectional"))
    )
    (net (code "43") (name "FRAM_MISO") (class "Default")
      (node (ref "U101") (pin "53") (pinfunction "PB14_53") (pintype "bidirectional"))
      (node (ref "U102") (pin "2") (pinfunction "Q_2") (pintype "bidirectional"))
    )
    (net (code "44") (name "FRAM_MOSI") (class "Default")
      (node (ref "U101") (pin "54") (pinfunction "PB15_54") (pintype "bidirectional"))
      (node (ref "U102") (pin "5") (pinfunction "D_5") (pintype "bidirectional"))
    )
    (net (code "45") (name "FRAM_SCK") (class "Default")
      (node (ref "U101") (pin "52") (pinfunction "PB13_52") (pintype "bidirectional"))
      (node (ref "U102") (pin "6") (pinfunction "C_6") (pintype "bidirectional"))
    )
    (net (code "46") (name "GND") (class "Default")
      (node (ref "B601") (pin "2") (pinfunction "NEG_2") (pintype "bidirectional"))
      (node (ref "C1001") (pin "P$2") (pinfunction "2_P$2") (pintype "passive"))
      (node (ref "C1002") (pin "P$2") (pinfunction "2_P$2") (pintype "passive"))
      (node (ref "C1003") (pin "P$2") (pinfunction "2_P$2") (pintype "passive"))
      (node (ref "C1004") (pin "P$2") (pinfunction "2_P$2") (pintype "passive"))
      (node (ref "C1005") (pin "P$2") (pinfunction "2_P$2") (pintype "passive"))
      (node (ref "C1008") (pin "P$2") (pinfunction "2_P$2") (pintype "passive"))
      (node (ref "C101") (pin "P$2") (pinfunction "2_P$2") (pintype "passive"))
      (node (ref "C102") (pin "P$2") (pinfunction "2_P$2") (pintype "passive"))
      (node (ref "C103") (pin "P$1") (pinfunction "1_P$1") (pintype "passive"))
      (node (ref "C1101") (pin "P$2") (pinfunction "2_P$2") (pintype "passive"))
      (node (ref "C1102") (pin "P$2") (pinfunction "2_P$2") (pintype "passive"))
      (node (ref "C1103") (pin "P$2") (pinfunction "2_P$2") (pintype "passive"))
      (node (ref "C1104") (pin "P$2") (pinfunction "2_P$2") (pintype "passive"))
      (node (ref "C1105") (pin "P$2") (pinfunction "2_P$2") (pintype "passive"))
      (node (ref "C1106") (pin "P$2") (pinfunction "2_P$2") (pintype "passive"))
      (node (ref "C1107") (pin "P$2") (pinfunction "2_P$2") (pintype "passive"))
      (node (ref "C1108") (pin "P$2") (pinfunction "2_P$2") (pintype "passive"))
      (node (ref "C1109") (pin "P$2") (pinfunction "2_P$2") (pintype "passive"))
      (node (ref "C1110") (pin "P$2") (pinfunction "2_P$2") (pintype "passive"))
      (node (ref "C201") (pin "P$2") (pinfunction "2_P$2") (pintype "passive"))
      (node (ref "C202") (pin "P$2") (pinfunction "2_P$2") (pintype "passive"))
      (node (ref "C401") (pin "P$2") (pinfunction "2_P$2") (pintype "passive"))
      (node (ref "C402") (pin "P$2") (pinfunction "2_P$2") (pintype "passive"))
      (node (ref "C501") (pin "P$2") (pinfunction "2_P$2") (pintype "passive"))
      (node (ref "C502") (pin "P$2") (pinfunction "2_P$2") (pintype "passive"))
      (node (ref "C503") (pin "P$2") (pinfunction "2_P$2") (pintype "passive"))
      (node (ref "C504") (pin "P$2") (pinfunction "2_P$2") (pintype "passive"))
      (node (ref "C505") (pin "P$2") (pinfunction "2_P$2") (pintype "passive"))
      (node (ref "C506") (pin "P$2") (pinfunction "2_P$2") (pintype "passive"))
      (node (ref "C507") (pin "P$2") (pinfunction "2_P$2") (pintype "passive"))
      (node (ref "C508") (pin "P$2") (pinfunction "2_P$2") (pintype "passive"))
      (node (ref "C509") (pin "P$2") (pinfunction "2_P$2") (pintype "passive"))
      (node (ref "C511") (pin "P$2") (pinfunction "2_P$2") (pintype "passive"))
      (node (ref "C512") (pin "P$2") (pinfunction "2_P$2") (pintype "passive"))
      (node (ref "C513") (pin "P$2") (pinfunction "2_P$2") (pintype "passive"))
      (node (ref "C514") (pin "P$2") (pinfunction "2_P$2") (pintype "passive"))
      (node (ref "C515") (pin "P$2") (pinfunction "2_P$2") (pintype "passive"))
      (node (ref "C601") (pin "P$2") (pinfunction "2_P$2") (pintype "passive"))
      (node (ref "C602") (pin "P$1") (pinfunction "1_P$1") (pintype "passive"))
      (node (ref "C603") (pin "P$2") (pinfunction "2_P$2") (pintype "passive"))
      (node (ref "C604") (pin "P$2") (pinfunction "2_P$2") (pintype "passive"))
      (node (ref "C605") (pin "P$2") (pinfunction "2_P$2") (pintype "passive"))
      (node (ref "C606") (pin "P$2") (pinfunction "2_P$2") (pintype "passive"))
      (node (ref "C607") (pin "P$2") (pinfunction "2_P$2") (pintype "passive"))
      (node (ref "C608") (pin "P$2") (pinfunction "2_P$2") (pintype "passive"))
      (node (ref "C609") (pin "P$1") (pinfunction "1_P$1") (pintype "passive"))
      (node (ref "C610") (pin "P$2") (pinfunction "2_P$2") (pintype "passive"))
      (node (ref "C611") (pin "P$2") (pinfunction "2_P$2") (pintype "passive"))
      (node (ref "C612") (pin "P$2") (pinfunction "2_P$2") (pintype "passive"))
      (node (ref "C613") (pin "P$2") (pinfunction "2_P$2") (pintype "passive"))
      (node (ref "C614") (pin "P$2") (pinfunction "2_P$2") (pintype "passive"))
      (node (ref "C615") (pin "P$2") (pinfunction "2_P$2") (pintype "passive"))
      (node (ref "C616") (pin "P$2") (pinfunction "2_P$2") (pintype "passive"))
      (node (ref "C617") (pin "P$2") (pinfunction "2_P$2") (pintype "passive"))
      (node (ref "C618") (pin "P$2") (pinfunction "2_P$2") (pintype "passive"))
      (node (ref "C701") (pin "P$2") (pinfunction "2_P$2") (pintype "passive"))
      (node (ref "C702") (pin "P$2") (pinfunction "2_P$2") (pintype "passive"))
      (node (ref "C703") (pin "P$2") (pinfunction "2_P$2") (pintype "passive"))
      (node (ref "C704") (pin "P$2") (pinfunction "2_P$2") (pintype "passive"))
      (node (ref "C801") (pin "P$1") (pinfunction "1_P$1") (pintype "passive"))
      (node (ref "C802") (pin "P$2") (pinfunction "2_P$2") (pintype "passive"))
      (node (ref "C803") (pin "P$2") (pinfunction "2_P$2") (pintype "passive"))
      (node (ref "C804") (pin "P$2") (pinfunction "2_P$2") (pintype "passive"))
      (node (ref "C805") (pin "P$2") (pinfunction "2_P$2") (pintype "passive"))
      (node (ref "C806") (pin "P$1") (pinfunction "1_P$1") (pintype "passive"))
      (node (ref "C901") (pin "P$2") (pinfunction "2_P$2") (pintype "passive"))
      (node (ref "C902") (pin "P$2") (pinfunction "2_P$2") (pintype "passive"))
      (node (ref "C903") (pin "P$2") (pinfunction "2_P$2") (pintype "passive"))
      (node (ref "D201") (pin "A") (pinfunction "A_A") (pintype "passive"))
      (node (ref "D202") (pin "A") (pinfunction "A_A") (pintype "passive"))
      (node (ref "D203") (pin "A") (pinfunction "A_A") (pintype "passive"))
      (node (ref "D401") (pin "A") (pinfunction "A_A") (pintype "passive"))
      (node (ref "D402") (pin "A") (pinfunction "A_A") (pintype "passive"))
      (node (ref "D403") (pin "A") (pinfunction "A_A") (pintype "passive"))
      (node (ref "D404") (pin "A") (pinfunction "A_A") (pintype "passive"))
      (node (ref "D701") (pin "A") (pinfunction "A_A") (pintype "passive"))
      (node (ref "D801") (pin "A") (pinfunction "A_A") (pintype "passive"))
      (node (ref "D901") (pin "A") (pinfunction "A_A") (pintype "passive"))
      (node (ref "D902") (pin "A") (pinfunction "A_A") (pintype "passive"))
      (node (ref "D903") (pin "A") (pinfunction "A_A") (pintype "passive"))
      (node (ref "GND") (pin "P$1") (pinfunction "P$1_P$1") (pintype "passive"))
      (node (ref "GND.") (pin "P$1") (pinfunction "P$1_P$1") (pintype "passive"))
      (node (ref "J201") (pin "6") (pinfunction "6_6") (pintype "passive"))
      (node (ref "J202") (pin "6") (pinfunction "6_6") (pintype "passive"))
      (node (ref "J203") (pin "6") (pinfunction "6_6") (pintype "passive"))
      (node (ref "J204") (pin "6") (pinfunction "6_6") (pintype "passive"))
      (node (ref "J301") (pin "GND") (pinfunction "5_GND") (pintype "power_in"))
      (node (ref "J301") (pin "GND1") (pinfunction "GND1_GND1") (pintype "bidirectional"))
      (node (ref "J301") (pin "GND2") (pinfunction "GND2_GND2") (pintype "bidirectional"))
      (node (ref "J301") (pin "GND3") (pinfunction "GND3_GND3") (pintype "bidirectional"))
      (node (ref "J301") (pin "GND4") (pinfunction "GND4_GND4") (pintype "bidirectional"))
      (node (ref "J302") (pin "4") (pinfunction "4_4") (pintype "passive"))
      (node (ref "J401") (pin "4") (pinfunction "4_4") (pintype "passive"))
      (node (ref "J402") (pin "3") (pinfunction "3_3") (pintype "passive"))
      (node (ref "J403") (pin "7") (pinfunction "7_7") (pintype "passive"))
      (node (ref "J404") (pin "3") (pinfunction "3_3") (pintype "passive"))
      (node (ref "J404") (pin "5") (pinfunction "5_5") (pintype "passive"))
      (node (ref "J405") (pin "4") (pinfunction "4_4") (pintype "passive"))
      (node (ref "J601") (pin "5") (pinfunction "5_5") (pintype "passive"))
      (node (ref "J601") (pin "6") (pinfunction "6_6") (pintype "passive"))
      (node (ref "J701") (pin "2") (pinfunction "2_2") (pintype "passive"))
      (node (ref "J801") (pin "P$2") (pinfunction "P$2_P$2") (pintype "bidirectional"))
      (node (ref "J901") (pin "12") (pinfunction "S_12") (pintype "passive"))
      (node (ref "J901") (pin "15") (pinfunction "S_15") (pintype "passive"))
      (node (ref "J901") (pin "18") (pinfunction "S_18") (pintype "passive"))
      (node (ref "J901") (pin "21") (pinfunction "S_21") (pintype "passive"))
      (node (ref "J901") (pin "24") (pinfunction "S_24") (pintype "passive"))
      (node (ref "J901") (pin "27") (pinfunction "S_27") (pintype "passive"))
      (node (ref "J901") (pin "3") (pinfunction "S_3") (pintype "passive"))
      (node (ref "J901") (pin "30") (pinfunction "S_30") (pintype "passive"))
      (node (ref "J901") (pin "33") (pinfunction "S_33") (pintype "passive"))
      (node (ref "J901") (pin "36") (pinfunction "S_36") (pintype "passive"))
      (node (ref "J901") (pin "39") (pinfunction "S_39") (pintype "passive"))
      (node (ref "J901") (pin "42") (pinfunction "S_42") (pintype "passive"))
      (node (ref "J901") (pin "45") (pinfunction "S_45") (pintype "passive"))
      (node (ref "J901") (pin "48") (pinfunction "S_48") (pintype "passive"))
      (node (ref "J901") (pin "6") (pinfunction "S_6") (pintype "passive"))
      (node (ref "J901") (pin "9") (pinfunction "S_9") (pintype "passive"))
      (node (ref "JX301") (pin "3") (pinfunction "S_3") (pintype "passive"))
      (node (ref "JX301") (pin "5") (pinfunction "S_5") (pintype "passive"))
      (node (ref "JX301") (pin "9") (pinfunction "S_9") (pintype "passive"))
      (node (ref "JX801") (pin "3") (pinfunction "GND_3") (pintype "bidirectional"))
      (node (ref "JX802") (pin "3") (pinfunction "S_3") (pintype "passive"))
      (node (ref "JX802") (pin "5") (pinfunction "S_5") (pintype "passive"))
      (node (ref "JX802") (pin "9") (pinfunction "S_9") (pintype "passive"))
      (node (ref "L1101") (pin "P$3") (pinfunction "P$3_P$3") (pintype "bidirectional"))
      (node (ref "L1101") (pin "P$4") (pinfunction "P$3_P$4") (pintype "bidirectional"))
      (node (ref "L1101") (pin "P$5") (pinfunction "P$3_P$5") (pintype "bidirectional"))
      (node (ref "L1102") (pin "P$3") (pinfunction "P$3_P$3") (pintype "bidirectional"))
      (node (ref "L1102") (pin "P$4") (pinfunction "P$3_P$4") (pintype "bidirectional"))
      (node (ref "L1102") (pin "P$5") (pinfunction "P$3_P$5") (pintype "bidirectional"))
      (node (ref "L201") (pin "P$3") (pinfunction "P$3_P$3") (pintype "bidirectional"))
      (node (ref "L201") (pin "P$4") (pinfunction "P$3_P$4") (pintype "bidirectional"))
      (node (ref "L201") (pin "P$5") (pinfunction "P$3_P$5") (pintype "bidirectional"))
      (node (ref "L202") (pin "P$3") (pinfunction "P$3_P$3") (pintype "bidirectional"))
      (node (ref "L202") (pin "P$4") (pinfunction "P$3_P$4") (pintype "bidirectional"))
      (node (ref "L202") (pin "P$5") (pinfunction "P$3_P$5") (pintype "bidirectional"))
      (node (ref "L203") (pin "P$3") (pinfunction "P$3_P$3") (pintype "bidirectional"))
      (node (ref "L203") (pin "P$4") (pinfunction "P$3_P$4") (pintype "bidirectional"))
      (node (ref "L203") (pin "P$5") (pinfunction "P$3_P$5") (pintype "bidirectional"))
      (node (ref "L401") (pin "P$3") (pinfunction "P$3_P$3") (pintype "bidirectional"))
      (node (ref "L401") (pin "P$4") (pinfunction "P$3_P$4") (pintype "bidirectional"))
      (node (ref "L401") (pin "P$5") (pinfunction "P$3_P$5") (pintype "bidirectional"))
      (node (ref "L402") (pin "P$3") (pinfunction "P$3_P$3") (pintype "bidirectional"))
      (node (ref "L402") (pin "P$4") (pinfunction "P$3_P$4") (pintype "bidirectional"))
      (node (ref "L402") (pin "P$5") (pinfunction "P$3_P$5") (pintype "bidirectional"))
      (node (ref "L403") (pin "P$3") (pinfunction "P$3_P$3") (pintype "bidirectional"))
      (node (ref "L403") (pin "P$4") (pinfunction "P$3_P$4") (pintype "bidirectional"))
      (node (ref "L403") (pin "P$5") (pinfunction "P$3_P$5") (pintype "bidirectional"))
      (node (ref "L404") (pin "P$3") (pinfunction "P$3_P$3") (pintype "bidirectional"))
      (node (ref "L404") (pin "P$4") (pinfunction "P$3_P$4") (pintype "bidirectional"))
      (node (ref "L404") (pin "P$5") (pinfunction "P$3_P$5") (pintype "bidirectional"))
      (node (ref "L603") (pin "P$3") (pinfunction "P$3_P$3") (pintype "bidirectional"))
      (node (ref "L603") (pin "P$4") (pinfunction "P$3_P$4") (pintype "bidirectional"))
      (node (ref "L603") (pin "P$5") (pinfunction "P$3_P$5") (pintype "bidirectional"))
      (node (ref "L901") (pin "P$3") (pinfunction "P$3_P$3") (pintype "bidirectional"))
      (node (ref "L901") (pin "P$4") (pinfunction "P$3_P$4") (pintype "bidirectional"))
      (node (ref "L901") (pin "P$5") (pinfunction "P$3_P$5") (pintype "bidirectional"))
      (node (ref "R1001") (pin "P$1") (pinfunction "1_P$1") (pintype "passive"))
      (node (ref "R1002") (pin "P$1") (pinfunction "1_P$1") (pintype "passive"))
      (node (ref "R102") (pin "P$2") (pinfunction "2_P$2") (pintype "passive"))
      (node (ref "R1103") (pin "P$2") (pinfunction "2_P$2") (pintype "passive"))
      (node (ref "R1104") (pin "P$2") (pinfunction "2_P$2") (pintype "passive"))
      (node (ref "R1107") (pin "P$2") (pinfunction "2_P$2") (pintype "passive"))
      (node (ref "R1111") (pin "P$2") (pinfunction "2_P$2") (pintype "passive"))
      (node (ref "R1114") (pin "P$2") (pinfunction "2_P$2") (pintype "passive"))
      (node (ref "R1115") (pin "P$1") (pinfunction "1_P$1") (pintype "passive"))
      (node (ref "R403") (pin "P$1") (pinfunction "1_P$1") (pintype "passive"))
      (node (ref "R610") (pin "P$2") (pinfunction "2_P$2") (pintype "passive"))
      (node (ref "R611") (pin "P$1") (pinfunction "1_P$1") (pintype "passive"))
      (node (ref "R615") (pin "P$2") (pinfunction "2_P$2") (pintype "passive"))
      (node (ref "R616") (pin "P$2") (pinfunction "2_P$2") (pintype "passive"))
      (node (ref "R617") (pin "P$2") (pinfunction "2_P$2") (pintype "passive"))
      (node (ref "R621") (pin "1") (pinfunction "1_1") (pintype "passive"))
      (node (ref "R702") (pin "P$2") (pinfunction "2_P$2") (pintype "passive"))
      (node (ref "R704") (pin "P$1") (pinfunction "1_P$1") (pintype "passive"))
      (node (ref "R706") (pin "P$2") (pinfunction "2_P$2") (pintype "passive"))
      (node (ref "R708") (pin "P$1") (pinfunction "1_P$1") (pintype "passive"))
      (node (ref "R711") (pin "P$1") (pinfunction "1_P$1") (pintype "passive"))
      (node (ref "R713") (pin "P$2") (pinfunction "2_P$2") (pintype "passive"))
      (node (ref "R801") (pin "P$2") (pinfunction "2_P$2") (pintype "passive"))
      (node (ref "R802") (pin "P$2") (pinfunction "2_P$2") (pintype "passive"))
      (node (ref "R919") (pin "P$1") (pinfunction "1_P$1") (pintype "passive"))
      (node (ref "S601") (pin "B3") (pinfunction "2_B3") (pintype "passive"))
      (node (ref "S801") (pin "B3") (pinfunction "2_B3") (pintype "passive"))
      (node (ref "U1001") (pin "2") (pinfunction "VSS_2") (pintype "bidirectional"))
      (node (ref "U1001") (pin "5") (pinfunction "~{CE}_5") (pintype "bidirectional"))
      (node (ref "U1001") (pin "6") (pinfunction "VBAT_6") (pintype "bidirectional"))
      (node (ref "U1001") (pin "GND") (pinfunction "VSS_GND") (pintype "bidirectional"))
      (node (ref "U1001") (pin "P$2") (pinfunction "VSS_P$2") (pintype "bidirectional"))
      (node (ref "U1001") (pin "P$3") (pinfunction "VSS_P$3") (pintype "bidirectional"))
      (node (ref "U1002") (pin "2") (pinfunction "GND_2") (pintype "bidirectional"))
      (node (ref "U1002") (pin "GND") (pinfunction "GND_GND") (pintype "bidirectional"))
      (node (ref "U101") (pin "10") (pinfunction "VSS_10") (pintype "power_in"))
      (node (ref "U101") (pin "20") (pinfunction "VSSA_20") (pintype "power_in"))
      (node (ref "U101") (pin "27") (pinfunction "VSS_27") (pintype "power_in"))
      (node (ref "U101") (pin "74") (pinfunction "VSS_74") (pintype "power_in"))
      (node (ref "U101") (pin "99") (pinfunction "VSS_99") (pintype "power_in"))
      (node (ref "U102") (pin "4") (pinfunction "VSS_4") (pintype "bidirectional"))
      (node (ref "U1101") (pin "P$10") (pinfunction "GND_P$10") (pintype "bidirectional"))
      (node (ref "U1101") (pin "P$25") (pinfunction "GND_P$25") (pintype "bidirectional"))
      (node (ref "U201") (pin "11") (pinfunction "GND_11") (pintype "power_in"))
      (node (ref "U202") (pin "11") (pinfunction "GND_11") (pintype "power_in"))
      (node (ref "U301") (pin "6") (pinfunction "GND_6") (pintype "power_in"))
      (node (ref "U302") (pin "2") (pinfunction "GND_2") (pintype "bidirectional"))
      (node (ref "U401") (pin "2") (pinfunction "GND_2") (pintype "power_in"))
      (node (ref "U401") (pin "5") (pinfunction "SHDN_5") (pintype "input"))
      (node (ref "U401") (pin "8") (pinfunction "RS_8") (pintype "input"))
      (node (ref "U501") (pin "10") (pinfunction "RES_P10_GND_10") (pintype "bidirectional"))
      (node (ref "U501") (pin "11") (pinfunction "RES_P11_GND_11") (pintype "bidirectional"))
      (node (ref "U501") (pin "12") (pinfunction "RES_P12_GND_12") (pintype "bidirectional"))
      (node (ref "U501") (pin "13") (pinfunction "GND_13") (pintype "bidirectional"))
      (node (ref "U501") (pin "8") (pinfunction "RES_P8_GND_8") (pintype "bidirectional"))
      (node (ref "U501") (pin "9") (pinfunction "RES_P9_GND_9") (pintype "bidirectional"))
      (node (ref "U502") (pin "10") (pinfunction "GND_10") (pintype "bidirectional"))
      (node (ref "U502") (pin "11") (pinfunction "GND_11") (pintype "bidirectional"))
      (node (ref "U502") (pin "12") (pinfunction "GND_12") (pintype "bidirectional"))
      (node (ref "U502") (pin "13") (pinfunction "GND_13") (pintype "bidirectional"))
      (node (ref "U502") (pin "9") (pinfunction "GND_9") (pintype "bidirectional"))
      (node (ref "U504") (pin "10") (pinfunction "RSRV_10") (pintype "bidirectional"))
      (node (ref "U504") (pin "12") (pinfunction "GND_12") (pintype "bidirectional"))
      (node (ref "U504") (pin "13") (pinfunction "GND_13") (pintype "bidirectional"))
      (node (ref "U504") (pin "16") (pinfunction "GND_16") (pintype "bidirectional"))
      (node (ref "U504") (pin "5") (pinfunction "GND_5") (pintype "bidirectional"))
      (node (ref "U505") (pin "1") (pinfunction "CLKIN_1") (pintype "bidirectional"))
      (node (ref "U505") (pin "18") (pinfunction "GND_18") (pintype "bidirectional"))
      (node (ref "U506") (pin "2") (pinfunction "PS_2") (pintype "bidirectional"))
      (node (ref "U506") (pin "3") (pinfunction "GND_3") (pintype "bidirectional"))
      (node (ref "U601") (pin "2") (pinfunction "VSS_2") (pintype "bidirectional"))
      (node (ref "U601") (pin "6") (pinfunction "VBAT_6") (pintype "bidirectional"))
      (node (ref "U601") (pin "GND") (pinfunction "VSS_GND") (pintype "bidirectional"))
      (node (ref "U601") (pin "P$2") (pinfunction "VSS_P$2") (pintype "bidirectional"))
      (node (ref "U601") (pin "P$3") (pinfunction "VSS_P$3") (pintype "bidirectional"))
      (node (ref "U602") (pin "2") (pinfunction "VSS_2") (pintype "bidirectional"))
      (node (ref "U602") (pin "6") (pinfunction "VBAT_6") (pintype "bidirectional"))
      (node (ref "U602") (pin "GND") (pinfunction "VSS_GND") (pintype "bidirectional"))
      (node (ref "U602") (pin "P$2") (pinfunction "VSS_P$2") (pintype "bidirectional"))
      (node (ref "U602") (pin "P$3") (pinfunction "VSS_P$3") (pintype "bidirectional"))
      (node (ref "U603") (pin "2") (pinfunction "GND_2") (pintype "bidirectional"))
      (node (ref "U603") (pin "GND") (pinfunction "GND_GND") (pintype "bidirectional"))
      (node (ref "U701") (pin "5") (pinfunction "GND_5") (pintype "power_in"))
      (node (ref "U702") (pin "4") (pinfunction "GND_4") (pintype "power_in"))
      (node (ref "U801") (pin "23") (pinfunction "VSS_1_23") (pintype "power_in"))
      (node (ref "U801") (pin "35") (pinfunction "VSS_2_35") (pintype "power_in"))
      (node (ref "U801") (pin "47") (pinfunction "VSS_3_47") (pintype "power_in"))
      (node (ref "U801") (pin "8") (pinfunction "VSSA_8") (pintype "power_in"))
      (node (ref "U901") (pin "11") (pinfunction "GND_11") (pintype "power_in"))
      (node (ref "U902") (pin "11") (pinfunction "GND_11") (pintype "power_in"))
      (node (ref "U903") (pin "1") (pinfunction "~{1OE}_1") (pintype "input"))
      (node (ref "U903") (pin "4") (pinfunction "GND_4") (pintype "power_in"))
      (node (ref "X101") (pin "2") (pinfunction "NC_2_2") (pintype "power_in"))
      (node (ref "X101") (pin "4") (pinfunction "NC_4_4") (pintype "power_in"))
      (node (ref "X503") (pin "2") (pinfunction "S_2") (pintype "passive"))
      (node (ref "X801") (pin "2") (pinfunction "NC_2_2") (pintype "power_in"))
      (node (ref "X801") (pin "4") (pinfunction "NC_4_4") (pintype "power_in"))
    )
    (net (code "47") (name "GPIO_EXT_1") (class "Default")
      (node (ref "J403") (pin "6") (pinfunction "6_6") (pintype "passive"))
      (node (ref "U101") (pin "8") (pinfunction "PC14_8") (pintype "bidirectional"))
    )
    (net (code "48") (name "GYRO_DRDY") (class "Default")
      (node (ref "U101") (pin "35") (pinfunction "PB0_35") (pintype "bidirectional"))
      (node (ref "U501") (pin "6") (pinfunction "DRDY/INT2_6") (pintype "output"))
      (node (ref "U502") (pin "6") (pinfunction "DRDY/INT2_6") (pintype "bidirectional"))
      (node (ref "X503") (pin "5") (pinfunction "S_5") (pintype "passive"))
    )
    (net (code "49") (name "IO-BOOT0") (class "Default")
      (node (ref "IO-BOOT1101") (pin "P$1") (pinfunction "P$1_P$1") (pintype "passive"))
      (node (ref "R801") (pin "P$1") (pinfunction "1_P$1") (pintype "passive"))
      (node (ref "U801") (pin "44") (pinfunction "BOOT0_44") (pintype "input"))
    )
    (net (code "50") (name "IO-CH1") (class "Default")
      (node (ref "U801") (pin "10") (pinfunction "PA0_10") (pintype "bidirectional"))
      (node (ref "U902") (pin "9") (pinfunction "A8_9") (pintype "bidirectional"))
    )
    (net (code "51") (name "IO-CH2") (class "Default")
      (node (ref "U801") (pin "11") (pinfunction "PA1_11") (pintype "bidirectional"))
      (node (ref "U902") (pin "8") (pinfunction "A7_8") (pintype "bidirectional"))
    )
    (net (code "52") (name "IO-CH3") (class "Default")
      (node (ref "U801") (pin "45") (pinfunction "PB8_45") (pintype "bidirectional"))
      (node (ref "U902") (pin "7") (pinfunction "A6_7") (pintype "bidirectional"))
    )
    (net (code "53") (name "IO-CH4") (class "Default")
      (node (ref "U801") (pin "46") (pinfunction "PB9_46") (pintype "bidirectional"))
      (node (ref "U902") (pin "6") (pinfunction "A5_6") (pintype "bidirectional"))
    )
    (net (code "54") (name "IO-CH5") (class "Default")
      (node (ref "U801") (pin "16") (pinfunction "PA6_16") (pintype "bidirectional"))
      (node (ref "U902") (pin "5") (pinfunction "A4_5") (pintype "bidirectional"))
    )
    (net (code "55") (name "IO-CH6") (class "Default")
      (node (ref "U801") (pin "17") (pinfunction "PA7_17") (pintype "bidirectional"))
      (node (ref "U902") (pin "4") (pinfunction "A3_4") (pintype "bidirectional"))
    )
    (net (code "56") (name "IO-CH7") (class "Default")
      (node (ref "U801") (pin "18") (pinfunction "PB0_18") (pintype "bidirectional"))
      (node (ref "U902") (pin "3") (pinfunction "A2_3") (pintype "bidirectional"))
    )
    (net (code "57") (name "IO-CH8") (class "Default")
      (node (ref "U801") (pin "19") (pinfunction "PB1_19") (pintype "bidirectional"))
      (node (ref "U902") (pin "1") (pinfunction "A1_1") (pintype "bidirectional"))
    )
    (net (code "58") (name "IO-SWCLK") (class "Default")
      (node (ref "JX802") (pin "4") (pinfunction "S_4") (pintype "passive"))
      (node (ref "U801") (pin "37") (pinfunction "PA14_37") (pintype "bidirectional"))
    )
    (net (code "59") (name "IO-SWDIO") (class "Default")
      (node (ref "JX802") (pin "2") (pinfunction "S_2") (pintype "passive"))
      (node (ref "U801") (pin "34") (pinfunction "PA13_34") (pintype "bidirectional"))
    )
    (net (code "60") (name "IO-SWO") (class "Default")
      (node (ref "JX802") (pin "6") (pinfunction "S_6") (pintype "passive"))
      (node (ref "U801") (pin "39") (pinfunction "PB3_39") (pintype "bidirectional"))
    )
    (net (code "61") (name "IO-USART1_RX") (class "Default")
      (node (ref "J801") (pin "P$3") (pinfunction "P$3_P$3") (pintype "bidirectional"))
      (node (ref "JX801") (pin "2") (pinfunction "+5V_2") (pintype "bidirectional"))
      (node (ref "U801") (pin "31") (pinfunction "PA10_31") (pintype "bidirectional"))
    )
    (net (code "62") (name "IO-USART1_TX") (class "Default")
      (node (ref "JX801") (pin "1") (pinfunction "PPM_1") (pintype "bidirectional"))
      (node (ref "R101") (pin "P$2") (pinfunction "2_P$2") (pintype "passive"))
      (node (ref "U801") (pin "30") (pinfunction "PA9_30") (pintype "bidirectional"))
    )
    (net (code "63") (name "IO-VDD_3V3") (class "Default")
      (node (ref "C1003") (pin "P$1") (pinfunction "1_P$1") (pintype "passive"))
      (node (ref "C1004") (pin "P$1") (pinfunction "1_P$1") (pintype "passive"))
      (node (ref "C802") (pin "P$1") (pinfunction "1_P$1") (pintype "passive"))
      (node (ref "C803") (pin "P$1") (pinfunction "1_P$1") (pintype "passive"))
      (node (ref "C804") (pin "P$1") (pinfunction "1_P$1") (pintype "passive"))
      (node (ref "C901") (pin "P$1") (pinfunction "1_P$1") (pintype "passive"))
      (node (ref "C903") (pin "P$1") (pinfunction "1_P$1") (pintype "passive"))
      (node (ref "D701") (pin "C") (pinfunction "C_C") (pintype "passive"))
      (node (ref "J702") (pin "1") (pinfunction "1_1") (pintype "passive"))
      (node (ref "JX802") (pin "1") (pinfunction "S_1") (pintype "passive"))
      (node (ref "U1002") (pin "7") (pinfunction "VOUT2_7") (pintype "bidirectional"))
      (node (ref "U801") (pin "24") (pinfunction "VDD_1_24") (pintype "power_in"))
      (node (ref "U801") (pin "36") (pinfunction "VDD_2_36") (pintype "power_in"))
      (node (ref "U801") (pin "48") (pinfunction "VDD_3_48") (pintype "power_in"))
      (node (ref "U801") (pin "9") (pinfunction "VDDA_9") (pintype "power_in"))
      (node (ref "U902") (pin "10") (pinfunction "OE_10") (pintype "input"))
      (node (ref "U902") (pin "19") (pinfunction "VCCB_19") (pintype "input"))
      (node (ref "U902") (pin "2") (pinfunction "VCCA_2") (pintype "input"))
      (node (ref "U903") (pin "8") (pinfunction "VCC_8") (pintype "power_in"))
    )
    (net (code "64") (name "IO-VDD_5V5") (class "Default")
      (node (ref "C1001") (pin "P$1") (pinfunction "1_P$1") (pintype "passive"))
      (node (ref "C1005") (pin "P$1") (pinfunction "1_P$1") (pintype "passive"))
      (node (ref "D1001") (pin "3") (pinfunction "CC_3") (pintype "passive"))
      (node (ref "J901") (pin "2") (pinfunction "S_2") (pintype "passive"))
      (node (ref "LED702") (pin "A") (pinfunction "A_A") (pintype "passive"))
      (node (ref "LED703") (pin "A") (pinfunction "A_A") (pintype "passive"))
      (node (ref "LED705") (pin "A") (pinfunction "A_A") (pintype "passive"))
      (node (ref "U1002") (pin "1") (pinfunction "VIN_1") (pintype "bidirectional"))
      (node (ref "U1002") (pin "4") (pinfunction "EN2_4") (pintype "bidirectional"))
    )
    (net (code "65") (name "IO-~{RESET}") (class "Default")
      (node (ref "C801") (pin "P$2") (pinfunction "2_P$2") (pintype "passive"))
      (node (ref "S801") (pin "A1") (pinfunction "1_A1") (pintype "passive"))
      (node (ref "U1002") (pin "3") (pinfunction "POR2_3") (pintype "bidirectional"))
      (node (ref "U801") (pin "7") (pinfunction "NRST_7") (pintype "input"))
    )
    (net (code "66") (name "IO-~{VDD_SERVO_IN_FAULT}") (class "Default")
      (node (ref "U1001") (pin "4") (pinfunction "~{FAULT}_4") (pintype "bidirectional"))
      (node (ref "U801") (pin "38") (pinfunction "PA15_38") (pintype "bidirectional"))
    )
    (net (code "67") (name "MAG_DRDY") (class "Default")
      (node (ref "U101") (pin "36") (pinfunction "PB1_36") (pintype "bidirectional"))
      (node (ref "U504") (pin "9") (pinfunction "INT2_9") (pintype "bidirectional"))
      (node (ref "X503") (pin "4") (pinfunction "S_4") (pintype "passive"))
    )
    (net (code "68") (name "MPU_DRDY") (class "Default")
      (node (ref "U101") (pin "62") (pinfunction "PD15_62") (pintype "bidirectional"))
      (node (ref "U505") (pin "12") (pinfunction "INT_12") (pintype "bidirectional"))
    )
    (net (code "69") (name "Net-(C102-1)") (class "Default")
      (node (ref "C102") (pin "P$1") (pinfunction "1_P$1") (pintype "passive"))
      (node (ref "U101") (pin "12") (pinfunction "OSC_IN_12") (pintype "input"))
      (node (ref "X101") (pin "3") (pinfunction "3_3") (pintype "bidirectional"))
    )
    (net (code "70") (name "Net-(C103-2)") (class "Default")
      (node (ref "C103") (pin "P$2") (pinfunction "2_P$2") (pintype "passive"))
      (node (ref "U101") (pin "13") (pinfunction "OSC_OUT_13") (pintype "output"))
      (node (ref "X101") (pin "1") (pinfunction "1_1") (pintype "bidirectional"))
    )
    (net (code "71") (name "Net-(C504-1)") (class "Default")
      (node (ref "C504") (pin "P$1") (pinfunction "1_P$1") (pintype "passive"))
      (node (ref "U501") (pin "14") (pinfunction "PLLFILT_14") (pintype "bidirectional"))
    )
    (net (code "72") (name "Net-(C505-1)") (class "Default")
      (node (ref "C505") (pin "P$1") (pinfunction "1_P$1") (pintype "passive"))
      (node (ref "U502") (pin "14") (pinfunction "CAP_14") (pintype "bidirectional"))
    )
    (net (code "73") (name "Net-(C509-1)") (class "Default")
      (node (ref "C509") (pin "P$1") (pinfunction "1_P$1") (pintype "passive"))
      (node (ref "U504") (pin "15") (pinfunction "C1_15") (pintype "bidirectional"))
    )
    (net (code "74") (name "Net-(C510-1)") (class "Default")
      (node (ref "C510") (pin "P$1") (pinfunction "1_P$1") (pintype "passive"))
      (node (ref "U504") (pin "2") (pinfunction "SETC_2") (pintype "bidirectional"))
    )
    (net (code "75") (name "Net-(C510-2)") (class "Default")
      (node (ref "C510") (pin "P$2") (pinfunction "2_P$2") (pintype "passive"))
      (node (ref "U504") (pin "3") (pinfunction "SETP_3") (pintype "bidirectional"))
    )
    (net (code "76") (name "Net-(C512-1)") (class "Default")
      (node (ref "C512") (pin "P$1") (pinfunction "1_P$1") (pintype "passive"))
      (node (ref "U505") (pin "10") (pinfunction "REGOUT_10") (pintype "bidirectional"))
    )
    (net (code "77") (name "Net-(C515-1)") (class "Default")
      (node (ref "C515") (pin "P$1") (pinfunction "1_P$1") (pintype "passive"))
      (node (ref "U505") (pin "20") (pinfunction "CPOUT_20") (pintype "bidirectional"))
    )
    (net (code "78") (name "Net-(C601-1)") (class "Default")
      (node (ref "C601") (pin "P$1") (pinfunction "1_P$1") (pintype "passive"))
      (node (ref "C615") (pin "P$1") (pinfunction "1_P$1") (pintype "passive"))
      (node (ref "L603") (pin "P$2") (pinfunction "P$2_P$2") (pintype "bidirectional"))
      (node (ref "R603") (pin "P$1") (pinfunction "1_P$1") (pintype "passive"))
      (node (ref "U603") (pin "1") (pinfunction "VIN_1") (pintype "bidirectional"))
      (node (ref "U603") (pin "4") (pinfunction "EN2_4") (pintype "bidirectional"))
    )
    (net (code "79") (name "Net-(C602-2)") (class "Default")
      (node (ref "C602") (pin "P$2") (pinfunction "2_P$2") (pintype "passive"))
      (node (ref "U603") (pin "6") (pinfunction "CSET_6") (pintype "bidirectional"))
    )
    (net (code "80") (name "Net-(C611-1)") (class "Default")
      (node (ref "C611") (pin "P$1") (pinfunction "1_P$1") (pintype "passive"))
      (node (ref "U101") (pin "49") (pinfunction "VCAP_1_49") (pintype "power_in"))
    )
    (net (code "81") (name "Net-(C613-1)") (class "Default")
      (node (ref "C613") (pin "P$1") (pinfunction "1_P$1") (pintype "passive"))
      (node (ref "U101") (pin "73") (pinfunction "VCAP_2_73") (pintype "power_in"))
    )
    (net (code "82") (name "Net-(C703-1)") (class "Default")
      (node (ref "C703") (pin "P$1") (pinfunction "1_P$1") (pintype "passive"))
      (node (ref "J701") (pin "1") (pinfunction "1_1") (pintype "passive"))
      (node (ref "R703") (pin "P$1") (pinfunction "1_P$1") (pintype "passive"))
      (node (ref "U702") (pin "1") (pinfunction "OUT_1") (pintype "output"))
    )
    (net (code "83") (name "Net-(C704-1)") (class "Default")
      (node (ref "C704") (pin "P$1") (pinfunction "1_P$1") (pintype "passive"))
      (node (ref "R705") (pin "P$1") (pinfunction "1_P$1") (pintype "passive"))
      (node (ref "U702") (pin "6") (pinfunction "VCC_6") (pintype "bidirectional"))
    )
    (net (code "84") (name "Net-(C805-1)") (class "Default")
      (node (ref "C805") (pin "P$1") (pinfunction "1_P$1") (pintype "passive"))
      (node (ref "U801") (pin "5") (pinfunction "PD0/OSC<=_5") (pintype "bidirectional"))
      (node (ref "X801") (pin "3") (pinfunction "3_3") (pintype "bidirectional"))
    )
    (net (code "85") (name "Net-(C806-2)") (class "Default")
      (node (ref "C806") (pin "P$2") (pinfunction "2_P$2") (pintype "passive"))
      (node (ref "U801") (pin "6") (pinfunction "PD1/OSC=>_6") (pintype "bidirectional"))
      (node (ref "X801") (pin "1") (pinfunction "1_1") (pintype "bidirectional"))
    )
    (net (code "86") (name "Net-(C1002-1)") (class "Default")
      (node (ref "C1002") (pin "P$1") (pinfunction "1_P$1") (pintype "passive"))
      (node (ref "U1002") (pin "6") (pinfunction "CSET_6") (pintype "bidirectional"))
    )
    (net (code "87") (name "Net-(C1105-1)") (class "Default")
      (node (ref "C1105") (pin "P$1") (pinfunction "1_P$1") (pintype "passive"))
      (node (ref "U1101") (pin "P$18") (pinfunction "VS1_P$18") (pintype "bidirectional"))
      (node (ref "U1102") (pin "P$1") (pinfunction "S_P$1") (pintype "passive"))
      (node (ref "U1102") (pin "P$3") (pinfunction "S_P$3") (pintype "passive"))
    )
    (net (code "88") (name "Net-(C1106-1)") (class "Default")
      (node (ref "C1106") (pin "P$1") (pinfunction "1_P$1") (pintype "passive"))
      (node (ref "U1101") (pin "P$16") (pinfunction "VS2_P$16") (pintype "bidirectional"))
      (node (ref "U1103") (pin "P$1") (pinfunction "S_P$1") (pintype "passive"))
      (node (ref "U1103") (pin "P$3") (pinfunction "S_P$3") (pintype "passive"))
    )
    (net (code "89") (name "Net-(C1107-1)") (class "Default")
      (node (ref "C1107") (pin "P$1") (pinfunction "1_P$1") (pintype "passive"))
      (node (ref "U1101") (pin "P$14") (pinfunction "VS3_P$14") (pintype "bidirectional"))
      (node (ref "U1104") (pin "P$1") (pinfunction "S_P$1") (pintype "passive"))
      (node (ref "U1104") (pin "P$3") (pinfunction "S_P$3") (pintype "passive"))
    )
    (net (code "90") (name "Net-(C1108-1)") (class "Default")
      (node (ref "C1108") (pin "P$1") (pinfunction "1_P$1") (pintype "passive"))
      (node (ref "R1105") (pin "P$2") (pinfunction "2_P$2") (pintype "passive"))
      (node (ref "R1106") (pin "P$1") (pinfunction "1_P$1") (pintype "passive"))
      (node (ref "U1101") (pin "P$1") (pinfunction "UV1_P$1") (pintype "bidirectional"))
    )
    (net (code "91") (name "Net-(C1109-1)") (class "Default")
      (node (ref "C1109") (pin "P$1") (pinfunction "1_P$1") (pintype "passive"))
      (node (ref "R1109") (pin "P$2") (pinfunction "2_P$2") (pintype "passive"))
      (node (ref "R1110") (pin "P$1") (pinfunction "1_P$1") (pintype "passive"))
      (node (ref "U1101") (pin "P$3") (pinfunction "UV2_P$3") (pintype "bidirectional"))
    )
    (net (code "92") (name "Net-(C1110-1)") (class "Default")
      (node (ref "C1110") (pin "P$1") (pinfunction "1_P$1") (pintype "passive"))
      (node (ref "R1112") (pin "P$2") (pinfunction "2_P$2") (pintype "passive"))
      (node (ref "R1113") (pin "P$1") (pinfunction "1_P$1") (pintype "passive"))
      (node (ref "U1101") (pin "P$5") (pinfunction "UV3_P$5") (pintype "bidirectional"))
    )
    (net (code "93") (name "Net-(D1-C)") (class "Default")
      (node (ref "D1") (pin "CATHODE") (pinfunction "C_CATHODE") (pintype "passive"))
      (node (ref "D903") (pin "C") (pinfunction "C_C") (pintype "passive"))
      (node (ref "L901") (pin "P$1") (pinfunction "P$1_P$1") (pintype "bidirectional"))
    )
    (net (code "94") (name "Net-(D201-PadC)") (class "Default")
      (node (ref "D201") (pin "C") (pinfunction "C_C") (pintype "passive"))
      (node (ref "J201") (pin "1") (pinfunction "1_1") (pintype "passive"))
      (node (ref "L201") (pin "P$2") (pinfunction "P$2_P$2") (pintype "bidirectional"))
    )
    (net (code "95") (name "Net-(D202-PadC)") (class "Default")
      (node (ref "D202") (pin "C") (pinfunction "C_C") (pintype "passive"))
      (node (ref "J202") (pin "1") (pinfunction "1_1") (pintype "passive"))
      (node (ref "L202") (pin "P$2") (pinfunction "P$2_P$2") (pintype "bidirectional"))
    )
    (net (code "96") (name "Net-(D203-PadC)") (class "Default")
      (node (ref "D203") (pin "C") (pinfunction "C_C") (pintype "passive"))
      (node (ref "J203") (pin "1") (pinfunction "1_1") (pintype "passive"))
      (node (ref "J204") (pin "1") (pinfunction "1_1") (pintype "passive"))
      (node (ref "L203") (pin "P$2") (pinfunction "P$2_P$2") (pintype "bidirectional"))
    )
    (net (code "97") (name "Net-(D401-PadC)") (class "Default")
      (node (ref "D401") (pin "C") (pinfunction "C_C") (pintype "passive"))
      (node (ref "J401") (pin "1") (pinfunction "1_1") (pintype "passive"))
      (node (ref "J402") (pin "1") (pinfunction "1_1") (pintype "passive"))
      (node (ref "L401") (pin "P$2") (pinfunction "P$2_P$2") (pintype "bidirectional"))
    )
    (net (code "98") (name "Net-(D402-PadC)") (class "Default")
      (node (ref "D402") (pin "C") (pinfunction "C_C") (pintype "passive"))
      (node (ref "J403") (pin "1") (pinfunction "1_1") (pintype "passive"))
      (node (ref "L402") (pin "P$2") (pinfunction "P$2_P$2") (pintype "bidirectional"))
    )
    (net (code "99") (name "Net-(D403-PadC)") (class "Default")
      (node (ref "D403") (pin "C") (pinfunction "C_C") (pintype "passive"))
      (node (ref "J404") (pin "1") (pinfunction "1_1") (pintype "passive"))
      (node (ref "L404") (pin "P$2") (pinfunction "P$2_P$2") (pintype "bidirectional"))
    )
    (net (code "100") (name "Net-(D404-PadC)") (class "Default")
      (node (ref "D404") (pin "C") (pinfunction "C_C") (pintype "passive"))
      (node (ref "J405") (pin "1") (pinfunction "1_1") (pintype "passive"))
      (node (ref "L403") (pin "P$2") (pinfunction "P$2_P$2") (pintype "bidirectional"))
    )
    (net (code "101") (name "Net-(D1001-A1)") (class "Default")
      (node (ref "D1001") (pin "1") (pinfunction "A1_1") (pintype "passive"))
      (node (ref "F1001") (pin "2") (pinfunction "2_2") (pintype "bidirectional"))
    )
    (net (code "102") (name "Net-(D1001-A2)") (class "Default")
      (node (ref "D1001") (pin "2") (pinfunction "A2_2") (pintype "passive"))
      (node (ref "U1001") (pin "8") (pinfunction "OUT_8") (pintype "bidirectional"))
    )
    (net (code "103") (name "Net-(J301-2)") (class "Default")
      (node (ref "J301") (pin "D-") (pinfunction "2_D-") (pintype "bidirectional"))
      (node (ref "J302") (pin "3") (pinfunction "3_3") (pintype "passive"))
      (node (ref "U302") (pin "1") (pinfunction "D1I_1") (pintype "bidirectional"))
    )
    (net (code "104") (name "Net-(J301-3)") (class "Default")
      (node (ref "J301") (pin "D+") (pinfunction "3_D+") (pintype "bidirectional"))
      (node (ref "J302") (pin "2") (pinfunction "2_2") (pintype "passive"))
      (node (ref "U302") (pin "3") (pinfunction "D2I_3") (pintype "bidirectional"))
    )
    (net (code "105") (name "Net-(J901A-S)") (class "Default")
      (node (ref "J901") (pin "1") (pinfunction "S_1") (pintype "passive"))
      (node (ref "R909") (pin "P$2") (pinfunction "2_P$2") (pintype "passive"))
    )
    (net (code "106") (name "Net-(J901B-S)") (class "Default")
      (node (ref "J901") (pin "10") (pinfunction "S_10") (pintype "passive"))
      (node (ref "R914") (pin "P$2") (pinfunction "2_P$2") (pintype "passive"))
    )
    (net (code "107") (name "Net-(J901C-S)") (class "Default")
      (node (ref "J901") (pin "13") (pinfunction "S_13") (pintype "passive"))
      (node (ref "R906") (pin "P$2") (pinfunction "2_P$2") (pintype "passive"))
    )
    (net (code "108") (name "Net-(J901D-S)") (class "Default")
      (node (ref "J901") (pin "16") (pinfunction "S_16") (pintype "passive"))
      (node (ref "R915") (pin "P$2") (pinfunction "2_P$2") (pintype "passive"))
    )
    (net (code "109") (name "Net-(J901E-S)") (class "Default")
      (node (ref "J901") (pin "19") (pinfunction "S_19") (pintype "passive"))
      (node (ref "R907") (pin "P$2") (pinfunction "2_P$2") (pintype "passive"))
    )
    (net (code "110") (name "Net-(J901G-S)") (class "Default")
      (node (ref "J901") (pin "22") (pinfunction "S_22") (pintype "passive"))
      (node (ref "R916") (pin "P$2") (pinfunction "2_P$2") (pintype "passive"))
    )
    (net (code "111") (name "Net-(J901H-S)") (class "Default")
      (node (ref "J901") (pin "25") (pinfunction "S_25") (pintype "passive"))
      (node (ref "R908") (pin "P$2") (pinfunction "2_P$2") (pintype "passive"))
    )
    (net (code "112") (name "Net-(J901I-S)") (class "Default")
      (node (ref "J901") (pin "28") (pinfunction "S_28") (pintype "passive"))
      (node (ref "R917") (pin "P$2") (pinfunction "2_P$2") (pintype "passive"))
    )
    (net (code "113") (name "Net-(J901J-S)") (class "Default")
      (node (ref "J901") (pin "31") (pinfunction "S_31") (pintype "passive"))
      (node (ref "R902") (pin "P$2") (pinfunction "2_P$2") (pintype "passive"))
    )
    (net (code "114") (name "Net-(J901K-S)") (class "Default")
      (node (ref "J901") (pin "34") (pinfunction "S_34") (pintype "passive"))
      (node (ref "R911") (pin "P$2") (pinfunction "2_P$2") (pintype "passive"))
    )
    (net (code "115") (name "Net-(J901L-S)") (class "Default")
      (node (ref "J901") (pin "37") (pinfunction "S_37") (pintype "passive"))
      (node (ref "R903") (pin "P$2") (pinfunction "2_P$2") (pintype "passive"))
    )
    (net (code "116") (name "Net-(J901M-S)") (class "Default")
      (node (ref "J901") (pin "4") (pinfunction "S_4") (pintype "passive"))
      (node (ref "R910") (pin "P$2") (pinfunction "2_P$2") (pintype "passive"))
    )
    (net (code "117") (name "Net-(J901N-S)") (class "Default")
      (node (ref "J901") (pin "40") (pinfunction "S_40") (pintype "passive"))
      (node (ref "R912") (pin "P$2") (pinfunction "2_P$2") (pintype "passive"))
    )
    (net (code "118") (name "Net-(J901O-S)") (class "Default")
      (node (ref "J901") (pin "43") (pinfunction "S_43") (pintype "passive"))
      (node (ref "R904") (pin "P$2") (pinfunction "2_P$2") (pintype "passive"))
    )
    (net (code "119") (name "Net-(J901P-S)") (class "Default")
      (node (ref "J901") (pin "46") (pinfunction "S_46") (pintype "passive"))
      (node (ref "R913") (pin "P$2") (pinfunction "2_P$2") (pintype "passive"))
    )
    (net (code "120") (name "Net-(J901Q-S)") (class "Default")
      (node (ref "J901") (pin "7") (pinfunction "S_7") (pintype "passive"))
      (node (ref "R905") (pin "P$2") (pinfunction "2_P$2") (pintype "passive"))
    )
    (net (code "121") (name "Net-(L701-2)") (class "Default")
      (node (ref "L701") (pin "P$2") (pinfunction "2_P$2") (pintype "passive"))
      (node (ref "U702") (pin "5") (pinfunction "SW_5") (pintype "passive"))
    )
    (net (code "122") (name "Net-(Q601-PadC)") (class "Default")
      (node (ref "Q601") (pin "C") (pinfunction "C_C") (pintype "passive"))
      (node (ref "R621") (pin "2") (pinfunction "2_2") (pintype "passive"))
    )
    (net (code "123") (name "Net-(R3-1)") (class "Default")
      (node (ref "R3") (pin "P$1") (pinfunction "1_P$1") (pintype "passive"))
      (node (ref "R707") (pin "P$2") (pinfunction "2_P$2") (pintype "passive"))
    )
    (net (code "124") (name "Net-(R3-2)") (class "Default")
      (node (ref "LED701") (pin "C") (pinfunction "C_C") (pintype "passive"))
      (node (ref "R3") (pin "P$2") (pinfunction "2_P$2") (pintype "passive"))
    )
    (net (code "125") (name "Net-(R4-1)") (class "Default")
      (node (ref "R4") (pin "P$1") (pinfunction "1_P$1") (pintype "passive"))
      (node (ref "R709") (pin "P$2") (pinfunction "2_P$2") (pintype "passive"))
    )
    (net (code "126") (name "Net-(R4-2)") (class "Default")
      (node (ref "LED703") (pin "C") (pinfunction "C_C") (pintype "passive"))
      (node (ref "R4") (pin "P$2") (pinfunction "2_P$2") (pintype "passive"))
    )
    (net (code "127") (name "Net-(R101-1)") (class "Default")
      (node (ref "R101") (pin "P$1") (pinfunction "1_P$1") (pintype "passive"))
      (node (ref "U101") (pin "69") (pinfunction "PA10_69") (pintype "bidirectional"))
    )
    (net (code "128") (name "Net-(R102-1)") (class "Default")
      (node (ref "R102") (pin "P$1") (pinfunction "1_P$1") (pintype "passive"))
      (node (ref "U101") (pin "37") (pinfunction "PB2_37") (pintype "bidirectional"))
    )
    (net (code "129") (name "Net-(R201-1)") (class "Default")
      (node (ref "R201") (pin "P$1") (pinfunction "1_P$1") (pintype "passive"))
      (node (ref "U201") (pin "20") (pinfunction "B1_20") (pintype "bidirectional"))
    )
    (net (code "130") (name "Net-(R202-1)") (class "Default")
      (node (ref "R202") (pin "P$1") (pinfunction "1_P$1") (pintype "passive"))
      (node (ref "U201") (pin "17") (pinfunction "B3_17") (pintype "bidirectional"))
    )
    (net (code "131") (name "Net-(R203-1)") (class "Default")
      (node (ref "R203") (pin "P$1") (pinfunction "1_P$1") (pintype "passive"))
      (node (ref "U201") (pin "15") (pinfunction "B5_15") (pintype "bidirectional"))
    )
    (net (code "132") (name "Net-(R204-1)") (class "Default")
      (node (ref "R204") (pin "P$1") (pinfunction "1_P$1") (pintype "passive"))
      (node (ref "U201") (pin "13") (pinfunction "B7_13") (pintype "bidirectional"))
    )
    (net (code "133") (name "Net-(R205-1)") (class "Default")
      (node (ref "R205") (pin "P$1") (pinfunction "1_P$1") (pintype "passive"))
      (node (ref "U202") (pin "17") (pinfunction "B3_17") (pintype "bidirectional"))
    )
    (net (code "134") (name "Net-(R206-1)") (class "Default")
      (node (ref "R206") (pin "P$1") (pinfunction "1_P$1") (pintype "passive"))
      (node (ref "U202") (pin "15") (pinfunction "B5_15") (pintype "bidirectional"))
    )
    (net (code "135") (name "Net-(R207-1)") (class "Default")
      (node (ref "R207") (pin "P$1") (pinfunction "1_P$1") (pintype "passive"))
      (node (ref "U202") (pin "13") (pinfunction "B7_13") (pintype "bidirectional"))
    )
    (net (code "136") (name "Net-(R208-1)") (class "Default")
      (node (ref "R208") (pin "P$1") (pinfunction "1_P$1") (pintype "passive"))
      (node (ref "U201") (pin "18") (pinfunction "B2_18") (pintype "bidirectional"))
    )
    (net (code "137") (name "Net-(R209-1)") (class "Default")
      (node (ref "R209") (pin "P$1") (pinfunction "1_P$1") (pintype "passive"))
      (node (ref "U201") (pin "16") (pinfunction "B4_16") (pintype "bidirectional"))
    )
    (net (code "138") (name "Net-(R210-1)") (class "Default")
      (node (ref "R210") (pin "P$1") (pinfunction "1_P$1") (pintype "passive"))
      (node (ref "U201") (pin "14") (pinfunction "B6_14") (pintype "bidirectional"))
    )
    (net (code "139") (name "Net-(R211-1)") (class "Default")
      (node (ref "R211") (pin "P$1") (pinfunction "1_P$1") (pintype "passive"))
      (node (ref "U201") (pin "12") (pinfunction "B8_12") (pintype "bidirectional"))
    )
    (net (code "140") (name "Net-(R212-1)") (class "Default")
      (node (ref "R212") (pin "P$1") (pinfunction "1_P$1") (pintype "passive"))
      (node (ref "U202") (pin "16") (pinfunction "B4_16") (pintype "bidirectional"))
    )
    (net (code "141") (name "Net-(R213-1)") (class "Default")
      (node (ref "R213") (pin "P$1") (pinfunction "1_P$1") (pintype "passive"))
      (node (ref "U202") (pin "14") (pinfunction "B6_14") (pintype "bidirectional"))
    )
    (net (code "142") (name "Net-(R214-1)") (class "Default")
      (node (ref "R214") (pin "P$1") (pinfunction "1_P$1") (pintype "passive"))
      (node (ref "U202") (pin "12") (pinfunction "B8_12") (pintype "bidirectional"))
    )
    (net (code "143") (name "Net-(R215-2)") (class "Default")
      (node (ref "J203") (pin "4") (pinfunction "4_4") (pintype "passive"))
      (node (ref "R215") (pin "P$2") (pinfunction "2_P$2") (pintype "passive"))
    )
    (net (code "144") (name "Net-(R216-2)") (class "Default")
      (node (ref "J203") (pin "5") (pinfunction "5_5") (pintype "passive"))
      (node (ref "R216") (pin "P$2") (pinfunction "2_P$2") (pintype "passive"))
    )
    (net (code "145") (name "Net-(R404-2)") (class "Default")
      (node (ref "J401") (pin "2") (pinfunction "2_2") (pintype "passive"))
      (node (ref "R404") (pin "P$2") (pinfunction "2_P$2") (pintype "passive"))
    )
    (net (code "146") (name "Net-(R405-2)") (class "Default")
      (node (ref "J401") (pin "3") (pinfunction "3_3") (pintype "passive"))
      (node (ref "R405") (pin "P$2") (pinfunction "2_P$2") (pintype "passive"))
    )
    (net (code "147") (name "Net-(R407-2)") (class "Default")
      (node (ref "J404") (pin "2") (pinfunction "2_2") (pintype "passive"))
      (node (ref "R407") (pin "P$2") (pinfunction "2_P$2") (pintype "passive"))
    )
    (net (code "148") (name "Net-(R408-2)") (class "Default")
      (node (ref "J404") (pin "4") (pinfunction "4_4") (pintype "passive"))
      (node (ref "R408") (pin "P$2") (pinfunction "2_P$2") (pintype "passive"))
    )
    (net (code "149") (name "Net-(R608-2)") (class "Default")
      (node (ref "D2") (pin "C") (pinfunction "C_C") (pintype "passive"))
      (node (ref "R608") (pin "P$2") (pinfunction "2_P$2") (pintype "passive"))
    )
    (net (code "150") (name "Net-(R616-1)") (class "Default")
      (node (ref "R616") (pin "P$1") (pinfunction "1_P$1") (pintype "passive"))
      (node (ref "U602") (pin "7") (pinfunction "ILIM_7") (pintype "bidirectional"))
    )
    (net (code "151") (name "Net-(R617-1)") (class "Default")
      (node (ref "R617") (pin "P$1") (pinfunction "1_P$1") (pintype "passive"))
      (node (ref "U601") (pin "7") (pinfunction "ILIM_7") (pintype "bidirectional"))
    )
    (net (code "152") (name "Net-(R620-1)") (class "Default")
      (node (ref "Q601") (pin "B") (pinfunction "B_B") (pintype "passive"))
      (node (ref "R620") (pin "P$1") (pinfunction "1_P$1") (pintype "passive"))
    )
    (net (code "153") (name "Net-(R701-1)") (class "Default")
      (node (ref "R701") (pin "P$1") (pinfunction "1_P$1") (pintype "passive"))
      (node (ref "U702") (pin "7") (pinfunction "+IN_7") (pintype "input"))
    )
    (net (code "154") (name "Net-(R702-1)") (class "Default")
      (node (ref "R702") (pin "P$1") (pinfunction "1_P$1") (pintype "passive"))
      (node (ref "R703") (pin "P$2") (pinfunction "2_P$2") (pintype "passive"))
      (node (ref "U702") (pin "8") (pinfunction "-IN_8") (pintype "input"))
    )
    (net (code "155") (name "Net-(R704-2)") (class "Default")
      (node (ref "R704") (pin "P$2") (pinfunction "2_P$2") (pintype "passive"))
      (node (ref "U701") (pin "6") (pinfunction "REXT_6") (pintype "bidirectional"))
    )
    (net (code "156") (name "Net-(R705-2)") (class "Default")
      (node (ref "R705") (pin "P$2") (pinfunction "2_P$2") (pintype "passive"))
      (node (ref "R706") (pin "P$1") (pinfunction "1_P$1") (pintype "passive"))
      (node (ref "U702") (pin "2") (pinfunction "FB_2") (pintype "bidirectional"))
    )
    (net (code "157") (name "Net-(R708-2)") (class "Default")
      (node (ref "LED702") (pin "C") (pinfunction "C_C") (pintype "passive"))
      (node (ref "R708") (pin "P$2") (pinfunction "2_P$2") (pintype "passive"))
    )
    (net (code "158") (name "Net-(R710-1)") (class "Default")
      (node (ref "J702") (pin "2") (pinfunction "2_2") (pintype "passive"))
      (node (ref "R710") (pin "P$1") (pinfunction "1_P$1") (pintype "passive"))
    )
    (net (code "159") (name "Net-(R711-2)") (class "Default")
      (node (ref "LED704") (pin "C") (pinfunction "C_C") (pintype "passive"))
      (node (ref "R711") (pin "P$2") (pinfunction "2_P$2") (pintype "passive"))
    )
    (net (code "160") (name "Net-(R712-2)") (class "Default")
      (node (ref "LED705") (pin "C") (pinfunction "C_C") (pintype "passive"))
      (node (ref "R712") (pin "P$2") (pinfunction "2_P$2") (pintype "passive"))
    )
    (net (code "161") (name "Net-(R802-1)") (class "Default")
      (node (ref "R802") (pin "P$1") (pinfunction "1_P$1") (pintype "passive"))
      (node (ref "U801") (pin "20") (pinfunction "PB2_20") (pintype "bidirectional"))
    )
    (net (code "162") (name "Net-(R803-1)") (class "Default")
      (node (ref "R803") (pin "P$1") (pinfunction "1_P$1") (pintype "passive"))
      (node (ref "U801") (pin "12") (pinfunction "PA2_12") (pintype "bidirectional"))
    )
    (net (code "163") (name "Net-(R804-1)") (class "Default")
      (node (ref "R804") (pin "P$1") (pinfunction "1_P$1") (pintype "passive"))
      (node (ref "U801") (pin "13") (pinfunction "PA3_13") (pintype "bidirectional"))
    )
    (net (code "164") (name "Net-(R901-2)") (class "Default")
      (node (ref "D902") (pin "C") (pinfunction "C_C") (pintype "passive"))
      (node (ref "R901") (pin "P$2") (pinfunction "2_P$2") (pintype "passive"))
      (node (ref "R910") (pin "P$1") (pinfunction "1_P$1") (pintype "passive"))
      (node (ref "U903") (pin "3") (pinfunction "2Y_3") (pintype "bidirectional"))
    )
    (net (code "165") (name "Net-(R902-1)") (class "Default")
      (node (ref "R902") (pin "P$1") (pinfunction "1_P$1") (pintype "passive"))
      (node (ref "U901") (pin "20") (pinfunction "B1_20") (pintype "bidirectional"))
    )
    (net (code "166") (name "Net-(R903-1)") (class "Default")
      (node (ref "R903") (pin "P$1") (pinfunction "1_P$1") (pintype "passive"))
      (node (ref "U901") (pin "17") (pinfunction "B3_17") (pintype "bidirectional"))
    )
    (net (code "167") (name "Net-(R904-1)") (class "Default")
      (node (ref "R904") (pin "P$1") (pinfunction "1_P$1") (pintype "passive"))
      (node (ref "U901") (pin "15") (pinfunction "B5_15") (pintype "bidirectional"))
    )
    (net (code "168") (name "Net-(R905-1)") (class "Default")
      (node (ref "R905") (pin "P$1") (pinfunction "1_P$1") (pintype "passive"))
      (node (ref "U902") (pin "20") (pinfunction "B1_20") (pintype "bidirectional"))
    )
    (net (code "169") (name "Net-(R906-1)") (class "Default")
      (node (ref "R906") (pin "P$1") (pinfunction "1_P$1") (pintype "passive"))
      (node (ref "U902") (pin "17") (pinfunction "B3_17") (pintype "bidirectional"))
    )
    (net (code "170") (name "Net-(R907-1)") (class "Default")
      (node (ref "R907") (pin "P$1") (pinfunction "1_P$1") (pintype "passive"))
      (node (ref "U902") (pin "15") (pinfunction "B5_15") (pintype "bidirectional"))
    )
    (net (code "171") (name "Net-(R908-1)") (class "Default")
      (node (ref "R908") (pin "P$1") (pinfunction "1_P$1") (pintype "passive"))
      (node (ref "U902") (pin "13") (pinfunction "B7_13") (pintype "bidirectional"))
    )
    (net (code "172") (name "Net-(R911-1)") (class "Default")
      (node (ref "R911") (pin "P$1") (pinfunction "1_P$1") (pintype "passive"))
      (node (ref "U901") (pin "18") (pinfunction "B2_18") (pintype "bidirectional"))
    )
    (net (code "173") (name "Net-(R912-1)") (class "Default")
      (node (ref "R912") (pin "P$1") (pinfunction "1_P$1") (pintype "passive"))
      (node (ref "U901") (pin "16") (pinfunction "B4_16") (pintype "bidirectional"))
    )
    (net (code "174") (name "Net-(R913-1)") (class "Default")
      (node (ref "R913") (pin "P$1") (pinfunction "1_P$1") (pintype "passive"))
      (node (ref "U901") (pin "14") (pinfunction "B6_14") (pintype "bidirectional"))
    )
    (net (code "175") (name "Net-(R914-1)") (class "Default")
      (node (ref "R914") (pin "P$1") (pinfunction "1_P$1") (pintype "passive"))
      (node (ref "U902") (pin "18") (pinfunction "B2_18") (pintype "bidirectional"))
    )
    (net (code "176") (name "Net-(R915-1)") (class "Default")
      (node (ref "R915") (pin "P$1") (pinfunction "1_P$1") (pintype "passive"))
      (node (ref "U902") (pin "16") (pinfunction "B4_16") (pintype "bidirectional"))
    )
    (net (code "177") (name "Net-(R916-1)") (class "Default")
      (node (ref "R916") (pin "P$1") (pinfunction "1_P$1") (pintype "passive"))
      (node (ref "U902") (pin "14") (pinfunction "B6_14") (pintype "bidirectional"))
    )
    (net (code "178") (name "Net-(R917-1)") (class "Default")
      (node (ref "R917") (pin "P$1") (pinfunction "1_P$1") (pintype "passive"))
      (node (ref "U902") (pin "12") (pinfunction "B8_12") (pintype "bidirectional"))
    )
    (net (code "179") (name "Net-(R918-2)") (class "Default")
      (node (ref "R918") (pin "P$2") (pinfunction "2_P$2") (pintype "passive"))
      (node (ref "R922") (pin "P$1") (pinfunction "1_P$1") (pintype "passive"))
    )
    (net (code "180") (name "Net-(R1001-2)") (class "Default")
      (node (ref "R1001") (pin "P$2") (pinfunction "2_P$2") (pintype "passive"))
      (node (ref "U1001") (pin "7") (pinfunction "ILIM_7") (pintype "bidirectional"))
    )
    (net (code "181") (name "Net-(R1101-2)") (class "Default")
      (node (ref "L1101") (pin "P$2") (pinfunction "P$2_P$2") (pintype "bidirectional"))
      (node (ref "R1101") (pin "P$2") (pinfunction "2_P$2") (pintype "passive"))
    )
    (net (code "182") (name "Net-(R1102-2)") (class "Default")
      (node (ref "L1102") (pin "P$2") (pinfunction "P$2_P$2") (pintype "bidirectional"))
      (node (ref "R1102") (pin "P$2") (pinfunction "2_P$2") (pintype "passive"))
    )
    (net (code "183") (name "Net-(R1103-1)") (class "Default")
      (node (ref "J601") (pin "4") (pinfunction "4_4") (pintype "passive"))
      (node (ref "L1102") (pin "P$1") (pinfunction "P$1_P$1") (pintype "bidirectional"))
      (node (ref "R1103") (pin "P$1") (pinfunction "1_P$1") (pintype "passive"))
    )
    (net (code "184") (name "Net-(R1104-1)") (class "Default")
      (node (ref "J601") (pin "3") (pinfunction "3_3") (pintype "passive"))
      (node (ref "L1101") (pin "P$1") (pinfunction "P$1_P$1") (pintype "bidirectional"))
      (node (ref "R1104") (pin "P$1") (pinfunction "1_P$1") (pintype "passive"))
    )
    (net (code "185") (name "Net-(R1106-2)") (class "Default")
      (node (ref "R1106") (pin "P$2") (pinfunction "2_P$2") (pintype "passive"))
      (node (ref "R1107") (pin "P$1") (pinfunction "1_P$1") (pintype "passive"))
      (node (ref "U1101") (pin "P$2") (pinfunction "OV1_P$2") (pintype "bidirectional"))
    )
    (net (code "186") (name "Net-(R1110-2)") (class "Default")
      (node (ref "R1110") (pin "P$2") (pinfunction "2_P$2") (pintype "passive"))
      (node (ref "R1111") (pin "P$1") (pinfunction "1_P$1") (pintype "passive"))
      (node (ref "U1101") (pin "P$4") (pinfunction "OV2_P$4") (pintype "bidirectional"))
    )
    (net (code "187") (name "Net-(R1113-2)") (class "Default")
      (node (ref "R1113") (pin "P$2") (pinfunction "2_P$2") (pintype "passive"))
      (node (ref "R1114") (pin "P$1") (pinfunction "1_P$1") (pintype "passive"))
      (node (ref "U1101") (pin "P$6") (pinfunction "OV3_P$6") (pintype "bidirectional"))
    )
    (net (code "188") (name "Net-(R1115-2)") (class "Default")
      (node (ref "R1115") (pin "P$2") (pinfunction "2_P$2") (pintype "passive"))
      (node (ref "U1101") (pin "P$24") (pinfunction "HYS_P$24") (pintype "bidirectional"))
    )
    (net (code "189") (name "Net-(U701-OUT0)") (class "Default")
      (node (ref "U701") (pin "9") (pinfunction "OUT0_9") (pintype "open_collector"))
      (node (ref "U703") (pin "C1") (pinfunction "C_C1") (pintype "passive"))
    )
    (net (code "190") (name "Net-(U701-OUT1)") (class "Default")
      (node (ref "U701") (pin "8") (pinfunction "OUT1_8") (pintype "open_collector"))
      (node (ref "U703") (pin "C2") (pinfunction "C_C2") (pintype "passive"))
    )
    (net (code "191") (name "Net-(U701-OUT2)") (class "Default")
      (node (ref "U701") (pin "7") (pinfunction "OUT2_7") (pintype "open_collector"))
      (node (ref "U703") (pin "C3") (pinfunction "C_C3") (pintype "passive"))
    )
    (net (code "192") (name "Net-(U1101-G1)") (class "Default")
      (node (ref "U1101") (pin "P$17") (pinfunction "G1_P$17") (pintype "bidirectional"))
      (node (ref "U1102") (pin "P$2") (pinfunction "G_P$2") (pintype "passive"))
      (node (ref "U1102") (pin "P$4") (pinfunction "G_P$4") (pintype "passive"))
    )
    (net (code "193") (name "Net-(U1101-G2)") (class "Default")
      (node (ref "U1101") (pin "P$15") (pinfunction "G2_P$15") (pintype "bidirectional"))
      (node (ref "U1103") (pin "P$2") (pinfunction "G_P$2") (pintype "passive"))
      (node (ref "U1103") (pin "P$4") (pinfunction "G_P$4") (pintype "passive"))
    )
    (net (code "194") (name "Net-(U1101-G3)") (class "Default")
      (node (ref "U1101") (pin "P$13") (pinfunction "G3_P$13") (pintype "bidirectional"))
      (node (ref "U1104") (pin "P$2") (pinfunction "G_P$2") (pintype "passive"))
      (node (ref "U1104") (pin "P$4") (pinfunction "G_P$4") (pintype "passive"))
    )
    (net (code "195") (name "OTG_FS_DM") (class "Default")
      (node (ref "U101") (pin "70") (pinfunction "PA11_70") (pintype "bidirectional"))
      (node (ref "U302") (pin "6") (pinfunction "D1O_6") (pintype "bidirectional"))
    )
    (net (code "196") (name "OTG_FS_DP") (class "Default")
      (node (ref "U101") (pin "71") (pinfunction "PA12_71") (pintype "bidirectional"))
      (node (ref "U302") (pin "4") (pinfunction "D2O_4") (pintype "bidirectional"))
    )
    (net (code "197") (name "PPM_INPUT") (class "Default")
      (node (ref "D901") (pin "C") (pinfunction "C_C") (pintype "passive"))
      (node (ref "R909") (pin "P$1") (pinfunction "1_P$1") (pintype "passive"))
      (node (ref "U801") (pin "29") (pinfunction "PA8_29") (pintype "bidirectional"))
      (node (ref "U903") (pin "2") (pinfunction "1A_2") (pintype "bidirectional"))
    )
    (net (code "198") (name "PRESSURE_SENS") (class "Default")
      (node (ref "C401") (pin "P$1") (pinfunction "1_P$1") (pintype "passive"))
      (node (ref "R403") (pin "P$2") (pinfunction "2_P$2") (pintype "passive"))
      (node (ref "R406") (pin "P$1") (pinfunction "1_P$1") (pintype "passive"))
      (node (ref "U101") (pin "34") (pinfunction "PC5_34") (pintype "bidirectional"))
    )
    (net (code "199") (name "PRESSURE_SENS_IN") (class "Default")
      (node (ref "ADC_PR") (pin "P$1") (pinfunction "P$1_P$1") (pintype "passive"))
      (node (ref "J402") (pin "2") (pinfunction "2_2") (pintype "passive"))
      (node (ref "R406") (pin "P$2") (pinfunction "2_P$2") (pintype "passive"))
    )
    (net (code "200") (name "RSSI_IN") (class "Default")
      (node (ref "R901") (pin "P$1") (pinfunction "1_P$1") (pintype "passive"))
      (node (ref "U801") (pin "15") (pinfunction "PA5_15") (pintype "bidirectional"))
      (node (ref "U801") (pin "33") (pinfunction "PA12_33") (pintype "bidirectional"))
    )
    (net (code "201") (name "SAFETY") (class "Default")
      (node (ref "J702") (pin "3") (pinfunction "3_3") (pintype "passive"))
      (node (ref "R713") (pin "P$1") (pinfunction "1_P$1") (pintype "passive"))
      (node (ref "U801") (pin "41") (pinfunction "PB5_41") (pintype "bidirectional"))
    )
    (net (code "202") (name "SBUS_INPUT") (class "Default")
      (node (ref "U801") (pin "22") (pinfunction "PB11_22") (pintype "bidirectional"))
      (node (ref "U903") (pin "6") (pinfunction "1Y_6") (pintype "bidirectional"))
    )
    (net (code "203") (name "SBUS_OUTPUT") (class "Default")
      (node (ref "U801") (pin "21") (pinfunction "PB10_21") (pintype "bidirectional"))
      (node (ref "U903") (pin "5") (pinfunction "2A_5") (pintype "bidirectional"))
    )
    (net (code "204") (name "SDIO_CK") (class "Default")
      (node (ref "U101") (pin "80") (pinfunction "PC12_80") (pintype "bidirectional"))
      (node (ref "U301") (pin "5") (pinfunction "CLK_5") (pintype "bidirectional"))
    )
    (net (code "205") (name "SDIO_CMD") (class "Default")
      (node (ref "R303") (pin "P$1") (pinfunction "1_P$1") (pintype "passive"))
      (node (ref "U101") (pin "83") (pinfunction "PD2_83") (pintype "bidirectional"))
      (node (ref "U301") (pin "3") (pinfunction "CMD_3") (pintype "bidirectional"))
    )
    (net (code "206") (name "SDIO_D0") (class "Default")
      (node (ref "R304") (pin "P$1") (pinfunction "1_P$1") (pintype "passive"))
      (node (ref "U101") (pin "65") (pinfunction "PC8_65") (pintype "bidirectional"))
      (node (ref "U301") (pin "7") (pinfunction "D0_7") (pintype "bidirectional"))
    )
    (net (code "207") (name "SDIO_D1") (class "Default")
      (node (ref "R305") (pin "P$1") (pinfunction "1_P$1") (pintype "passive"))
      (node (ref "U101") (pin "66") (pinfunction "PC9_66") (pintype "bidirectional"))
      (node (ref "U301") (pin "8") (pinfunction "D1_8") (pintype "bidirectional"))
    )
    (net (code "208") (name "SDIO_D2") (class "Default")
      (node (ref "R301") (pin "P$1") (pinfunction "1_P$1") (pintype "passive"))
      (node (ref "U101") (pin "78") (pinfunction "PC10_78") (pintype "bidirectional"))
      (node (ref "U301") (pin "1") (pinfunction "D2_1") (pintype "bidirectional"))
    )
    (net (code "209") (name "SDIO_D3") (class "Default")
      (node (ref "R302") (pin "P$1") (pinfunction "1_P$1") (pintype "passive"))
      (node (ref "U101") (pin "79") (pinfunction "PC11_79") (pintype "bidirectional"))
      (node (ref "U301") (pin "2") (pinfunction "D3_2") (pintype "bidirectional"))
    )
    (net (code "210") (name "SERIAL1_CTS") (class "Default")
      (node (ref "J201") (pin "4") (pinfunction "4_4") (pintype "passive"))
      (node (ref "R211") (pin "P$2") (pinfunction "2_P$2") (pintype "passive"))
    )
    (net (code "211") (name "SERIAL1_RTS") (class "Default")
      (node (ref "J201") (pin "5") (pinfunction "5_5") (pintype "passive"))
      (node (ref "R204") (pin "P$2") (pinfunction "2_P$2") (pintype "passive"))
    )
    (net (code "212") (name "SERIAL1_RX") (class "Default")
      (node (ref "J201") (pin "3") (pinfunction "3_3") (pintype "passive"))
      (node (ref "R203") (pin "P$2") (pinfunction "2_P$2") (pintype "passive"))
      (node (ref "S1RX") (pin "P$1") (pinfunction "P$1_P$1") (pintype "passive"))
    )
    (net (code "213") (name "SERIAL1_TX") (class "Default")
      (node (ref "J201") (pin "2") (pinfunction "2_2") (pintype "passive"))
      (node (ref "R210") (pin "P$2") (pinfunction "2_P$2") (pintype "passive"))
      (node (ref "S1TX") (pin "P$1") (pinfunction "P$1_P$1") (pintype "passive"))
    )
    (net (code "214") (name "SERIAL2_CTS") (class "Default")
      (node (ref "J202") (pin "4") (pinfunction "4_4") (pintype "passive"))
      (node (ref "R208") (pin "P$2") (pinfunction "2_P$2") (pintype "passive"))
    )
    (net (code "215") (name "SERIAL2_RTS") (class "Default")
      (node (ref "J202") (pin "5") (pinfunction "5_5") (pintype "passive"))
      (node (ref "R201") (pin "P$2") (pinfunction "2_P$2") (pintype "passive"))
    )
    (net (code "216") (name "SERIAL2_RX") (class "Default")
      (node (ref "J202") (pin "3") (pinfunction "3_3") (pintype "passive"))
      (node (ref "R202") (pin "P$2") (pinfunction "2_P$2") (pintype "passive"))
      (node (ref "S2RX") (pin "P$1") (pinfunction "P$1_P$1") (pintype "passive"))
    )
    (net (code "217") (name "SERIAL2_TX") (class "Default")
      (node (ref "J202") (pin "2") (pinfunction "2_2") (pintype "passive"))
      (node (ref "R209") (pin "P$2") (pinfunction "2_P$2") (pintype "passive"))
      (node (ref "S2TX") (pin "P$1") (pinfunction "P$1_P$1") (pintype "passive"))
    )
    (net (code "218") (name "SERIAL3_RX") (class "Default")
      (node (ref "J203") (pin "3") (pinfunction "3_3") (pintype "passive"))
      (node (ref "R207") (pin "P$2") (pinfunction "2_P$2") (pintype "passive"))
      (node (ref "S3RX") (pin "P$1") (pinfunction "P$1_P$1") (pintype "passive"))
    )
    (net (code "219") (name "SERIAL3_TX") (class "Default")
      (node (ref "J203") (pin "2") (pinfunction "2_2") (pintype "passive"))
      (node (ref "R214") (pin "P$2") (pinfunction "2_P$2") (pintype "passive"))
      (node (ref "S3TX") (pin "P$1") (pinfunction "P$1_P$1") (pintype "passive"))
    )
    (net (code "220") (name "SERIAL4_RX") (class "Default")
      (node (ref "J204") (pin "3") (pinfunction "3_3") (pintype "passive"))
      (node (ref "R206") (pin "P$2") (pinfunction "2_P$2") (pintype "passive"))
      (node (ref "S4RX") (pin "P$1") (pinfunction "P$1_P$1") (pintype "passive"))
    )
    (net (code "221") (name "SERIAL4_TX") (class "Default")
      (node (ref "J204") (pin "2") (pinfunction "2_2") (pintype "passive"))
      (node (ref "R213") (pin "P$2") (pinfunction "2_P$2") (pintype "passive"))
      (node (ref "S4TX") (pin "P$1") (pinfunction "P$1_P$1") (pintype "passive"))
    )
    (net (code "222") (name "SERIAL5_RX") (class "Default")
      (node (ref "J204") (pin "5") (pinfunction "5_5") (pintype "passive"))
      (node (ref "R205") (pin "P$2") (pinfunction "2_P$2") (pintype "passive"))
      (node (ref "S5_RX") (pin "P$1") (pinfunction "P$1_P$1") (pintype "passive"))
    )
    (net (code "223") (name "SERIAL5_TX") (class "Default")
      (node (ref "J204") (pin "4") (pinfunction "4_4") (pintype "passive"))
      (node (ref "R212") (pin "P$2") (pinfunction "2_P$2") (pintype "passive"))
      (node (ref "S5_TX") (pin "P$1") (pinfunction "P$1_P$1") (pintype "passive"))
    )
    (net (code "224") (name "SERIAL_FMU_TO_IO") (class "Default")
      (node (ref "R804") (pin "P$2") (pinfunction "2_P$2") (pintype "passive"))
      (node (ref "U101") (pin "63") (pinfunction "PC6_63") (pintype "bidirectional"))
    )
    (net (code "225") (name "SERIAL_IO_TO_FMU") (class "Default")
      (node (ref "R803") (pin "P$2") (pinfunction "2_P$2") (pintype "passive"))
      (node (ref "U101") (pin "64") (pinfunction "PC7_64") (pintype "bidirectional"))
    )
    (net (code "226") (name "SPI_EXT_MISO") (class "Default")
      (node (ref "J403") (pin "3") (pinfunction "3_3") (pintype "passive"))
      (node (ref "U101") (pin "4") (pinfunction "PE5_4") (pintype "bidirectional"))
    )
    (net (code "227") (name "SPI_EXT_MOSI") (class "Default")
      (node (ref "J403") (pin "4") (pinfunction "4_4") (pintype "passive"))
      (node (ref "U101") (pin "5") (pinfunction "PE6_5") (pintype "bidirectional"))
    )
    (net (code "228") (name "SPI_EXT_SCK") (class "Default")
      (node (ref "J403") (pin "2") (pinfunction "2_2") (pintype "passive"))
      (node (ref "U101") (pin "1") (pinfunction "PE2_1") (pintype "bidirectional"))
    )
    (net (code "229") (name "SPI_INT_MISO") (class "Default")
      (node (ref "U101") (pin "31") (pinfunction "PA6_31") (pintype "bidirectional"))
      (node (ref "U501") (pin "4") (pinfunction "SDO/SA0_4") (pintype "bidirectional"))
      (node (ref "U502") (pin "4") (pinfunction "SDO/SA0_4") (pintype "bidirectional"))
      (node (ref "U504") (pin "7") (pinfunction "SDO/SA0_7") (pintype "bidirectional"))
      (node (ref "U505") (pin "9") (pinfunction "AD0/SDO_9") (pintype "bidirectional"))
      (node (ref "U506") (pin "6") (pinfunction "SDO_6") (pintype "bidirectional"))
      (node (ref "X503") (pin "9") (pinfunction "S_9") (pintype "passive"))
    )
    (net (code "230") (name "SPI_INT_MOSI") (class "Default")
      (node (ref "U101") (pin "32") (pinfunction "PA7_32") (pintype "bidirectional"))
      (node (ref "U501") (pin "3") (pinfunction "SDA/SDI/SDO_3") (pintype "bidirectional"))
      (node (ref "U502") (pin "3") (pinfunction "SDA/SDI/SDO_3") (pintype "bidirectional"))
      (node (ref "U504") (pin "6") (pinfunction "SDA/SDI/SDO_6") (pintype "bidirectional"))
      (node (ref "U505") (pin "24") (pinfunction "SDA/SDI_24") (pintype "bidirectional"))
      (node (ref "U506") (pin "7") (pinfunction "SDI/SDA_7") (pintype "bidirectional"))
      (node (ref "X503") (pin "8") (pinfunction "S_8") (pintype "passive"))
    )
    (net (code "231") (name "SPI_INT_SCK") (class "Default")
      (node (ref "U101") (pin "30") (pinfunction "PA5_30") (pintype "bidirectional"))
      (node (ref "U501") (pin "2") (pinfunction "SCL/SPC_2") (pintype "input"))
      (node (ref "U502") (pin "2") (pinfunction "SCL/SPC_2") (pintype "bidirectional"))
      (node (ref "U504") (pin "4") (pinfunction "SCL/SPC_4") (pintype "bidirectional"))
      (node (ref "U505") (pin "23") (pinfunction "SCL/SCLK_23") (pintype "bidirectional"))
      (node (ref "U506") (pin "8") (pinfunction "SCLK_8") (pintype "bidirectional"))
      (node (ref "X503") (pin "10") (pinfunction "S_10") (pintype "passive"))
    )
    (net (code "232") (name "VBAT") (class "Default")
      (node (ref "B601") (pin "1") (pinfunction "POS_1") (pintype "bidirectional"))
      (node (ref "R608") (pin "P$1") (pinfunction "1_P$1") (pintype "passive"))
      (node (ref "U101") (pin "6") (pinfunction "VBAT_6") (pintype "power_in"))
      (node (ref "U801") (pin "1") (pinfunction "VBAT_1") (pintype "power_in"))
    )
    (net (code "233") (name "VBUS") (class "Default")
      (node (ref "C1103") (pin "P$1") (pinfunction "1_P$1") (pintype "passive"))
      (node (ref "J301") (pin "VBUS") (pinfunction "1_VBUS") (pintype "power_in"))
      (node (ref "J302") (pin "1") (pinfunction "1_1") (pintype "passive"))
      (node (ref "R1112") (pin "P$1") (pinfunction "1_P$1") (pintype "passive"))
      (node (ref "U101") (pin "68") (pinfunction "PA9_68") (pintype "bidirectional"))
      (node (ref "U1101") (pin "P$19") (pinfunction "V3_P$19") (pintype "bidirectional"))
      (node (ref "U1104") (pin "P$7") (pinfunction "D_P$7") (pintype "passive"))
      (node (ref "U1104") (pin "P$8") (pinfunction "D_P$8") (pintype "passive"))
      (node (ref "U302") (pin "5") (pinfunction "VBUS_5") (pintype "bidirectional"))
      (node (ref "VBUS") (pin "P$1") (pinfunction "P$1_P$1") (pintype "passive"))
    )
    (net (code "234") (name "VDD_3V3_SENSORS") (class "Default")
      (node (ref "C501") (pin "P$1") (pinfunction "1_P$1") (pintype "passive"))
      (node (ref "C502") (pin "P$1") (pinfunction "1_P$1") (pintype "passive"))
      (node (ref "C503") (pin "P$1") (pinfunction "1_P$1") (pintype "passive"))
      (node (ref "C506") (pin "P$1") (pinfunction "1_P$1") (pintype "passive"))
      (node (ref "C507") (pin "P$1") (pinfunction "1_P$1") (pintype "passive"))
      (node (ref "C508") (pin "P$1") (pinfunction "1_P$1") (pintype "passive"))
      (node (ref "C511") (pin "P$1") (pinfunction "1_P$1") (pintype "passive"))
      (node (ref "C513") (pin "P$1") (pinfunction "1_P$1") (pintype "passive"))
      (node (ref "C514") (pin "P$1") (pinfunction "1_P$1") (pintype "passive"))
      (node (ref "C605") (pin "P$1") (pinfunction "1_P$1") (pintype "passive"))
      (node (ref "C617") (pin "P$1") (pinfunction "1_P$1") (pintype "passive"))
      (node (ref "Q601") (pin "E") (pinfunction "E_E") (pintype "passive"))
      (node (ref "U501") (pin "1") (pinfunction "VDD_IO_1") (pintype "bidirectional"))
      (node (ref "U501") (pin "15") (pinfunction "RES_P15_VDD_15") (pintype "bidirectional"))
      (node (ref "U501") (pin "16") (pinfunction "VDD_16") (pintype "bidirectional"))
      (node (ref "U502") (pin "1") (pinfunction "VDD_IO_1") (pintype "bidirectional"))
      (node (ref "U502") (pin "15") (pinfunction "VDD_15") (pintype "bidirectional"))
      (node (ref "U502") (pin "16") (pinfunction "VDD_16") (pintype "bidirectional"))
      (node (ref "U504") (pin "1") (pinfunction "VDD_IO_1") (pintype "bidirectional"))
      (node (ref "U504") (pin "14") (pinfunction "VDD_14") (pintype "bidirectional"))
      (node (ref "U505") (pin "13") (pinfunction "VDD_13") (pintype "bidirectional"))
      (node (ref "U506") (pin "1") (pinfunction "VDD_1") (pintype "bidirectional"))
      (node (ref "U603") (pin "8") (pinfunction "VOUT1_8") (pintype "bidirectional"))
      (node (ref "VDDA_3V1101") (pin "P$1") (pinfunction "P$1_P$1") (pintype "passive"))
      (node (ref "X503") (pin "1") (pinfunction "S_1") (pintype "passive"))
    )
    (net (code "235") (name "VDD_3V3_SENSORS_EN") (class "Default")
      (node (ref "R603") (pin "P$2") (pinfunction "2_P$2") (pintype "passive"))
      (node (ref "R620") (pin "P$2") (pinfunction "2_P$2") (pintype "passive"))
      (node (ref "R635") (pin "P$2") (pinfunction "2_P$2") (pintype "passive"))
      (node (ref "U101") (pin "2") (pinfunction "PE3_2") (pintype "bidirectional"))
      (node (ref "U603") (pin "5") (pinfunction "EN1_5") (pintype "bidirectional"))
    )
    (net (code "236") (name "VDD_3V3_SPEKTRUM") (class "Default")
      (node (ref "C1008") (pin "P$1") (pinfunction "1_P$1") (pintype "passive"))
      (node (ref "D801") (pin "C") (pinfunction "C_C") (pintype "passive"))
      (node (ref "J801") (pin "P$1") (pinfunction "P$1_P$1") (pintype "bidirectional"))
      (node (ref "U1002") (pin "8") (pinfunction "VOUT1_8") (pintype "bidirectional"))
    )
    (net (code "237") (name "VDD_3V3_SPEKTRUM_EN") (class "Default")
      (node (ref "R1002") (pin "P$2") (pinfunction "2_P$2") (pintype "passive"))
      (node (ref "U1002") (pin "5") (pinfunction "EN1_5") (pintype "bidirectional"))
      (node (ref "U801") (pin "2") (pinfunction "PC13_2") (pintype "bidirectional"))
    )
    (net (code "238") (name "VDD_5V_BRICK") (class "Default")
      (node (ref "C1101") (pin "P$1") (pinfunction "1_P$1") (pintype "passive"))
      (node (ref "J601") (pin "1") (pinfunction "1_1") (pintype "passive"))
      (node (ref "J601") (pin "2") (pinfunction "2_2") (pintype "passive"))
      (node (ref "R1105") (pin "P$1") (pinfunction "1_P$1") (pintype "passive"))
      (node (ref "U1101") (pin "P$21") (pinfunction "V1_P$21") (pintype "bidirectional"))
      (node (ref "U1102") (pin "P$7") (pinfunction "D_P$7") (pintype "passive"))
      (node (ref "U1102") (pin "P$8") (pinfunction "D_P$8") (pintype "passive"))
      (node (ref "VDD_5V_BRICK") (pin "P$1") (pinfunction "P$1_P$1") (pintype "passive"))
    )
    (net (code "239") (name "VDD_5V_HIPOWER") (class "Default")
      (node (ref "C614") (pin "P$1") (pinfunction "1_P$1") (pintype "passive"))
      (node (ref "L201") (pin "P$1") (pinfunction "P$1_P$1") (pintype "bidirectional"))
      (node (ref "U601") (pin "8") (pinfunction "OUT_8") (pintype "bidirectional"))
    )
    (net (code "240") (name "VDD_5V_IN") (class "Default")
      (node (ref "C1104") (pin "P$1") (pinfunction "1_P$1") (pintype "passive"))
      (node (ref "C702") (pin "P$1") (pinfunction "1_P$1") (pintype "passive"))
      (node (ref "F1001") (pin "1") (pinfunction "1_1") (pintype "bidirectional"))
      (node (ref "L603") (pin "P$1") (pinfunction "P$1_P$1") (pintype "bidirectional"))
      (node (ref "L701") (pin "P$1") (pinfunction "1_P$1") (pintype "passive"))
      (node (ref "LED701") (pin "A") (pinfunction "A_A") (pintype "passive"))
      (node (ref "LED704") (pin "A") (pinfunction "A_A") (pintype "passive"))
      (node (ref "R609") (pin "P$2") (pinfunction "2_P$2") (pintype "passive"))
      (node (ref "RN1101") (pin "5") (pinfunction "2_5") (pintype "passive"))
      (node (ref "RN1101") (pin "6") (pinfunction "2_6") (pintype "passive"))
      (node (ref "RN1101") (pin "7") (pinfunction "2_7") (pintype "passive"))
      (node (ref "U1101") (pin "P$12") (pinfunction "VOUT_P$12") (pintype "bidirectional"))
      (node (ref "U1102") (pin "P$5") (pinfunction "D_P$5") (pintype "passive"))
      (node (ref "U1102") (pin "P$6") (pinfunction "D_P$6") (pintype "passive"))
      (node (ref "U1103") (pin "P$5") (pinfunction "D_P$5") (pintype "passive"))
      (node (ref "U1103") (pin "P$6") (pinfunction "D_P$6") (pintype "passive"))
      (node (ref "U1104") (pin "P$5") (pinfunction "D_P$5") (pintype "passive"))
      (node (ref "U1104") (pin "P$6") (pinfunction "D_P$6") (pintype "passive"))
      (node (ref "U601") (pin "1") (pinfunction "IN_1") (pintype "bidirectional"))
      (node (ref "U602") (pin "1") (pinfunction "IN_1") (pintype "bidirectional"))
      (node (ref "U702") (pin "3") (pinfunction "VIN_3") (pintype "power_in"))
      (node (ref "U703") (pin "A1") (pinfunction "A_A1") (pintype "passive"))
      (node (ref "U703") (pin "A2") (pinfunction "A_A2") (pintype "passive"))
      (node (ref "U703") (pin "A3") (pinfunction "A_A3") (pintype "passive"))
      (node (ref "VDD_5V_IN") (pin "P$1") (pinfunction "P$1_P$1") (pintype "passive"))
    )
    (net (code "241") (name "VDD_5V_PERIPH") (class "Default")
      (node (ref "C618") (pin "P$1") (pinfunction "1_P$1") (pintype "passive"))
      (node (ref "L202") (pin "P$1") (pinfunction "P$1_P$1") (pintype "bidirectional"))
      (node (ref "L203") (pin "P$1") (pinfunction "P$1_P$1") (pintype "bidirectional"))
      (node (ref "L401") (pin "P$1") (pinfunction "P$1_P$1") (pintype "bidirectional"))
      (node (ref "L402") (pin "P$1") (pinfunction "P$1_P$1") (pintype "bidirectional"))
      (node (ref "L403") (pin "P$1") (pinfunction "P$1_P$1") (pintype "bidirectional"))
      (node (ref "L404") (pin "P$1") (pinfunction "P$1_P$1") (pintype "bidirectional"))
      (node (ref "U602") (pin "8") (pinfunction "OUT_8") (pintype "bidirectional"))
    )
    (net (code "242") (name "VDD_5V_SENS") (class "Default")
      (node (ref "R609") (pin "P$1") (pinfunction "1_P$1") (pintype "passive"))
      (node (ref "R610") (pin "P$1") (pinfunction "1_P$1") (pintype "passive"))
      (node (ref "U101") (pin "29") (pinfunction "PA4_29") (pintype "bidirectional"))
    )
    (net (code "243") (name "VDD_SERVO") (class "Default")
      (node (ref "C1102") (pin "P$1") (pinfunction "1_P$1") (pintype "passive"))
      (node (ref "D1") (pin "ANODE") (pinfunction "A_ANODE") (pintype "passive"))
      (node (ref "J901") (pin "11") (pinfunction "S_11") (pintype "passive"))
      (node (ref "J901") (pin "14") (pinfunction "S_14") (pintype "passive"))
      (node (ref "J901") (pin "17") (pinfunction "S_17") (pintype "passive"))
      (node (ref "J901") (pin "20") (pinfunction "S_20") (pintype "passive"))
      (node (ref "J901") (pin "23") (pinfunction "S_23") (pintype "passive"))
      (node (ref "J901") (pin "26") (pinfunction "S_26") (pintype "passive"))
      (node (ref "J901") (pin "29") (pinfunction "S_29") (pintype "passive"))
      (node (ref "J901") (pin "32") (pinfunction "S_32") (pintype "passive"))
      (node (ref "J901") (pin "35") (pinfunction "S_35") (pintype "passive"))
      (node (ref "J901") (pin "38") (pinfunction "S_38") (pintype "passive"))
      (node (ref "J901") (pin "41") (pinfunction "S_41") (pintype "passive"))
      (node (ref "J901") (pin "44") (pinfunction "S_44") (pintype "passive"))
      (node (ref "J901") (pin "47") (pinfunction "S_47") (pintype "passive"))
      (node (ref "J901") (pin "5") (pinfunction "S_5") (pintype "passive"))
      (node (ref "J901") (pin "8") (pinfunction "S_8") (pintype "passive"))
      (node (ref "R1109") (pin "P$1") (pinfunction "1_P$1") (pintype "passive"))
      (node (ref "R922") (pin "P$2") (pinfunction "2_P$2") (pintype "passive"))
      (node (ref "U1101") (pin "P$20") (pinfunction "V2_P$20") (pintype "bidirectional"))
      (node (ref "U1103") (pin "P$7") (pinfunction "D_P$7") (pintype "passive"))
      (node (ref "U1103") (pin "P$8") (pinfunction "D_P$8") (pintype "passive"))
      (node (ref "VDD_SERVO") (pin "P$1") (pinfunction "P$1_P$1") (pintype "passive"))
    )
    (net (code "244") (name "VDD_SERVO_IN") (class "Default")
      (node (ref "L901") (pin "P$2") (pinfunction "P$2_P$2") (pintype "bidirectional"))
      (node (ref "U1001") (pin "1") (pinfunction "IN_1") (pintype "bidirectional"))
    )
    (net (code "245") (name "VDD_SERVO_SENS") (class "Default")
      (node (ref "R918") (pin "P$1") (pinfunction "1_P$1") (pintype "passive"))
      (node (ref "R919") (pin "P$2") (pinfunction "2_P$2") (pintype "passive"))
      (node (ref "U801") (pin "14") (pinfunction "PA4_14") (pintype "bidirectional"))
    )
    (net (code "246") (name "unconnected-(J301-4-PadID)") (class "Default")
      (node (ref "J301") (pin "ID") (pinfunction "4_ID") (pintype "passive"))
    )
    (net (code "247") (name "unconnected-(JX301A-S-Pad10)") (class "Default")
      (node (ref "JX301") (pin "10") (pinfunction "S_10") (pintype "passive"))
    )
    (net (code "248") (name "unconnected-(JX301F-S-Pad8)") (class "Default")
      (node (ref "JX301") (pin "8") (pinfunction "S_8") (pintype "passive"))
    )
    (net (code "249") (name "unconnected-(JX802A-S-Pad10)") (class "Default")
      (node (ref "JX802") (pin "10") (pinfunction "S_10") (pintype "passive"))
    )
    (net (code "250") (name "unconnected-(JX802F-S-Pad8)") (class "Default")
      (node (ref "JX802") (pin "8") (pinfunction "S_8") (pintype "passive"))
    )
    (net (code "251") (name "unconnected-(U101I-PC1-Pad16)") (class "Default")
      (node (ref "U101") (pin "16") (pinfunction "PC1_16") (pintype "bidirectional"))
    )
    (net (code "252") (name "unconnected-(U202-A1-Pad1)") (class "Default")
      (node (ref "U202") (pin "1") (pinfunction "A1_1") (pintype "bidirectional"))
    )
    (net (code "253") (name "unconnected-(U202-A2-Pad3)") (class "Default")
      (node (ref "U202") (pin "3") (pinfunction "A2_3") (pintype "bidirectional"))
    )
    (net (code "254") (name "unconnected-(U202-B1-Pad20)") (class "Default")
      (node (ref "U202") (pin "20") (pinfunction "B1_20") (pintype "bidirectional"))
    )
    (net (code "255") (name "unconnected-(U202-B2-Pad18)") (class "Default")
      (node (ref "U202") (pin "18") (pinfunction "B2_18") (pintype "bidirectional"))
    )
    (net (code "256") (name "unconnected-(U501-INT1-Pad7)") (class "Default")
      (node (ref "U501") (pin "7") (pinfunction "INT1_7") (pintype "output"))
    )
    (net (code "257") (name "unconnected-(U502-DEN-Pad8)") (class "Default")
      (node (ref "U502") (pin "8") (pinfunction "DEN_8") (pintype "bidirectional"))
    )
    (net (code "258") (name "unconnected-(U502-INT1-Pad7)") (class "Default")
      (node (ref "U502") (pin "7") (pinfunction "INT1_7") (pintype "bidirectional"))
    )
    (net (code "259") (name "unconnected-(U505-AUX_CL-Pad7)") (class "Default")
      (node (ref "U505") (pin "7") (pinfunction "AUX_CL_7") (pintype "bidirectional"))
    )
    (net (code "260") (name "unconnected-(U505-AUX_DA-Pad6)") (class "Default")
      (node (ref "U505") (pin "6") (pinfunction "AUX_DA_6") (pintype "bidirectional"))
    )
    (net (code "261") (name "unconnected-(U505-CLKOUT-Pad22)") (class "Default")
      (node (ref "U505") (pin "22") (pinfunction "CLKOUT_22") (pintype "bidirectional"))
    )
    (net (code "262") (name "unconnected-(U505-FSYNC-Pad11)") (class "Default")
      (node (ref "U505") (pin "11") (pinfunction "FSYNC_11") (pintype "bidirectional"))
    )
    (net (code "263") (name "unconnected-(U505-NC1-Pad2)") (class "Default")
      (node (ref "U505") (pin "2") (pinfunction "NC1_2") (pintype "bidirectional"))
    )
    (net (code "264") (name "unconnected-(U505-NC2-Pad3)") (class "Default")
      (node (ref "U505") (pin "3") (pinfunction "NC2_3") (pintype "bidirectional"))
    )
    (net (code "265") (name "unconnected-(U505-NC3-Pad4)") (class "Default")
      (node (ref "U505") (pin "4") (pinfunction "NC3_4") (pintype "bidirectional"))
    )
    (net (code "266") (name "unconnected-(U505-NC4-Pad5)") (class "Default")
      (node (ref "U505") (pin "5") (pinfunction "NC4_5") (pintype "bidirectional"))
    )
    (net (code "267") (name "unconnected-(U505-NC5-Pad14)") (class "Default")
      (node (ref "U505") (pin "14") (pinfunction "NC5_14") (pintype "bidirectional"))
    )
    (net (code "268") (name "unconnected-(U505-NC6-Pad15)") (class "Default")
      (node (ref "U505") (pin "15") (pinfunction "NC6_15") (pintype "bidirectional"))
    )
    (net (code "269") (name "unconnected-(U505-NC7-Pad16)") (class "Default")
      (node (ref "U505") (pin "16") (pinfunction "NC7_16") (pintype "bidirectional"))
    )
    (net (code "270") (name "unconnected-(U505-NC8-Pad17)") (class "Default")
      (node (ref "U505") (pin "17") (pinfunction "NC8_17") (pintype "bidirectional"))
    )
    (net (code "271") (name "unconnected-(U505-RESV1-Pad19)") (class "Default")
      (node (ref "U505") (pin "19") (pinfunction "RESV1_19") (pintype "bidirectional"))
    )
    (net (code "272") (name "unconnected-(U505-RESV2-Pad21)") (class "Default")
      (node (ref "U505") (pin "21") (pinfunction "RESV2_21") (pintype "bidirectional"))
    )
    (net (code "273") (name "unconnected-(U506-CSB1-Pad4)") (class "Default")
      (node (ref "U506") (pin "4") (pinfunction "CSB1_4") (pintype "bidirectional"))
    )
    (net (code "274") (name "unconnected-(U801B-PA11-Pad32)") (class "Default")
      (node (ref "U801") (pin "32") (pinfunction "PA11_32") (pintype "bidirectional"))
    )
    (net (code "275") (name "unconnected-(U801D-PB12-Pad25)") (class "Default")
      (node (ref "U801") (pin "25") (pinfunction "PB12_25") (pintype "bidirectional"))
    )
    (net (code "276") (name "unconnected-(U801E-PB6-Pad42)") (class "Default")
      (node (ref "U801") (pin "42") (pinfunction "PB6_42") (pintype "bidirectional"))
    )
    (net (code "277") (name "unconnected-(U801E-PB7-Pad43)") (class "Default")
      (node (ref "U801") (pin "43") (pinfunction "PB7_43") (pintype "bidirectional"))
    )
    (net (code "278") (name "unconnected-(U801F-PC14-Pad3)") (class "Default")
      (node (ref "U801") (pin "3") (pinfunction "PC14_3") (pintype "bidirectional"))
    )
    (net (code "279") (name "unconnected-(U801F-PC15-Pad4)") (class "Default")
      (node (ref "U801") (pin "4") (pinfunction "PC15_4") (pintype "bidirectional"))
    )
    (net (code "280") (name "unconnected-(U901-A7-Pad8)") (class "Default")
      (node (ref "U901") (pin "8") (pinfunction "A7_8") (pintype "bidirectional"))
    )
    (net (code "281") (name "unconnected-(U901-A8-Pad9)") (class "Default")
      (node (ref "U901") (pin "9") (pinfunction "A8_9") (pintype "bidirectional"))
    )
    (net (code "282") (name "unconnected-(U901-B7-Pad13)") (class "Default")
      (node (ref "U901") (pin "13") (pinfunction "B7_13") (pintype "bidirectional"))
    )
    (net (code "283") (name "unconnected-(U901-B8-Pad12)") (class "Default")
      (node (ref "U901") (pin "12") (pinfunction "B8_12") (pintype "bidirectional"))
    )
    (net (code "284") (name "unconnected-(U1101-CAS-PadP$11)") (class "Default")
      (node (ref "U1101") (pin "P$11") (pinfunction "CAS_P$11") (pintype "bidirectional"))
    )
    (net (code "285") (name "unconnected-(U1101-EN-PadP$22)") (class "Default")
      (node (ref "U1101") (pin "P$22") (pinfunction "EN_P$22") (pintype "bidirectional"))
    )
    (net (code "286") (name "unconnected-(U1101-~{SHDN}-PadP$23)") (class "Default")
      (node (ref "U1101") (pin "P$23") (pinfunction "~{SHDN}_P$23") (pintype "bidirectional"))
    )
    (net (code "287") (name "~{ACCEL_MAG_CS}") (class "Default")
      (node (ref "U101") (pin "9") (pinfunction "PC15_9") (pintype "bidirectional"))
      (node (ref "U504") (pin "8") (pinfunction "CS_8") (pintype "bidirectional"))
      (node (ref "X503") (pin "6") (pinfunction "S_6") (pintype "passive"))
    )
    (net (code "288") (name "~{BARO_CS}") (class "Default")
      (node (ref "U101") (pin "88") (pinfunction "PD7_88") (pintype "bidirectional"))
      (node (ref "U506") (pin "5") (pinfunction "CSB2_5") (pintype "bidirectional"))
    )
    (net (code "289") (name "~{FMU-LED_AMBER}") (class "Default")
      (node (ref "R707") (pin "P$1") (pinfunction "1_P$1") (pintype "passive"))
      (node (ref "U101") (pin "43") (pinfunction "PE12_43") (pintype "bidirectional"))
    )
    (net (code "290") (name "~{FRAM_CS}") (class "Default")
      (node (ref "U101") (pin "57") (pinfunction "PD10_57") (pintype "bidirectional"))
      (node (ref "U102") (pin "1") (pinfunction "~{S}_1") (pintype "bidirectional"))
    )
    (net (code "291") (name "~{GYRO_CS}") (class "Default")
      (node (ref "U101") (pin "7") (pinfunction "PC13_7") (pintype "bidirectional"))
      (node (ref "U501") (pin "5") (pinfunction "CS_5") (pintype "input"))
      (node (ref "U502") (pin "5") (pinfunction "CS_5") (pintype "bidirectional"))
      (node (ref "X503") (pin "7") (pinfunction "S_7") (pintype "passive"))
    )
    (net (code "292") (name "~{IO-LED_AMBER}") (class "Default")
      (node (ref "R709") (pin "P$1") (pinfunction "1_P$1") (pintype "passive"))
      (node (ref "U801") (pin "28") (pinfunction "PB15_28") (pintype "bidirectional"))
    )
    (net (code "293") (name "~{IO-LED_BLUE}") (class "Default")
      (node (ref "R712") (pin "P$1") (pinfunction "1_P$1") (pintype "passive"))
      (node (ref "U801") (pin "27") (pinfunction "PB14_27") (pintype "bidirectional"))
    )
    (net (code "294") (name "~{IO-LED_SAFETY}") (class "Default")
      (node (ref "R710") (pin "P$2") (pinfunction "2_P$2") (pintype "passive"))
      (node (ref "U801") (pin "26") (pinfunction "PB13_26") (pintype "bidirectional"))
    )
    (net (code "295") (name "~{MPU_CS}") (class "Default")
      (node (ref "U101") (pin "17") (pinfunction "PC2_17") (pintype "bidirectional"))
      (node (ref "U505") (pin "8") (pinfunction "/CS_8") (pintype "bidirectional"))
    )
    (net (code "296") (name "~{SBUS_OUTPUT_EN}") (class "Default")
      (node (ref "U801") (pin "40") (pinfunction "PB4_40") (pintype "bidirectional"))
      (node (ref "U903") (pin "7") (pinfunction "~{2OE}_7") (pintype "input"))
    )
    (net (code "297") (name "~{SPI_EXT_NSS}") (class "Default")
      (node (ref "J403") (pin "5") (pinfunction "5_5") (pintype "passive"))
      (node (ref "U101") (pin "3") (pinfunction "PE4_3") (pintype "bidirectional"))
    )
    (net (code "298") (name "~{VBUS_VALID}") (class "Default")
      (node (ref "!VBUS_VALID") (pin "P$1") (pinfunction "P$1_P$1") (pintype "passive"))
      (node (ref "RN1101") (pin "2") (pinfunction "1_2") (pintype "passive"))
      (node (ref "U101") (pin "15") (pinfunction "PC0_15") (pintype "bidirectional"))
      (node (ref "U1101") (pin "P$9") (pinfunction "~{VALID3}_P$9") (pintype "bidirectional"))
    )
    (net (code "299") (name "~{VDD_5V_HIPOWER_OC}") (class "Default")
      (node (ref "R602") (pin "P$1") (pinfunction "1_P$1") (pintype "passive"))
      (node (ref "U101") (pin "41") (pinfunction "PE10_41") (pintype "bidirectional"))
      (node (ref "U601") (pin "4") (pinfunction "~{FAULT}_4") (pintype "bidirectional"))
    )
    (net (code "300") (name "~{VDD_5V_PERIPH_EN}") (class "Default")
      (node (ref "R615") (pin "P$1") (pinfunction "1_P$1") (pintype "passive"))
      (node (ref "U101") (pin "67") (pinfunction "PA8_67") (pintype "bidirectional"))
      (node (ref "U601") (pin "5") (pinfunction "~{CE}_5") (pintype "bidirectional"))
      (node (ref "U602") (pin "5") (pinfunction "~{CE}_5") (pintype "bidirectional"))
    )
    (net (code "301") (name "~{VDD_5V_PERIPH_OC}") (class "Default")
      (node (ref "R604") (pin "P$1") (pinfunction "1_P$1") (pintype "passive"))
      (node (ref "U101") (pin "46") (pinfunction "PE15_46") (pintype "bidirectional"))
      (node (ref "U602") (pin "4") (pinfunction "~{FAULT}_4") (pintype "bidirectional"))
    )
    (net (code "302") (name "~{VDD_BRICK_VALID}") (class "Default")
      (node (ref "!VDD_BRICK_VALID") (pin "P$1") (pinfunction "P$1_P$1") (pintype "passive"))
      (node (ref "RN1101") (pin "4") (pinfunction "1_4") (pintype "passive"))
      (node (ref "U101") (pin "91") (pinfunction "PB5_91") (pintype "bidirectional"))
      (node (ref "U1101") (pin "P$7") (pinfunction "~{VALID1}_P$7") (pintype "bidirectional"))
    )
    (net (code "303") (name "~{VDD_SERVO_VALID}") (class "Default")
      (node (ref "!VDD_SERVO_VALID") (pin "P$1") (pinfunction "P$1_P$1") (pintype "passive"))
      (node (ref "RN1101") (pin "3") (pinfunction "1_3") (pintype "passive"))
      (node (ref "U101") (pin "93") (pinfunction "PB7_93") (pintype "bidirectional"))
      (node (ref "U1101") (pin "P$8") (pinfunction "~{VALID2}_P$8") (pintype "bidirectional"))
    )
  )
)
